# easyEDA.net
KiCad netlist of a schematic drawn in EasyEDA
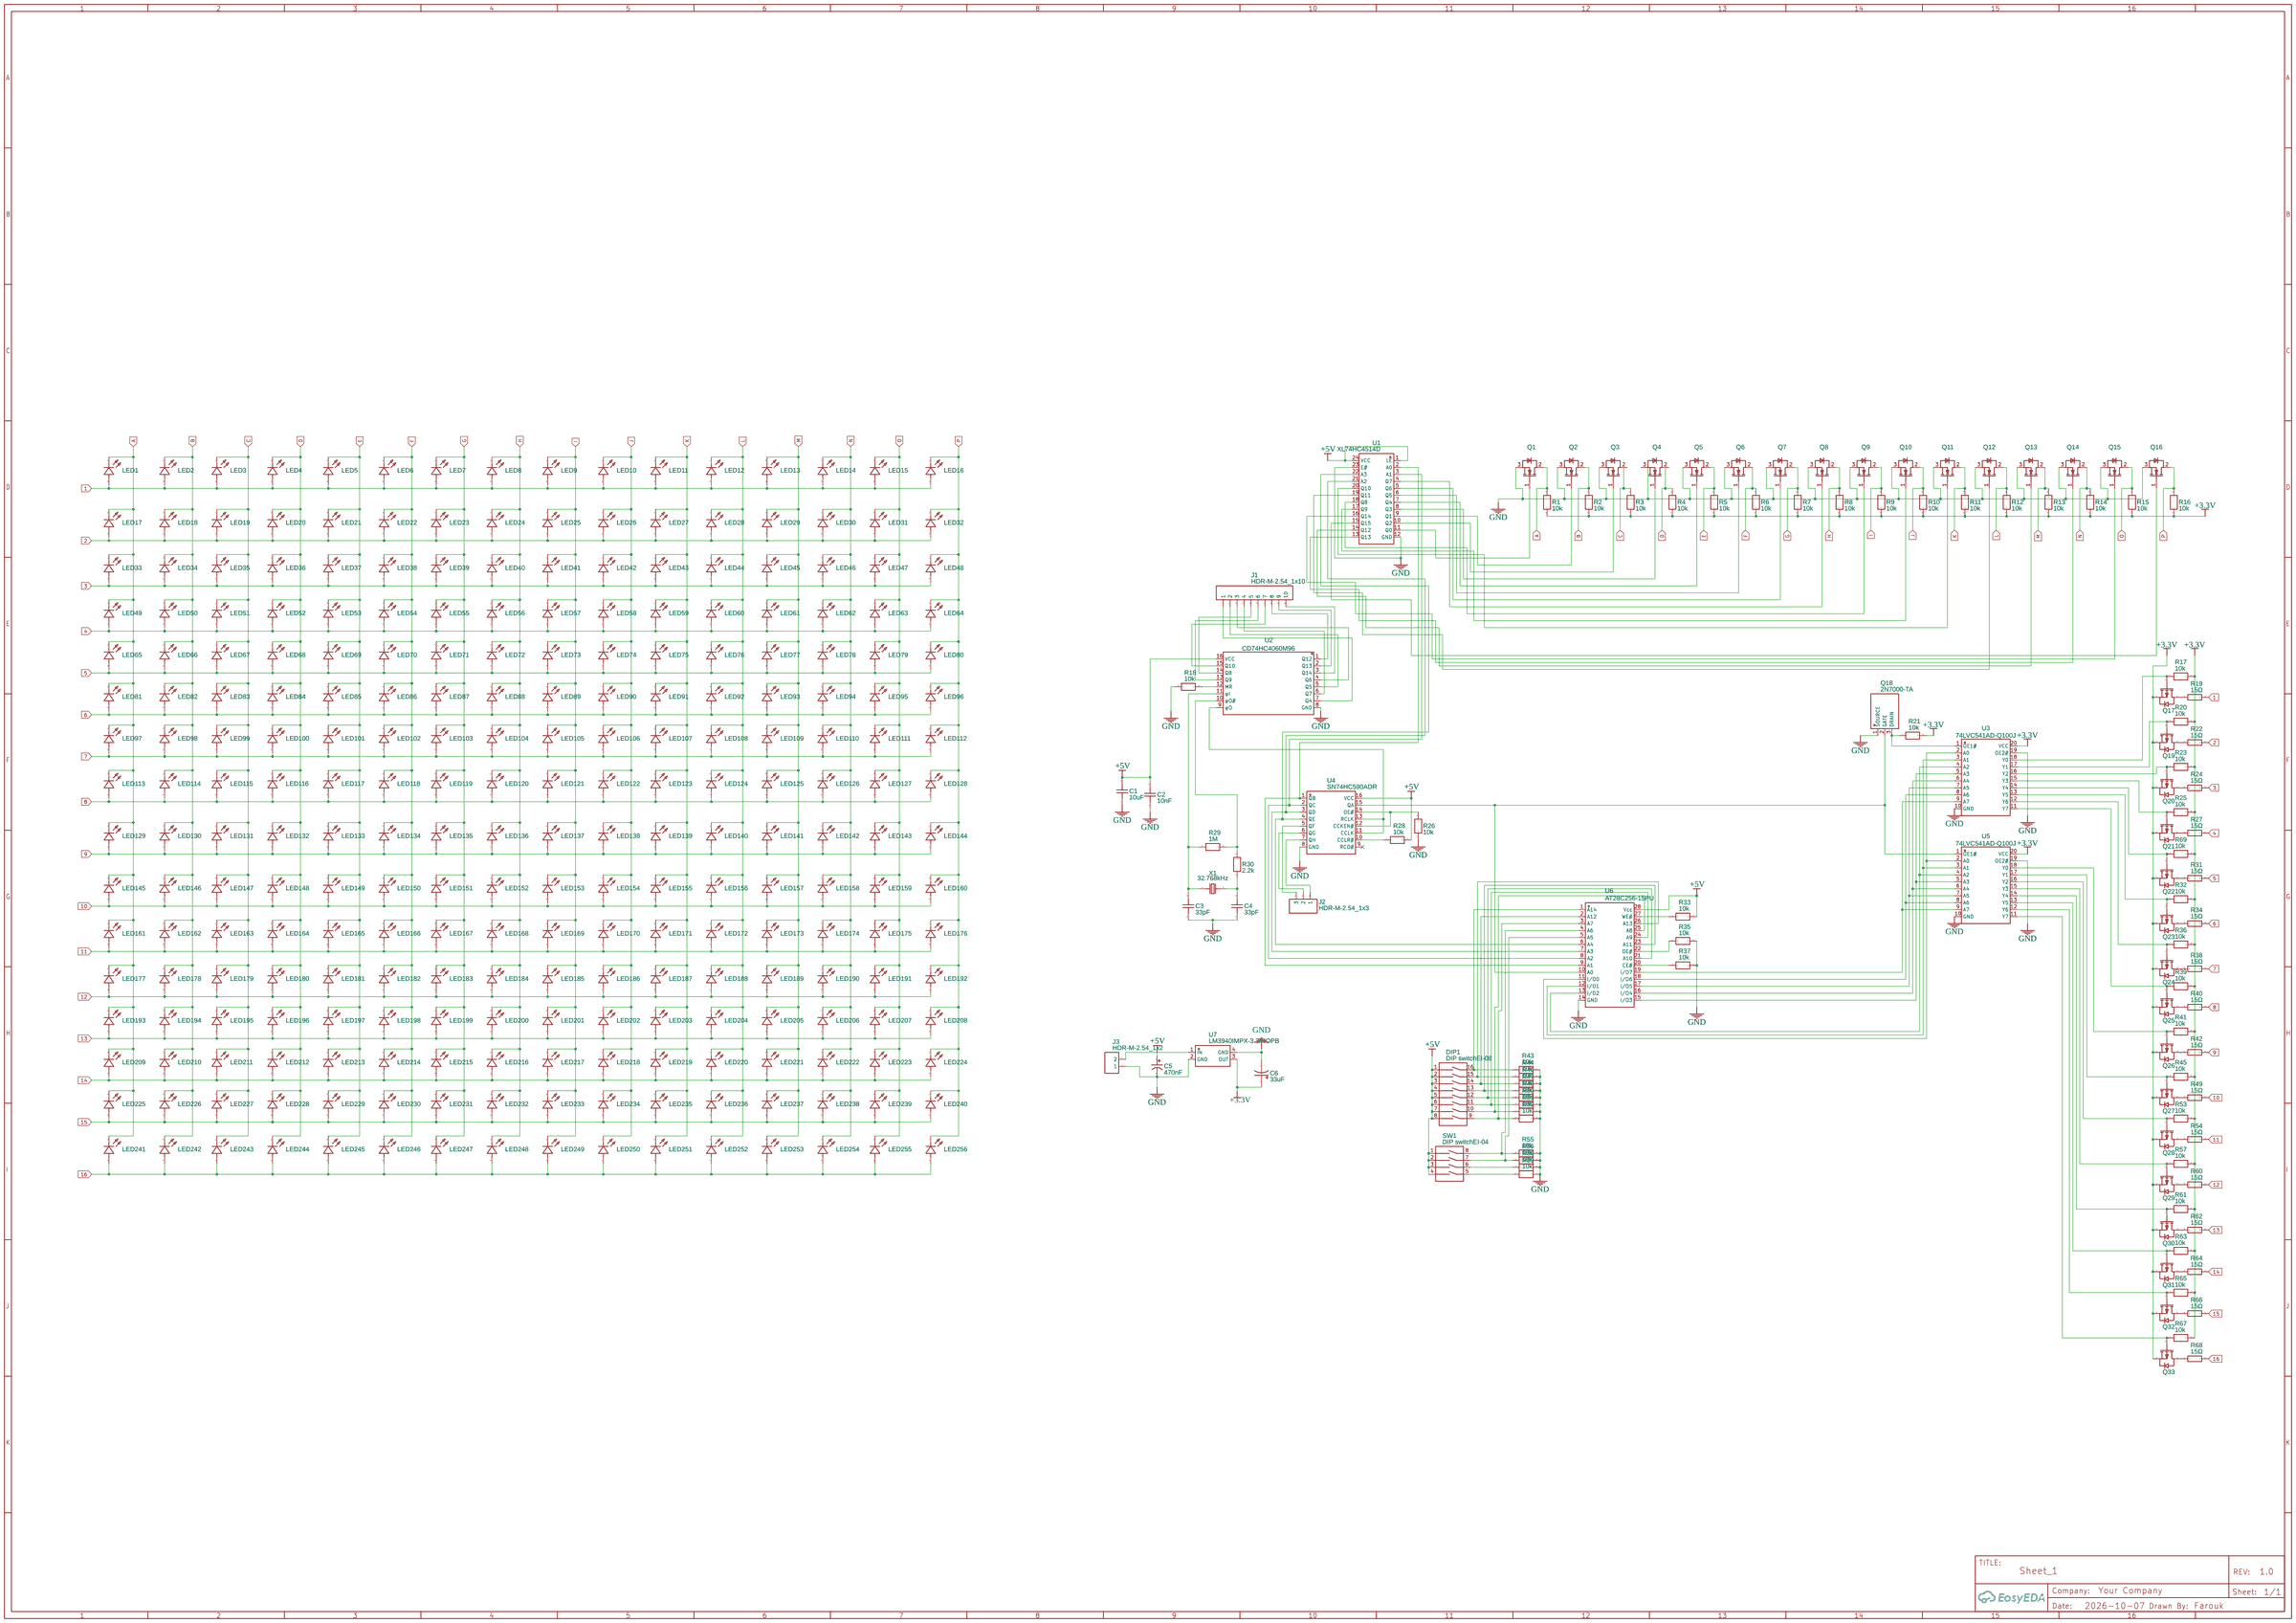
[diagram p0: schematic sheet]

(export (version "E")
  (design (tool "Eeschema 10.0.6"))
  (components
    (comp (ref "C1")
      (value "10uF")
      (fields
        (field (name "Manufacturer Part") "CC1210Y5V16V106ZN")
        (field (name "Manufacturer") "TORCH(火炬)")
      )
      (libsource (lib "") (part "CC1210Y5V16V106ZN"))
    )
    (comp (ref "C2")
      (value "10nF")
      (fields
        (field (name "Manufacturer Part") "CSA0805C0G103J500MT")
        (field (name "Manufacturer") "HRE(芯声)")
      )
      (libsource (lib "") (part "CSA0805C0G103J500MT"))
    )
    (comp (ref "C3")
      (value "33pF")
      (fields (field (name "Manufacturer Part") "600F330JT250XT") (field (name "Manufacturer") "Kyocera AVX"))
      (libsource (lib "") (part "600F330JT250XT"))
    )
    (comp (ref "C4")
      (value "33pF")
      (fields (field (name "Manufacturer Part") "600F330JT250XT") (field (name "Manufacturer") "Kyocera AVX"))
      (libsource (lib "") (part "600F330JT250XT"))
    )
    (comp (ref "C5")
      (value "470nF")
      (fields
        (field (name "Manufacturer Part") "kF474M050C05RR0VH2FP0")
        (field (name "Manufacturer") "Chengx(承兴)")
      )
      (libsource (lib "") (part "0.47uF 50V 4*5"))
    )
    (comp (ref "C6")
      (value "33uF")
      (fields
        (field (name "Manufacturer Part") "ECR1HPT330MLL063011")
        (field (name "Manufacturer") "Jianghai(南通江海)")
      )
      (libsource (lib "") (part "ECR1HPT330MLL063011"))
    )
    (comp (ref "DIP1")
      (value "DIP switchEI-08")
      (fields (field (name "Manufacturer Part") "EI-08-V") (field (name "Manufacturer") "Diptronics(圜达)"))
      (libsource (lib "") (part "DIP switchEI-08"))
    )
    (comp (ref "J1")
      (value "HDR-M-2.54_1x10")
      (fields
        (field (name "Manufacturer Part") "HX PZ-2005WV-1x10P")
        (field (name "Manufacturer") "hanxia(韩下)")
      )
      (libsource (lib "") (part "HDR-M-2.54_1x10"))
    )
    (comp (ref "J2")
      (value "HDR-M-2.54_1x3")
      (fields
        (field (name "Manufacturer Part") "5557WRF-1X3P(HDGC4201WR-F-1X3P)")
        (field (name "Manufacturer") "HDGC(华德共创)")
      )
      (libsource (lib "") (part "HDR-M-2.54_1x3"))
    )
    (comp (ref "J3") (value "HDR-M-2.54_1x2") (libsource (lib "") (part "HDR-M-2.54_1x2")))
    (comp (ref "LED1")
      (value "42-21A/GHC-YX1Y2N/1T")
      (fields (field (name "Manufacturer") "EVERLIGHT(亿光)"))
      (libsource (lib "") (part "42-21A/GHC-YX1Y2N/1T"))
    )
    (comp (ref "LED2")
      (value "42-21A/GHC-YX1Y2N/1T")
      (fields (field (name "Manufacturer") "EVERLIGHT(亿光)"))
      (libsource (lib "") (part "42-21A/GHC-YX1Y2N/1T"))
    )
    (comp (ref "LED3")
      (value "42-21A/GHC-YX1Y2N/1T")
      (fields (field (name "Manufacturer") "EVERLIGHT(亿光)"))
      (libsource (lib "") (part "42-21A/GHC-YX1Y2N/1T"))
    )
    (comp (ref "LED4")
      (value "42-21A/GHC-YX1Y2N/1T")
      (fields (field (name "Manufacturer") "EVERLIGHT(亿光)"))
      (libsource (lib "") (part "42-21A/GHC-YX1Y2N/1T"))
    )
    (comp (ref "LED5")
      (value "42-21A/GHC-YX1Y2N/1T")
      (fields (field (name "Manufacturer") "EVERLIGHT(亿光)"))
      (libsource (lib "") (part "42-21A/GHC-YX1Y2N/1T"))
    )
    (comp (ref "LED6")
      (value "42-21A/GHC-YX1Y2N/1T")
      (fields (field (name "Manufacturer") "EVERLIGHT(亿光)"))
      (libsource (lib "") (part "42-21A/GHC-YX1Y2N/1T"))
    )
    (comp (ref "LED7")
      (value "42-21A/GHC-YX1Y2N/1T")
      (fields (field (name "Manufacturer") "EVERLIGHT(亿光)"))
      (libsource (lib "") (part "42-21A/GHC-YX1Y2N/1T"))
    )
    (comp (ref "LED8")
      (value "42-21A/GHC-YX1Y2N/1T")
      (fields (field (name "Manufacturer") "EVERLIGHT(亿光)"))
      (libsource (lib "") (part "42-21A/GHC-YX1Y2N/1T"))
    )
    (comp (ref "LED9")
      (value "42-21A/GHC-YX1Y2N/1T")
      (fields (field (name "Manufacturer") "EVERLIGHT(亿光)"))
      (libsource (lib "") (part "42-21A/GHC-YX1Y2N/1T"))
    )
    (comp (ref "LED10")
      (value "42-21A/GHC-YX1Y2N/1T")
      (fields (field (name "Manufacturer") "EVERLIGHT(亿光)"))
      (libsource (lib "") (part "42-21A/GHC-YX1Y2N/1T"))
    )
    (comp (ref "LED11")
      (value "42-21A/GHC-YX1Y2N/1T")
      (fields (field (name "Manufacturer") "EVERLIGHT(亿光)"))
      (libsource (lib "") (part "42-21A/GHC-YX1Y2N/1T"))
    )
    (comp (ref "LED12")
      (value "42-21A/GHC-YX1Y2N/1T")
      (fields (field (name "Manufacturer") "EVERLIGHT(亿光)"))
      (libsource (lib "") (part "42-21A/GHC-YX1Y2N/1T"))
    )
    (comp (ref "LED13")
      (value "42-21A/GHC-YX1Y2N/1T")
      (fields (field (name "Manufacturer") "EVERLIGHT(亿光)"))
      (libsource (lib "") (part "42-21A/GHC-YX1Y2N/1T"))
    )
    (comp (ref "LED14")
      (value "42-21A/GHC-YX1Y2N/1T")
      (fields (field (name "Manufacturer") "EVERLIGHT(亿光)"))
      (libsource (lib "") (part "42-21A/GHC-YX1Y2N/1T"))
    )
    (comp (ref "LED15")
      (value "42-21A/GHC-YX1Y2N/1T")
      (fields (field (name "Manufacturer") "EVERLIGHT(亿光)"))
      (libsource (lib "") (part "42-21A/GHC-YX1Y2N/1T"))
    )
    (comp (ref "LED16")
      (value "42-21A/GHC-YX1Y2N/1T")
      (fields (field (name "Manufacturer") "EVERLIGHT(亿光)"))
      (libsource (lib "") (part "42-21A/GHC-YX1Y2N/1T"))
    )
    (comp (ref "LED17")
      (value "42-21A/GHC-YX1Y2N/1T")
      (fields (field (name "Manufacturer") "EVERLIGHT(亿光)"))
      (libsource (lib "") (part "42-21A/GHC-YX1Y2N/1T"))
    )
    (comp (ref "LED18")
      (value "42-21A/GHC-YX1Y2N/1T")
      (fields (field (name "Manufacturer") "EVERLIGHT(亿光)"))
      (libsource (lib "") (part "42-21A/GHC-YX1Y2N/1T"))
    )
    (comp (ref "LED19")
      (value "42-21A/GHC-YX1Y2N/1T")
      (fields (field (name "Manufacturer") "EVERLIGHT(亿光)"))
      (libsource (lib "") (part "42-21A/GHC-YX1Y2N/1T"))
    )
    (comp (ref "LED20")
      (value "42-21A/GHC-YX1Y2N/1T")
      (fields (field (name "Manufacturer") "EVERLIGHT(亿光)"))
      (libsource (lib "") (part "42-21A/GHC-YX1Y2N/1T"))
    )
    (comp (ref "LED21")
      (value "42-21A/GHC-YX1Y2N/1T")
      (fields (field (name "Manufacturer") "EVERLIGHT(亿光)"))
      (libsource (lib "") (part "42-21A/GHC-YX1Y2N/1T"))
    )
    (comp (ref "LED22")
      (value "42-21A/GHC-YX1Y2N/1T")
      (fields (field (name "Manufacturer") "EVERLIGHT(亿光)"))
      (libsource (lib "") (part "42-21A/GHC-YX1Y2N/1T"))
    )
    (comp (ref "LED23")
      (value "42-21A/GHC-YX1Y2N/1T")
      (fields (field (name "Manufacturer") "EVERLIGHT(亿光)"))
      (libsource (lib "") (part "42-21A/GHC-YX1Y2N/1T"))
    )
    (comp (ref "LED24")
      (value "42-21A/GHC-YX1Y2N/1T")
      (fields (field (name "Manufacturer") "EVERLIGHT(亿光)"))
      (libsource (lib "") (part "42-21A/GHC-YX1Y2N/1T"))
    )
    (comp (ref "LED25")
      (value "42-21A/GHC-YX1Y2N/1T")
      (fields (field (name "Manufacturer") "EVERLIGHT(亿光)"))
      (libsource (lib "") (part "42-21A/GHC-YX1Y2N/1T"))
    )
    (comp (ref "LED26")
      (value "42-21A/GHC-YX1Y2N/1T")
      (fields (field (name "Manufacturer") "EVERLIGHT(亿光)"))
      (libsource (lib "") (part "42-21A/GHC-YX1Y2N/1T"))
    )
    (comp (ref "LED27")
      (value "42-21A/GHC-YX1Y2N/1T")
      (fields (field (name "Manufacturer") "EVERLIGHT(亿光)"))
      (libsource (lib "") (part "42-21A/GHC-YX1Y2N/1T"))
    )
    (comp (ref "LED28")
      (value "42-21A/GHC-YX1Y2N/1T")
      (fields (field (name "Manufacturer") "EVERLIGHT(亿光)"))
      (libsource (lib "") (part "42-21A/GHC-YX1Y2N/1T"))
    )
    (comp (ref "LED29")
      (value "42-21A/GHC-YX1Y2N/1T")
      (fields (field (name "Manufacturer") "EVERLIGHT(亿光)"))
      (libsource (lib "") (part "42-21A/GHC-YX1Y2N/1T"))
    )
    (comp (ref "LED30")
      (value "42-21A/GHC-YX1Y2N/1T")
      (fields (field (name "Manufacturer") "EVERLIGHT(亿光)"))
      (libsource (lib "") (part "42-21A/GHC-YX1Y2N/1T"))
    )
    (comp (ref "LED31")
      (value "42-21A/GHC-YX1Y2N/1T")
      (fields (field (name "Manufacturer") "EVERLIGHT(亿光)"))
      (libsource (lib "") (part "42-21A/GHC-YX1Y2N/1T"))
    )
    (comp (ref "LED32")
      (value "42-21A/GHC-YX1Y2N/1T")
      (fields (field (name "Manufacturer") "EVERLIGHT(亿光)"))
      (libsource (lib "") (part "42-21A/GHC-YX1Y2N/1T"))
    )
    (comp (ref "LED33")
      (value "42-21A/GHC-YX1Y2N/1T")
      (fields (field (name "Manufacturer") "EVERLIGHT(亿光)"))
      (libsource (lib "") (part "42-21A/GHC-YX1Y2N/1T"))
    )
    (comp (ref "LED34")
      (value "42-21A/GHC-YX1Y2N/1T")
      (fields (field (name "Manufacturer") "EVERLIGHT(亿光)"))
      (libsource (lib "") (part "42-21A/GHC-YX1Y2N/1T"))
    )
    (comp (ref "LED35")
      (value "42-21A/GHC-YX1Y2N/1T")
      (fields (field (name "Manufacturer") "EVERLIGHT(亿光)"))
      (libsource (lib "") (part "42-21A/GHC-YX1Y2N/1T"))
    )
    (comp (ref "LED36")
      (value "42-21A/GHC-YX1Y2N/1T")
      (fields (field (name "Manufacturer") "EVERLIGHT(亿光)"))
      (libsource (lib "") (part "42-21A/GHC-YX1Y2N/1T"))
    )
    (comp (ref "LED37")
      (value "42-21A/GHC-YX1Y2N/1T")
      (fields (field (name "Manufacturer") "EVERLIGHT(亿光)"))
      (libsource (lib "") (part "42-21A/GHC-YX1Y2N/1T"))
    )
    (comp (ref "LED38")
      (value "42-21A/GHC-YX1Y2N/1T")
      (fields (field (name "Manufacturer") "EVERLIGHT(亿光)"))
      (libsource (lib "") (part "42-21A/GHC-YX1Y2N/1T"))
    )
    (comp (ref "LED39")
      (value "42-21A/GHC-YX1Y2N/1T")
      (fields (field (name "Manufacturer") "EVERLIGHT(亿光)"))
      (libsource (lib "") (part "42-21A/GHC-YX1Y2N/1T"))
    )
    (comp (ref "LED40")
      (value "42-21A/GHC-YX1Y2N/1T")
      (fields (field (name "Manufacturer") "EVERLIGHT(亿光)"))
      (libsource (lib "") (part "42-21A/GHC-YX1Y2N/1T"))
    )
    (comp (ref "LED41")
      (value "42-21A/GHC-YX1Y2N/1T")
      (fields (field (name "Manufacturer") "EVERLIGHT(亿光)"))
      (libsource (lib "") (part "42-21A/GHC-YX1Y2N/1T"))
    )
    (comp (ref "LED42")
      (value "42-21A/GHC-YX1Y2N/1T")
      (fields (field (name "Manufacturer") "EVERLIGHT(亿光)"))
      (libsource (lib "") (part "42-21A/GHC-YX1Y2N/1T"))
    )
    (comp (ref "LED43")
      (value "42-21A/GHC-YX1Y2N/1T")
      (fields (field (name "Manufacturer") "EVERLIGHT(亿光)"))
      (libsource (lib "") (part "42-21A/GHC-YX1Y2N/1T"))
    )
    (comp (ref "LED44")
      (value "42-21A/GHC-YX1Y2N/1T")
      (fields (field (name "Manufacturer") "EVERLIGHT(亿光)"))
      (libsource (lib "") (part "42-21A/GHC-YX1Y2N/1T"))
    )
    (comp (ref "LED45")
      (value "42-21A/GHC-YX1Y2N/1T")
      (fields (field (name "Manufacturer") "EVERLIGHT(亿光)"))
      (libsource (lib "") (part "42-21A/GHC-YX1Y2N/1T"))
    )
    (comp (ref "LED46")
      (value "42-21A/GHC-YX1Y2N/1T")
      (fields (field (name "Manufacturer") "EVERLIGHT(亿光)"))
      (libsource (lib "") (part "42-21A/GHC-YX1Y2N/1T"))
    )
    (comp (ref "LED47")
      (value "42-21A/GHC-YX1Y2N/1T")
      (fields (field (name "Manufacturer") "EVERLIGHT(亿光)"))
      (libsource (lib "") (part "42-21A/GHC-YX1Y2N/1T"))
    )
    (comp (ref "LED48")
      (value "42-21A/GHC-YX1Y2N/1T")
      (fields (field (name "Manufacturer") "EVERLIGHT(亿光)"))
      (libsource (lib "") (part "42-21A/GHC-YX1Y2N/1T"))
    )
    (comp (ref "LED49")
      (value "42-21A/GHC-YX1Y2N/1T")
      (fields (field (name "Manufacturer") "EVERLIGHT(亿光)"))
      (libsource (lib "") (part "42-21A/GHC-YX1Y2N/1T"))
    )
    (comp (ref "LED50")
      (value "42-21A/GHC-YX1Y2N/1T")
      (fields (field (name "Manufacturer") "EVERLIGHT(亿光)"))
      (libsource (lib "") (part "42-21A/GHC-YX1Y2N/1T"))
    )
    (comp (ref "LED51")
      (value "42-21A/GHC-YX1Y2N/1T")
      (fields (field (name "Manufacturer") "EVERLIGHT(亿光)"))
      (libsource (lib "") (part "42-21A/GHC-YX1Y2N/1T"))
    )
    (comp (ref "LED52")
      (value "42-21A/GHC-YX1Y2N/1T")
      (fields (field (name "Manufacturer") "EVERLIGHT(亿光)"))
      (libsource (lib "") (part "42-21A/GHC-YX1Y2N/1T"))
    )
    (comp (ref "LED53")
      (value "42-21A/GHC-YX1Y2N/1T")
      (fields (field (name "Manufacturer") "EVERLIGHT(亿光)"))
      (libsource (lib "") (part "42-21A/GHC-YX1Y2N/1T"))
    )
    (comp (ref "LED54")
      (value "42-21A/GHC-YX1Y2N/1T")
      (fields (field (name "Manufacturer") "EVERLIGHT(亿光)"))
      (libsource (lib "") (part "42-21A/GHC-YX1Y2N/1T"))
    )
    (comp (ref "LED55")
      (value "42-21A/GHC-YX1Y2N/1T")
      (fields (field (name "Manufacturer") "EVERLIGHT(亿光)"))
      (libsource (lib "") (part "42-21A/GHC-YX1Y2N/1T"))
    )
    (comp (ref "LED56")
      (value "42-21A/GHC-YX1Y2N/1T")
      (fields (field (name "Manufacturer") "EVERLIGHT(亿光)"))
      (libsource (lib "") (part "42-21A/GHC-YX1Y2N/1T"))
    )
    (comp (ref "LED57")
      (value "42-21A/GHC-YX1Y2N/1T")
      (fields (field (name "Manufacturer") "EVERLIGHT(亿光)"))
      (libsource (lib "") (part "42-21A/GHC-YX1Y2N/1T"))
    )
    (comp (ref "LED58")
      (value "42-21A/GHC-YX1Y2N/1T")
      (fields (field (name "Manufacturer") "EVERLIGHT(亿光)"))
      (libsource (lib "") (part "42-21A/GHC-YX1Y2N/1T"))
    )
    (comp (ref "LED59")
      (value "42-21A/GHC-YX1Y2N/1T")
      (fields (field (name "Manufacturer") "EVERLIGHT(亿光)"))
      (libsource (lib "") (part "42-21A/GHC-YX1Y2N/1T"))
    )
    (comp (ref "LED60")
      (value "42-21A/GHC-YX1Y2N/1T")
      (fields (field (name "Manufacturer") "EVERLIGHT(亿光)"))
      (libsource (lib "") (part "42-21A/GHC-YX1Y2N/1T"))
    )
    (comp (ref "LED61")
      (value "42-21A/GHC-YX1Y2N/1T")
      (fields (field (name "Manufacturer") "EVERLIGHT(亿光)"))
      (libsource (lib "") (part "42-21A/GHC-YX1Y2N/1T"))
    )
    (comp (ref "LED62")
      (value "42-21A/GHC-YX1Y2N/1T")
      (fields (field (name "Manufacturer") "EVERLIGHT(亿光)"))
      (libsource (lib "") (part "42-21A/GHC-YX1Y2N/1T"))
    )
    (comp (ref "LED63")
      (value "42-21A/GHC-YX1Y2N/1T")
      (fields (field (name "Manufacturer") "EVERLIGHT(亿光)"))
      (libsource (lib "") (part "42-21A/GHC-YX1Y2N/1T"))
    )
    (comp (ref "LED64")
      (value "42-21A/GHC-YX1Y2N/1T")
      (fields (field (name "Manufacturer") "EVERLIGHT(亿光)"))
      (libsource (lib "") (part "42-21A/GHC-YX1Y2N/1T"))
    )
    (comp (ref "LED65")
      (value "42-21A/GHC-YX1Y2N/1T")
      (fields (field (name "Manufacturer") "EVERLIGHT(亿光)"))
      (libsource (lib "") (part "42-21A/GHC-YX1Y2N/1T"))
    )
    (comp (ref "LED66")
      (value "42-21A/GHC-YX1Y2N/1T")
      (fields (field (name "Manufacturer") "EVERLIGHT(亿光)"))
      (libsource (lib "") (part "42-21A/GHC-YX1Y2N/1T"))
    )
    (comp (ref "LED67")
      (value "42-21A/GHC-YX1Y2N/1T")
      (fields (field (name "Manufacturer") "EVERLIGHT(亿光)"))
      (libsource (lib "") (part "42-21A/GHC-YX1Y2N/1T"))
    )
    (comp (ref "LED68")
      (value "42-21A/GHC-YX1Y2N/1T")
      (fields (field (name "Manufacturer") "EVERLIGHT(亿光)"))
      (libsource (lib "") (part "42-21A/GHC-YX1Y2N/1T"))
    )
    (comp (ref "LED69")
      (value "42-21A/GHC-YX1Y2N/1T")
      (fields (field (name "Manufacturer") "EVERLIGHT(亿光)"))
      (libsource (lib "") (part "42-21A/GHC-YX1Y2N/1T"))
    )
    (comp (ref "LED70")
      (value "42-21A/GHC-YX1Y2N/1T")
      (fields (field (name "Manufacturer") "EVERLIGHT(亿光)"))
      (libsource (lib "") (part "42-21A/GHC-YX1Y2N/1T"))
    )
    (comp (ref "LED71")
      (value "42-21A/GHC-YX1Y2N/1T")
      (fields (field (name "Manufacturer") "EVERLIGHT(亿光)"))
      (libsource (lib "") (part "42-21A/GHC-YX1Y2N/1T"))
    )
    (comp (ref "LED72")
      (value "42-21A/GHC-YX1Y2N/1T")
      (fields (field (name "Manufacturer") "EVERLIGHT(亿光)"))
      (libsource (lib "") (part "42-21A/GHC-YX1Y2N/1T"))
    )
    (comp (ref "LED73")
      (value "42-21A/GHC-YX1Y2N/1T")
      (fields (field (name "Manufacturer") "EVERLIGHT(亿光)"))
      (libsource (lib "") (part "42-21A/GHC-YX1Y2N/1T"))
    )
    (comp (ref "LED74")
      (value "42-21A/GHC-YX1Y2N/1T")
      (fields (field (name "Manufacturer") "EVERLIGHT(亿光)"))
      (libsource (lib "") (part "42-21A/GHC-YX1Y2N/1T"))
    )
    (comp (ref "LED75")
      (value "42-21A/GHC-YX1Y2N/1T")
      (fields (field (name "Manufacturer") "EVERLIGHT(亿光)"))
      (libsource (lib "") (part "42-21A/GHC-YX1Y2N/1T"))
    )
    (comp (ref "LED76")
      (value "42-21A/GHC-YX1Y2N/1T")
      (fields (field (name "Manufacturer") "EVERLIGHT(亿光)"))
      (libsource (lib "") (part "42-21A/GHC-YX1Y2N/1T"))
    )
    (comp (ref "LED77")
      (value "42-21A/GHC-YX1Y2N/1T")
      (fields (field (name "Manufacturer") "EVERLIGHT(亿光)"))
      (libsource (lib "") (part "42-21A/GHC-YX1Y2N/1T"))
    )
    (comp (ref "LED78")
      (value "42-21A/GHC-YX1Y2N/1T")
      (fields (field (name "Manufacturer") "EVERLIGHT(亿光)"))
      (libsource (lib "") (part "42-21A/GHC-YX1Y2N/1T"))
    )
    (comp (ref "LED79")
      (value "42-21A/GHC-YX1Y2N/1T")
      (fields (field (name "Manufacturer") "EVERLIGHT(亿光)"))
      (libsource (lib "") (part "42-21A/GHC-YX1Y2N/1T"))
    )
    (comp (ref "LED80")
      (value "42-21A/GHC-YX1Y2N/1T")
      (fields (field (name "Manufacturer") "EVERLIGHT(亿光)"))
      (libsource (lib "") (part "42-21A/GHC-YX1Y2N/1T"))
    )
    (comp (ref "LED81")
      (value "42-21A/GHC-YX1Y2N/1T")
      (fields (field (name "Manufacturer") "EVERLIGHT(亿光)"))
      (libsource (lib "") (part "42-21A/GHC-YX1Y2N/1T"))
    )
    (comp (ref "LED82")
      (value "42-21A/GHC-YX1Y2N/1T")
      (fields (field (name "Manufacturer") "EVERLIGHT(亿光)"))
      (libsource (lib "") (part "42-21A/GHC-YX1Y2N/1T"))
    )
    (comp (ref "LED83")
      (value "42-21A/GHC-YX1Y2N/1T")
      (fields (field (name "Manufacturer") "EVERLIGHT(亿光)"))
      (libsource (lib "") (part "42-21A/GHC-YX1Y2N/1T"))
    )
    (comp (ref "LED84")
      (value "42-21A/GHC-YX1Y2N/1T")
      (fields (field (name "Manufacturer") "EVERLIGHT(亿光)"))
      (libsource (lib "") (part "42-21A/GHC-YX1Y2N/1T"))
    )
    (comp (ref "LED85")
      (value "42-21A/GHC-YX1Y2N/1T")
      (fields (field (name "Manufacturer") "EVERLIGHT(亿光)"))
      (libsource (lib "") (part "42-21A/GHC-YX1Y2N/1T"))
    )
    (comp (ref "LED86")
      (value "42-21A/GHC-YX1Y2N/1T")
      (fields (field (name "Manufacturer") "EVERLIGHT(亿光)"))
      (libsource (lib "") (part "42-21A/GHC-YX1Y2N/1T"))
    )
    (comp (ref "LED87")
      (value "42-21A/GHC-YX1Y2N/1T")
      (fields (field (name "Manufacturer") "EVERLIGHT(亿光)"))
      (libsource (lib "") (part "42-21A/GHC-YX1Y2N/1T"))
    )
    (comp (ref "LED88")
      (value "42-21A/GHC-YX1Y2N/1T")
      (fields (field (name "Manufacturer") "EVERLIGHT(亿光)"))
      (libsource (lib "") (part "42-21A/GHC-YX1Y2N/1T"))
    )
    (comp (ref "LED89")
      (value "42-21A/GHC-YX1Y2N/1T")
      (fields (field (name "Manufacturer") "EVERLIGHT(亿光)"))
      (libsource (lib "") (part "42-21A/GHC-YX1Y2N/1T"))
    )
    (comp (ref "LED90")
      (value "42-21A/GHC-YX1Y2N/1T")
      (fields (field (name "Manufacturer") "EVERLIGHT(亿光)"))
      (libsource (lib "") (part "42-21A/GHC-YX1Y2N/1T"))
    )
    (comp (ref "LED91")
      (value "42-21A/GHC-YX1Y2N/1T")
      (fields (field (name "Manufacturer") "EVERLIGHT(亿光)"))
      (libsource (lib "") (part "42-21A/GHC-YX1Y2N/1T"))
    )
    (comp (ref "LED92")
      (value "42-21A/GHC-YX1Y2N/1T")
      (fields (field (name "Manufacturer") "EVERLIGHT(亿光)"))
      (libsource (lib "") (part "42-21A/GHC-YX1Y2N/1T"))
    )
    (comp (ref "LED93")
      (value "42-21A/GHC-YX1Y2N/1T")
      (fields (field (name "Manufacturer") "EVERLIGHT(亿光)"))
      (libsource (lib "") (part "42-21A/GHC-YX1Y2N/1T"))
    )
    (comp (ref "LED94")
      (value "42-21A/GHC-YX1Y2N/1T")
      (fields (field (name "Manufacturer") "EVERLIGHT(亿光)"))
      (libsource (lib "") (part "42-21A/GHC-YX1Y2N/1T"))
    )
    (comp (ref "LED95")
      (value "42-21A/GHC-YX1Y2N/1T")
      (fields (field (name "Manufacturer") "EVERLIGHT(亿光)"))
      (libsource (lib "") (part "42-21A/GHC-YX1Y2N/1T"))
    )
    (comp (ref "LED96")
      (value "42-21A/GHC-YX1Y2N/1T")
      (fields (field (name "Manufacturer") "EVERLIGHT(亿光)"))
      (libsource (lib "") (part "42-21A/GHC-YX1Y2N/1T"))
    )
    (comp (ref "LED97")
      (value "42-21A/GHC-YX1Y2N/1T")
      (fields (field (name "Manufacturer") "EVERLIGHT(亿光)"))
      (libsource (lib "") (part "42-21A/GHC-YX1Y2N/1T"))
    )
    (comp (ref "LED98")
      (value "42-21A/GHC-YX1Y2N/1T")
      (fields (field (name "Manufacturer") "EVERLIGHT(亿光)"))
      (libsource (lib "") (part "42-21A/GHC-YX1Y2N/1T"))
    )
    (comp (ref "LED99")
      (value "42-21A/GHC-YX1Y2N/1T")
      (fields (field (name "Manufacturer") "EVERLIGHT(亿光)"))
      (libsource (lib "") (part "42-21A/GHC-YX1Y2N/1T"))
    )
    (comp (ref "LED100")
      (value "42-21A/GHC-YX1Y2N/1T")
      (fields (field (name "Manufacturer") "EVERLIGHT(亿光)"))
      (libsource (lib "") (part "42-21A/GHC-YX1Y2N/1T"))
    )
    (comp (ref "LED101")
      (value "42-21A/GHC-YX1Y2N/1T")
      (fields (field (name "Manufacturer") "EVERLIGHT(亿光)"))
      (libsource (lib "") (part "42-21A/GHC-YX1Y2N/1T"))
    )
    (comp (ref "LED102")
      (value "42-21A/GHC-YX1Y2N/1T")
      (fields (field (name "Manufacturer") "EVERLIGHT(亿光)"))
      (libsource (lib "") (part "42-21A/GHC-YX1Y2N/1T"))
    )
    (comp (ref "LED103")
      (value "42-21A/GHC-YX1Y2N/1T")
      (fields (field (name "Manufacturer") "EVERLIGHT(亿光)"))
      (libsource (lib "") (part "42-21A/GHC-YX1Y2N/1T"))
    )
    (comp (ref "LED104")
      (value "42-21A/GHC-YX1Y2N/1T")
      (fields (field (name "Manufacturer") "EVERLIGHT(亿光)"))
      (libsource (lib "") (part "42-21A/GHC-YX1Y2N/1T"))
    )
    (comp (ref "LED105")
      (value "42-21A/GHC-YX1Y2N/1T")
      (fields (field (name "Manufacturer") "EVERLIGHT(亿光)"))
      (libsource (lib "") (part "42-21A/GHC-YX1Y2N/1T"))
    )
    (comp (ref "LED106")
      (value "42-21A/GHC-YX1Y2N/1T")
      (fields (field (name "Manufacturer") "EVERLIGHT(亿光)"))
      (libsource (lib "") (part "42-21A/GHC-YX1Y2N/1T"))
    )
    (comp (ref "LED107")
      (value "42-21A/GHC-YX1Y2N/1T")
      (fields (field (name "Manufacturer") "EVERLIGHT(亿光)"))
      (libsource (lib "") (part "42-21A/GHC-YX1Y2N/1T"))
    )
    (comp (ref "LED108")
      (value "42-21A/GHC-YX1Y2N/1T")
      (fields (field (name "Manufacturer") "EVERLIGHT(亿光)"))
      (libsource (lib "") (part "42-21A/GHC-YX1Y2N/1T"))
    )
    (comp (ref "LED109")
      (value "42-21A/GHC-YX1Y2N/1T")
      (fields (field (name "Manufacturer") "EVERLIGHT(亿光)"))
      (libsource (lib "") (part "42-21A/GHC-YX1Y2N/1T"))
    )
    (comp (ref "LED110")
      (value "42-21A/GHC-YX1Y2N/1T")
      (fields (field (name "Manufacturer") "EVERLIGHT(亿光)"))
      (libsource (lib "") (part "42-21A/GHC-YX1Y2N/1T"))
    )
    (comp (ref "LED111")
      (value "42-21A/GHC-YX1Y2N/1T")
      (fields (field (name "Manufacturer") "EVERLIGHT(亿光)"))
      (libsource (lib "") (part "42-21A/GHC-YX1Y2N/1T"))
    )
    (comp (ref "LED112")
      (value "42-21A/GHC-YX1Y2N/1T")
      (fields (field (name "Manufacturer") "EVERLIGHT(亿光)"))
      (libsource (lib "") (part "42-21A/GHC-YX1Y2N/1T"))
    )
    (comp (ref "LED113")
      (value "42-21A/GHC-YX1Y2N/1T")
      (fields (field (name "Manufacturer") "EVERLIGHT(亿光)"))
      (libsource (lib "") (part "42-21A/GHC-YX1Y2N/1T"))
    )
    (comp (ref "LED114")
      (value "42-21A/GHC-YX1Y2N/1T")
      (fields (field (name "Manufacturer") "EVERLIGHT(亿光)"))
      (libsource (lib "") (part "42-21A/GHC-YX1Y2N/1T"))
    )
    (comp (ref "LED115")
      (value "42-21A/GHC-YX1Y2N/1T")
      (fields (field (name "Manufacturer") "EVERLIGHT(亿光)"))
      (libsource (lib "") (part "42-21A/GHC-YX1Y2N/1T"))
    )
    (comp (ref "LED116")
      (value "42-21A/GHC-YX1Y2N/1T")
      (fields (field (name "Manufacturer") "EVERLIGHT(亿光)"))
      (libsource (lib "") (part "42-21A/GHC-YX1Y2N/1T"))
    )
    (comp (ref "LED117")
      (value "42-21A/GHC-YX1Y2N/1T")
      (fields (field (name "Manufacturer") "EVERLIGHT(亿光)"))
      (libsource (lib "") (part "42-21A/GHC-YX1Y2N/1T"))
    )
    (comp (ref "LED118")
      (value "42-21A/GHC-YX1Y2N/1T")
      (fields (field (name "Manufacturer") "EVERLIGHT(亿光)"))
      (libsource (lib "") (part "42-21A/GHC-YX1Y2N/1T"))
    )
    (comp (ref "LED119")
      (value "42-21A/GHC-YX1Y2N/1T")
      (fields (field (name "Manufacturer") "EVERLIGHT(亿光)"))
      (libsource (lib "") (part "42-21A/GHC-YX1Y2N/1T"))
    )
    (comp (ref "LED120")
      (value "42-21A/GHC-YX1Y2N/1T")
      (fields (field (name "Manufacturer") "EVERLIGHT(亿光)"))
      (libsource (lib "") (part "42-21A/GHC-YX1Y2N/1T"))
    )
    (comp (ref "LED121")
      (value "42-21A/GHC-YX1Y2N/1T")
      (fields (field (name "Manufacturer") "EVERLIGHT(亿光)"))
      (libsource (lib "") (part "42-21A/GHC-YX1Y2N/1T"))
    )
    (comp (ref "LED122")
      (value "42-21A/GHC-YX1Y2N/1T")
      (fields (field (name "Manufacturer") "EVERLIGHT(亿光)"))
      (libsource (lib "") (part "42-21A/GHC-YX1Y2N/1T"))
    )
    (comp (ref "LED123")
      (value "42-21A/GHC-YX1Y2N/1T")
      (fields (field (name "Manufacturer") "EVERLIGHT(亿光)"))
      (libsource (lib "") (part "42-21A/GHC-YX1Y2N/1T"))
    )
    (comp (ref "LED124")
      (value "42-21A/GHC-YX1Y2N/1T")
      (fields (field (name "Manufacturer") "EVERLIGHT(亿光)"))
      (libsource (lib "") (part "42-21A/GHC-YX1Y2N/1T"))
    )
    (comp (ref "LED125")
      (value "42-21A/GHC-YX1Y2N/1T")
      (fields (field (name "Manufacturer") "EVERLIGHT(亿光)"))
      (libsource (lib "") (part "42-21A/GHC-YX1Y2N/1T"))
    )
    (comp (ref "LED126")
      (value "42-21A/GHC-YX1Y2N/1T")
      (fields (field (name "Manufacturer") "EVERLIGHT(亿光)"))
      (libsource (lib "") (part "42-21A/GHC-YX1Y2N/1T"))
    )
    (comp (ref "LED127")
      (value "42-21A/GHC-YX1Y2N/1T")
      (fields (field (name "Manufacturer") "EVERLIGHT(亿光)"))
      (libsource (lib "") (part "42-21A/GHC-YX1Y2N/1T"))
    )
    (comp (ref "LED128")
      (value "42-21A/GHC-YX1Y2N/1T")
      (fields (field (name "Manufacturer") "EVERLIGHT(亿光)"))
      (libsource (lib "") (part "42-21A/GHC-YX1Y2N/1T"))
    )
    (comp (ref "LED129")
      (value "42-21A/GHC-YX1Y2N/1T")
      (fields (field (name "Manufacturer") "EVERLIGHT(亿光)"))
      (libsource (lib "") (part "42-21A/GHC-YX1Y2N/1T"))
    )
    (comp (ref "LED130")
      (value "42-21A/GHC-YX1Y2N/1T")
      (fields (field (name "Manufacturer") "EVERLIGHT(亿光)"))
      (libsource (lib "") (part "42-21A/GHC-YX1Y2N/1T"))
    )
    (comp (ref "LED131")
      (value "42-21A/GHC-YX1Y2N/1T")
      (fields (field (name "Manufacturer") "EVERLIGHT(亿光)"))
      (libsource (lib "") (part "42-21A/GHC-YX1Y2N/1T"))
    )
    (comp (ref "LED132")
      (value "42-21A/GHC-YX1Y2N/1T")
      (fields (field (name "Manufacturer") "EVERLIGHT(亿光)"))
      (libsource (lib "") (part "42-21A/GHC-YX1Y2N/1T"))
    )
    (comp (ref "LED133")
      (value "42-21A/GHC-YX1Y2N/1T")
      (fields (field (name "Manufacturer") "EVERLIGHT(亿光)"))
      (libsource (lib "") (part "42-21A/GHC-YX1Y2N/1T"))
    )
    (comp (ref "LED134")
      (value "42-21A/GHC-YX1Y2N/1T")
      (fields (field (name "Manufacturer") "EVERLIGHT(亿光)"))
      (libsource (lib "") (part "42-21A/GHC-YX1Y2N/1T"))
    )
    (comp (ref "LED135")
      (value "42-21A/GHC-YX1Y2N/1T")
      (fields (field (name "Manufacturer") "EVERLIGHT(亿光)"))
      (libsource (lib "") (part "42-21A/GHC-YX1Y2N/1T"))
    )
    (comp (ref "LED136")
      (value "42-21A/GHC-YX1Y2N/1T")
      (fields (field (name "Manufacturer") "EVERLIGHT(亿光)"))
      (libsource (lib "") (part "42-21A/GHC-YX1Y2N/1T"))
    )
    (comp (ref "LED137")
      (value "42-21A/GHC-YX1Y2N/1T")
      (fields (field (name "Manufacturer") "EVERLIGHT(亿光)"))
      (libsource (lib "") (part "42-21A/GHC-YX1Y2N/1T"))
    )
    (comp (ref "LED138")
      (value "42-21A/GHC-YX1Y2N/1T")
      (fields (field (name "Manufacturer") "EVERLIGHT(亿光)"))
      (libsource (lib "") (part "42-21A/GHC-YX1Y2N/1T"))
    )
    (comp (ref "LED139")
      (value "42-21A/GHC-YX1Y2N/1T")
      (fields (field (name "Manufacturer") "EVERLIGHT(亿光)"))
      (libsource (lib "") (part "42-21A/GHC-YX1Y2N/1T"))
    )
    (comp (ref "LED140")
      (value "42-21A/GHC-YX1Y2N/1T")
      (fields (field (name "Manufacturer") "EVERLIGHT(亿光)"))
      (libsource (lib "") (part "42-21A/GHC-YX1Y2N/1T"))
    )
    (comp (ref "LED141")
      (value "42-21A/GHC-YX1Y2N/1T")
      (fields (field (name "Manufacturer") "EVERLIGHT(亿光)"))
      (libsource (lib "") (part "42-21A/GHC-YX1Y2N/1T"))
    )
    (comp (ref "LED142")
      (value "42-21A/GHC-YX1Y2N/1T")
      (fields (field (name "Manufacturer") "EVERLIGHT(亿光)"))
      (libsource (lib "") (part "42-21A/GHC-YX1Y2N/1T"))
    )
    (comp (ref "LED143")
      (value "42-21A/GHC-YX1Y2N/1T")
      (fields (field (name "Manufacturer") "EVERLIGHT(亿光)"))
      (libsource (lib "") (part "42-21A/GHC-YX1Y2N/1T"))
    )
    (comp (ref "LED144")
      (value "42-21A/GHC-YX1Y2N/1T")
      (fields (field (name "Manufacturer") "EVERLIGHT(亿光)"))
      (libsource (lib "") (part "42-21A/GHC-YX1Y2N/1T"))
    )
    (comp (ref "LED145")
      (value "42-21A/GHC-YX1Y2N/1T")
      (fields (field (name "Manufacturer") "EVERLIGHT(亿光)"))
      (libsource (lib "") (part "42-21A/GHC-YX1Y2N/1T"))
    )
    (comp (ref "LED146")
      (value "42-21A/GHC-YX1Y2N/1T")
      (fields (field (name "Manufacturer") "EVERLIGHT(亿光)"))
      (libsource (lib "") (part "42-21A/GHC-YX1Y2N/1T"))
    )
    (comp (ref "LED147")
      (value "42-21A/GHC-YX1Y2N/1T")
      (fields (field (name "Manufacturer") "EVERLIGHT(亿光)"))
      (libsource (lib "") (part "42-21A/GHC-YX1Y2N/1T"))
    )
    (comp (ref "LED148")
      (value "42-21A/GHC-YX1Y2N/1T")
      (fields (field (name "Manufacturer") "EVERLIGHT(亿光)"))
      (libsource (lib "") (part "42-21A/GHC-YX1Y2N/1T"))
    )
    (comp (ref "LED149")
      (value "42-21A/GHC-YX1Y2N/1T")
      (fields (field (name "Manufacturer") "EVERLIGHT(亿光)"))
      (libsource (lib "") (part "42-21A/GHC-YX1Y2N/1T"))
    )
    (comp (ref "LED150")
      (value "42-21A/GHC-YX1Y2N/1T")
      (fields (field (name "Manufacturer") "EVERLIGHT(亿光)"))
      (libsource (lib "") (part "42-21A/GHC-YX1Y2N/1T"))
    )
    (comp (ref "LED151")
      (value "42-21A/GHC-YX1Y2N/1T")
      (fields (field (name "Manufacturer") "EVERLIGHT(亿光)"))
      (libsource (lib "") (part "42-21A/GHC-YX1Y2N/1T"))
    )
    (comp (ref "LED152")
      (value "42-21A/GHC-YX1Y2N/1T")
      (fields (field (name "Manufacturer") "EVERLIGHT(亿光)"))
      (libsource (lib "") (part "42-21A/GHC-YX1Y2N/1T"))
    )
    (comp (ref "LED153")
      (value "42-21A/GHC-YX1Y2N/1T")
      (fields (field (name "Manufacturer") "EVERLIGHT(亿光)"))
      (libsource (lib "") (part "42-21A/GHC-YX1Y2N/1T"))
    )
    (comp (ref "LED154")
      (value "42-21A/GHC-YX1Y2N/1T")
      (fields (field (name "Manufacturer") "EVERLIGHT(亿光)"))
      (libsource (lib "") (part "42-21A/GHC-YX1Y2N/1T"))
    )
    (comp (ref "LED155")
      (value "42-21A/GHC-YX1Y2N/1T")
      (fields (field (name "Manufacturer") "EVERLIGHT(亿光)"))
      (libsource (lib "") (part "42-21A/GHC-YX1Y2N/1T"))
    )
    (comp (ref "LED156")
      (value "42-21A/GHC-YX1Y2N/1T")
      (fields (field (name "Manufacturer") "EVERLIGHT(亿光)"))
      (libsource (lib "") (part "42-21A/GHC-YX1Y2N/1T"))
    )
    (comp (ref "LED157")
      (value "42-21A/GHC-YX1Y2N/1T")
      (fields (field (name "Manufacturer") "EVERLIGHT(亿光)"))
      (libsource (lib "") (part "42-21A/GHC-YX1Y2N/1T"))
    )
    (comp (ref "LED158")
      (value "42-21A/GHC-YX1Y2N/1T")
      (fields (field (name "Manufacturer") "EVERLIGHT(亿光)"))
      (libsource (lib "") (part "42-21A/GHC-YX1Y2N/1T"))
    )
    (comp (ref "LED159")
      (value "42-21A/GHC-YX1Y2N/1T")
      (fields (field (name "Manufacturer") "EVERLIGHT(亿光)"))
      (libsource (lib "") (part "42-21A/GHC-YX1Y2N/1T"))
    )
    (comp (ref "LED160")
      (value "42-21A/GHC-YX1Y2N/1T")
      (fields (field (name "Manufacturer") "EVERLIGHT(亿光)"))
      (libsource (lib "") (part "42-21A/GHC-YX1Y2N/1T"))
    )
    (comp (ref "LED161")
      (value "42-21A/GHC-YX1Y2N/1T")
      (fields (field (name "Manufacturer") "EVERLIGHT(亿光)"))
      (libsource (lib "") (part "42-21A/GHC-YX1Y2N/1T"))
    )
    (comp (ref "LED162")
      (value "42-21A/GHC-YX1Y2N/1T")
      (fields (field (name "Manufacturer") "EVERLIGHT(亿光)"))
      (libsource (lib "") (part "42-21A/GHC-YX1Y2N/1T"))
    )
    (comp (ref "LED163")
      (value "42-21A/GHC-YX1Y2N/1T")
      (fields (field (name "Manufacturer") "EVERLIGHT(亿光)"))
      (libsource (lib "") (part "42-21A/GHC-YX1Y2N/1T"))
    )
    (comp (ref "LED164")
      (value "42-21A/GHC-YX1Y2N/1T")
      (fields (field (name "Manufacturer") "EVERLIGHT(亿光)"))
      (libsource (lib "") (part "42-21A/GHC-YX1Y2N/1T"))
    )
    (comp (ref "LED165")
      (value "42-21A/GHC-YX1Y2N/1T")
      (fields (field (name "Manufacturer") "EVERLIGHT(亿光)"))
      (libsource (lib "") (part "42-21A/GHC-YX1Y2N/1T"))
    )
    (comp (ref "LED166")
      (value "42-21A/GHC-YX1Y2N/1T")
      (fields (field (name "Manufacturer") "EVERLIGHT(亿光)"))
      (libsource (lib "") (part "42-21A/GHC-YX1Y2N/1T"))
    )
    (comp (ref "LED167")
      (value "42-21A/GHC-YX1Y2N/1T")
      (fields (field (name "Manufacturer") "EVERLIGHT(亿光)"))
      (libsource (lib "") (part "42-21A/GHC-YX1Y2N/1T"))
    )
    (comp (ref "LED168")
      (value "42-21A/GHC-YX1Y2N/1T")
      (fields (field (name "Manufacturer") "EVERLIGHT(亿光)"))
      (libsource (lib "") (part "42-21A/GHC-YX1Y2N/1T"))
    )
    (comp (ref "LED169")
      (value "42-21A/GHC-YX1Y2N/1T")
      (fields (field (name "Manufacturer") "EVERLIGHT(亿光)"))
      (libsource (lib "") (part "42-21A/GHC-YX1Y2N/1T"))
    )
    (comp (ref "LED170")
      (value "42-21A/GHC-YX1Y2N/1T")
      (fields (field (name "Manufacturer") "EVERLIGHT(亿光)"))
      (libsource (lib "") (part "42-21A/GHC-YX1Y2N/1T"))
    )
    (comp (ref "LED171")
      (value "42-21A/GHC-YX1Y2N/1T")
      (fields (field (name "Manufacturer") "EVERLIGHT(亿光)"))
      (libsource (lib "") (part "42-21A/GHC-YX1Y2N/1T"))
    )
    (comp (ref "LED172")
      (value "42-21A/GHC-YX1Y2N/1T")
      (fields (field (name "Manufacturer") "EVERLIGHT(亿光)"))
      (libsource (lib "") (part "42-21A/GHC-YX1Y2N/1T"))
    )
    (comp (ref "LED173")
      (value "42-21A/GHC-YX1Y2N/1T")
      (fields (field (name "Manufacturer") "EVERLIGHT(亿光)"))
      (libsource (lib "") (part "42-21A/GHC-YX1Y2N/1T"))
    )
    (comp (ref "LED174")
      (value "42-21A/GHC-YX1Y2N/1T")
      (fields (field (name "Manufacturer") "EVERLIGHT(亿光)"))
      (libsource (lib "") (part "42-21A/GHC-YX1Y2N/1T"))
    )
    (comp (ref "LED175")
      (value "42-21A/GHC-YX1Y2N/1T")
      (fields (field (name "Manufacturer") "EVERLIGHT(亿光)"))
      (libsource (lib "") (part "42-21A/GHC-YX1Y2N/1T"))
    )
    (comp (ref "LED176")
      (value "42-21A/GHC-YX1Y2N/1T")
      (fields (field (name "Manufacturer") "EVERLIGHT(亿光)"))
      (libsource (lib "") (part "42-21A/GHC-YX1Y2N/1T"))
    )
    (comp (ref "LED177")
      (value "42-21A/GHC-YX1Y2N/1T")
      (fields (field (name "Manufacturer") "EVERLIGHT(亿光)"))
      (libsource (lib "") (part "42-21A/GHC-YX1Y2N/1T"))
    )
    (comp (ref "LED178")
      (value "42-21A/GHC-YX1Y2N/1T")
      (fields (field (name "Manufacturer") "EVERLIGHT(亿光)"))
      (libsource (lib "") (part "42-21A/GHC-YX1Y2N/1T"))
    )
    (comp (ref "LED179")
      (value "42-21A/GHC-YX1Y2N/1T")
      (fields (field (name "Manufacturer") "EVERLIGHT(亿光)"))
      (libsource (lib "") (part "42-21A/GHC-YX1Y2N/1T"))
    )
    (comp (ref "LED180")
      (value "42-21A/GHC-YX1Y2N/1T")
      (fields (field (name "Manufacturer") "EVERLIGHT(亿光)"))
      (libsource (lib "") (part "42-21A/GHC-YX1Y2N/1T"))
    )
    (comp (ref "LED181")
      (value "42-21A/GHC-YX1Y2N/1T")
      (fields (field (name "Manufacturer") "EVERLIGHT(亿光)"))
      (libsource (lib "") (part "42-21A/GHC-YX1Y2N/1T"))
    )
    (comp (ref "LED182")
      (value "42-21A/GHC-YX1Y2N/1T")
      (fields (field (name "Manufacturer") "EVERLIGHT(亿光)"))
      (libsource (lib "") (part "42-21A/GHC-YX1Y2N/1T"))
    )
    (comp (ref "LED183")
      (value "42-21A/GHC-YX1Y2N/1T")
      (fields (field (name "Manufacturer") "EVERLIGHT(亿光)"))
      (libsource (lib "") (part "42-21A/GHC-YX1Y2N/1T"))
    )
    (comp (ref "LED184")
      (value "42-21A/GHC-YX1Y2N/1T")
      (fields (field (name "Manufacturer") "EVERLIGHT(亿光)"))
      (libsource (lib "") (part "42-21A/GHC-YX1Y2N/1T"))
    )
    (comp (ref "LED185")
      (value "42-21A/GHC-YX1Y2N/1T")
      (fields (field (name "Manufacturer") "EVERLIGHT(亿光)"))
      (libsource (lib "") (part "42-21A/GHC-YX1Y2N/1T"))
    )
    (comp (ref "LED186")
      (value "42-21A/GHC-YX1Y2N/1T")
      (fields (field (name "Manufacturer") "EVERLIGHT(亿光)"))
      (libsource (lib "") (part "42-21A/GHC-YX1Y2N/1T"))
    )
    (comp (ref "LED187")
      (value "42-21A/GHC-YX1Y2N/1T")
      (fields (field (name "Manufacturer") "EVERLIGHT(亿光)"))
      (libsource (lib "") (part "42-21A/GHC-YX1Y2N/1T"))
    )
    (comp (ref "LED188")
      (value "42-21A/GHC-YX1Y2N/1T")
      (fields (field (name "Manufacturer") "EVERLIGHT(亿光)"))
      (libsource (lib "") (part "42-21A/GHC-YX1Y2N/1T"))
    )
    (comp (ref "LED189")
      (value "42-21A/GHC-YX1Y2N/1T")
      (fields (field (name "Manufacturer") "EVERLIGHT(亿光)"))
      (libsource (lib "") (part "42-21A/GHC-YX1Y2N/1T"))
    )
    (comp (ref "LED190")
      (value "42-21A/GHC-YX1Y2N/1T")
      (fields (field (name "Manufacturer") "EVERLIGHT(亿光)"))
      (libsource (lib "") (part "42-21A/GHC-YX1Y2N/1T"))
    )
    (comp (ref "LED191")
      (value "42-21A/GHC-YX1Y2N/1T")
      (fields (field (name "Manufacturer") "EVERLIGHT(亿光)"))
      (libsource (lib "") (part "42-21A/GHC-YX1Y2N/1T"))
    )
    (comp (ref "LED192")
      (value "42-21A/GHC-YX1Y2N/1T")
      (fields (field (name "Manufacturer") "EVERLIGHT(亿光)"))
      (libsource (lib "") (part "42-21A/GHC-YX1Y2N/1T"))
    )
    (comp (ref "LED193")
      (value "42-21A/GHC-YX1Y2N/1T")
      (fields (field (name "Manufacturer") "EVERLIGHT(亿光)"))
      (libsource (lib "") (part "42-21A/GHC-YX1Y2N/1T"))
    )
    (comp (ref "LED194")
      (value "42-21A/GHC-YX1Y2N/1T")
      (fields (field (name "Manufacturer") "EVERLIGHT(亿光)"))
      (libsource (lib "") (part "42-21A/GHC-YX1Y2N/1T"))
    )
    (comp (ref "LED195")
      (value "42-21A/GHC-YX1Y2N/1T")
      (fields (field (name "Manufacturer") "EVERLIGHT(亿光)"))
      (libsource (lib "") (part "42-21A/GHC-YX1Y2N/1T"))
    )
    (comp (ref "LED196")
      (value "42-21A/GHC-YX1Y2N/1T")
      (fields (field (name "Manufacturer") "EVERLIGHT(亿光)"))
      (libsource (lib "") (part "42-21A/GHC-YX1Y2N/1T"))
    )
    (comp (ref "LED197")
      (value "42-21A/GHC-YX1Y2N/1T")
      (fields (field (name "Manufacturer") "EVERLIGHT(亿光)"))
      (libsource (lib "") (part "42-21A/GHC-YX1Y2N/1T"))
    )
    (comp (ref "LED198")
      (value "42-21A/GHC-YX1Y2N/1T")
      (fields (field (name "Manufacturer") "EVERLIGHT(亿光)"))
      (libsource (lib "") (part "42-21A/GHC-YX1Y2N/1T"))
    )
    (comp (ref "LED199")
      (value "42-21A/GHC-YX1Y2N/1T")
      (fields (field (name "Manufacturer") "EVERLIGHT(亿光)"))
      (libsource (lib "") (part "42-21A/GHC-YX1Y2N/1T"))
    )
    (comp (ref "LED200")
      (value "42-21A/GHC-YX1Y2N/1T")
      (fields (field (name "Manufacturer") "EVERLIGHT(亿光)"))
      (libsource (lib "") (part "42-21A/GHC-YX1Y2N/1T"))
    )
    (comp (ref "LED201")
      (value "42-21A/GHC-YX1Y2N/1T")
      (fields (field (name "Manufacturer") "EVERLIGHT(亿光)"))
      (libsource (lib "") (part "42-21A/GHC-YX1Y2N/1T"))
    )
    (comp (ref "LED202")
      (value "42-21A/GHC-YX1Y2N/1T")
      (fields (field (name "Manufacturer") "EVERLIGHT(亿光)"))
      (libsource (lib "") (part "42-21A/GHC-YX1Y2N/1T"))
    )
    (comp (ref "LED203")
      (value "42-21A/GHC-YX1Y2N/1T")
      (fields (field (name "Manufacturer") "EVERLIGHT(亿光)"))
      (libsource (lib "") (part "42-21A/GHC-YX1Y2N/1T"))
    )
    (comp (ref "LED204")
      (value "42-21A/GHC-YX1Y2N/1T")
      (fields (field (name "Manufacturer") "EVERLIGHT(亿光)"))
      (libsource (lib "") (part "42-21A/GHC-YX1Y2N/1T"))
    )
    (comp (ref "LED205")
      (value "42-21A/GHC-YX1Y2N/1T")
      (fields (field (name "Manufacturer") "EVERLIGHT(亿光)"))
      (libsource (lib "") (part "42-21A/GHC-YX1Y2N/1T"))
    )
    (comp (ref "LED206")
      (value "42-21A/GHC-YX1Y2N/1T")
      (fields (field (name "Manufacturer") "EVERLIGHT(亿光)"))
      (libsource (lib "") (part "42-21A/GHC-YX1Y2N/1T"))
    )
    (comp (ref "LED207")
      (value "42-21A/GHC-YX1Y2N/1T")
      (fields (field (name "Manufacturer") "EVERLIGHT(亿光)"))
      (libsource (lib "") (part "42-21A/GHC-YX1Y2N/1T"))
    )
    (comp (ref "LED208")
      (value "42-21A/GHC-YX1Y2N/1T")
      (fields (field (name "Manufacturer") "EVERLIGHT(亿光)"))
      (libsource (lib "") (part "42-21A/GHC-YX1Y2N/1T"))
    )
    (comp (ref "LED209")
      (value "42-21A/GHC-YX1Y2N/1T")
      (fields (field (name "Manufacturer") "EVERLIGHT(亿光)"))
      (libsource (lib "") (part "42-21A/GHC-YX1Y2N/1T"))
    )
    (comp (ref "LED210")
      (value "42-21A/GHC-YX1Y2N/1T")
      (fields (field (name "Manufacturer") "EVERLIGHT(亿光)"))
      (libsource (lib "") (part "42-21A/GHC-YX1Y2N/1T"))
    )
    (comp (ref "LED211")
      (value "42-21A/GHC-YX1Y2N/1T")
      (fields (field (name "Manufacturer") "EVERLIGHT(亿光)"))
      (libsource (lib "") (part "42-21A/GHC-YX1Y2N/1T"))
    )
    (comp (ref "LED212")
      (value "42-21A/GHC-YX1Y2N/1T")
      (fields (field (name "Manufacturer") "EVERLIGHT(亿光)"))
      (libsource (lib "") (part "42-21A/GHC-YX1Y2N/1T"))
    )
    (comp (ref "LED213")
      (value "42-21A/GHC-YX1Y2N/1T")
      (fields (field (name "Manufacturer") "EVERLIGHT(亿光)"))
      (libsource (lib "") (part "42-21A/GHC-YX1Y2N/1T"))
    )
    (comp (ref "LED214")
      (value "42-21A/GHC-YX1Y2N/1T")
      (fields (field (name "Manufacturer") "EVERLIGHT(亿光)"))
      (libsource (lib "") (part "42-21A/GHC-YX1Y2N/1T"))
    )
    (comp (ref "LED215")
      (value "42-21A/GHC-YX1Y2N/1T")
      (fields (field (name "Manufacturer") "EVERLIGHT(亿光)"))
      (libsource (lib "") (part "42-21A/GHC-YX1Y2N/1T"))
    )
    (comp (ref "LED216")
      (value "42-21A/GHC-YX1Y2N/1T")
      (fields (field (name "Manufacturer") "EVERLIGHT(亿光)"))
      (libsource (lib "") (part "42-21A/GHC-YX1Y2N/1T"))
    )
    (comp (ref "LED217")
      (value "42-21A/GHC-YX1Y2N/1T")
      (fields (field (name "Manufacturer") "EVERLIGHT(亿光)"))
      (libsource (lib "") (part "42-21A/GHC-YX1Y2N/1T"))
    )
    (comp (ref "LED218")
      (value "42-21A/GHC-YX1Y2N/1T")
      (fields (field (name "Manufacturer") "EVERLIGHT(亿光)"))
      (libsource (lib "") (part "42-21A/GHC-YX1Y2N/1T"))
    )
    (comp (ref "LED219")
      (value "42-21A/GHC-YX1Y2N/1T")
      (fields (field (name "Manufacturer") "EVERLIGHT(亿光)"))
      (libsource (lib "") (part "42-21A/GHC-YX1Y2N/1T"))
    )
    (comp (ref "LED220")
      (value "42-21A/GHC-YX1Y2N/1T")
      (fields (field (name "Manufacturer") "EVERLIGHT(亿光)"))
      (libsource (lib "") (part "42-21A/GHC-YX1Y2N/1T"))
    )
    (comp (ref "LED221")
      (value "42-21A/GHC-YX1Y2N/1T")
      (fields (field (name "Manufacturer") "EVERLIGHT(亿光)"))
      (libsource (lib "") (part "42-21A/GHC-YX1Y2N/1T"))
    )
    (comp (ref "LED222")
      (value "42-21A/GHC-YX1Y2N/1T")
      (fields (field (name "Manufacturer") "EVERLIGHT(亿光)"))
      (libsource (lib "") (part "42-21A/GHC-YX1Y2N/1T"))
    )
    (comp (ref "LED223")
      (value "42-21A/GHC-YX1Y2N/1T")
      (fields (field (name "Manufacturer") "EVERLIGHT(亿光)"))
      (libsource (lib "") (part "42-21A/GHC-YX1Y2N/1T"))
    )
    (comp (ref "LED224")
      (value "42-21A/GHC-YX1Y2N/1T")
      (fields (field (name "Manufacturer") "EVERLIGHT(亿光)"))
      (libsource (lib "") (part "42-21A/GHC-YX1Y2N/1T"))
    )
    (comp (ref "LED225")
      (value "42-21A/GHC-YX1Y2N/1T")
      (fields (field (name "Manufacturer") "EVERLIGHT(亿光)"))
      (libsource (lib "") (part "42-21A/GHC-YX1Y2N/1T"))
    )
    (comp (ref "LED226")
      (value "42-21A/GHC-YX1Y2N/1T")
      (fields (field (name "Manufacturer") "EVERLIGHT(亿光)"))
      (libsource (lib "") (part "42-21A/GHC-YX1Y2N/1T"))
    )
    (comp (ref "LED227")
      (value "42-21A/GHC-YX1Y2N/1T")
      (fields (field (name "Manufacturer") "EVERLIGHT(亿光)"))
      (libsource (lib "") (part "42-21A/GHC-YX1Y2N/1T"))
    )
    (comp (ref "LED228")
      (value "42-21A/GHC-YX1Y2N/1T")
      (fields (field (name "Manufacturer") "EVERLIGHT(亿光)"))
      (libsource (lib "") (part "42-21A/GHC-YX1Y2N/1T"))
    )
    (comp (ref "LED229")
      (value "42-21A/GHC-YX1Y2N/1T")
      (fields (field (name "Manufacturer") "EVERLIGHT(亿光)"))
      (libsource (lib "") (part "42-21A/GHC-YX1Y2N/1T"))
    )
    (comp (ref "LED230")
      (value "42-21A/GHC-YX1Y2N/1T")
      (fields (field (name "Manufacturer") "EVERLIGHT(亿光)"))
      (libsource (lib "") (part "42-21A/GHC-YX1Y2N/1T"))
    )
    (comp (ref "LED231")
      (value "42-21A/GHC-YX1Y2N/1T")
      (fields (field (name "Manufacturer") "EVERLIGHT(亿光)"))
      (libsource (lib "") (part "42-21A/GHC-YX1Y2N/1T"))
    )
    (comp (ref "LED232")
      (value "42-21A/GHC-YX1Y2N/1T")
      (fields (field (name "Manufacturer") "EVERLIGHT(亿光)"))
      (libsource (lib "") (part "42-21A/GHC-YX1Y2N/1T"))
    )
    (comp (ref "LED233")
      (value "42-21A/GHC-YX1Y2N/1T")
      (fields (field (name "Manufacturer") "EVERLIGHT(亿光)"))
      (libsource (lib "") (part "42-21A/GHC-YX1Y2N/1T"))
    )
    (comp (ref "LED234")
      (value "42-21A/GHC-YX1Y2N/1T")
      (fields (field (name "Manufacturer") "EVERLIGHT(亿光)"))
      (libsource (lib "") (part "42-21A/GHC-YX1Y2N/1T"))
    )
    (comp (ref "LED235")
      (value "42-21A/GHC-YX1Y2N/1T")
      (fields (field (name "Manufacturer") "EVERLIGHT(亿光)"))
      (libsource (lib "") (part "42-21A/GHC-YX1Y2N/1T"))
    )
    (comp (ref "LED236")
      (value "42-21A/GHC-YX1Y2N/1T")
      (fields (field (name "Manufacturer") "EVERLIGHT(亿光)"))
      (libsource (lib "") (part "42-21A/GHC-YX1Y2N/1T"))
    )
    (comp (ref "LED237")
      (value "42-21A/GHC-YX1Y2N/1T")
      (fields (field (name "Manufacturer") "EVERLIGHT(亿光)"))
      (libsource (lib "") (part "42-21A/GHC-YX1Y2N/1T"))
    )
    (comp (ref "LED238")
      (value "42-21A/GHC-YX1Y2N/1T")
      (fields (field (name "Manufacturer") "EVERLIGHT(亿光)"))
      (libsource (lib "") (part "42-21A/GHC-YX1Y2N/1T"))
    )
    (comp (ref "LED239")
      (value "42-21A/GHC-YX1Y2N/1T")
      (fields (field (name "Manufacturer") "EVERLIGHT(亿光)"))
      (libsource (lib "") (part "42-21A/GHC-YX1Y2N/1T"))
    )
    (comp (ref "LED240")
      (value "42-21A/GHC-YX1Y2N/1T")
      (fields (field (name "Manufacturer") "EVERLIGHT(亿光)"))
      (libsource (lib "") (part "42-21A/GHC-YX1Y2N/1T"))
    )
    (comp (ref "LED241")
      (value "42-21A/GHC-YX1Y2N/1T")
      (fields (field (name "Manufacturer") "EVERLIGHT(亿光)"))
      (libsource (lib "") (part "42-21A/GHC-YX1Y2N/1T"))
    )
    (comp (ref "LED242")
      (value "42-21A/GHC-YX1Y2N/1T")
      (fields (field (name "Manufacturer") "EVERLIGHT(亿光)"))
      (libsource (lib "") (part "42-21A/GHC-YX1Y2N/1T"))
    )
    (comp (ref "LED243")
      (value "42-21A/GHC-YX1Y2N/1T")
      (fields (field (name "Manufacturer") "EVERLIGHT(亿光)"))
      (libsource (lib "") (part "42-21A/GHC-YX1Y2N/1T"))
    )
    (comp (ref "LED244")
      (value "42-21A/GHC-YX1Y2N/1T")
      (fields (field (name "Manufacturer") "EVERLIGHT(亿光)"))
      (libsource (lib "") (part "42-21A/GHC-YX1Y2N/1T"))
    )
    (comp (ref "LED245")
      (value "42-21A/GHC-YX1Y2N/1T")
      (fields (field (name "Manufacturer") "EVERLIGHT(亿光)"))
      (libsource (lib "") (part "42-21A/GHC-YX1Y2N/1T"))
    )
    (comp (ref "LED246")
      (value "42-21A/GHC-YX1Y2N/1T")
      (fields (field (name "Manufacturer") "EVERLIGHT(亿光)"))
      (libsource (lib "") (part "42-21A/GHC-YX1Y2N/1T"))
    )
    (comp (ref "LED247")
      (value "42-21A/GHC-YX1Y2N/1T")
      (fields (field (name "Manufacturer") "EVERLIGHT(亿光)"))
      (libsource (lib "") (part "42-21A/GHC-YX1Y2N/1T"))
    )
    (comp (ref "LED248")
      (value "42-21A/GHC-YX1Y2N/1T")
      (fields (field (name "Manufacturer") "EVERLIGHT(亿光)"))
      (libsource (lib "") (part "42-21A/GHC-YX1Y2N/1T"))
    )
    (comp (ref "LED249")
      (value "42-21A/GHC-YX1Y2N/1T")
      (fields (field (name "Manufacturer") "EVERLIGHT(亿光)"))
      (libsource (lib "") (part "42-21A/GHC-YX1Y2N/1T"))
    )
    (comp (ref "LED250")
      (value "42-21A/GHC-YX1Y2N/1T")
      (fields (field (name "Manufacturer") "EVERLIGHT(亿光)"))
      (libsource (lib "") (part "42-21A/GHC-YX1Y2N/1T"))
    )
    (comp (ref "LED251")
      (value "42-21A/GHC-YX1Y2N/1T")
      (fields (field (name "Manufacturer") "EVERLIGHT(亿光)"))
      (libsource (lib "") (part "42-21A/GHC-YX1Y2N/1T"))
    )
    (comp (ref "LED252")
      (value "42-21A/GHC-YX1Y2N/1T")
      (fields (field (name "Manufacturer") "EVERLIGHT(亿光)"))
      (libsource (lib "") (part "42-21A/GHC-YX1Y2N/1T"))
    )
    (comp (ref "LED253")
      (value "42-21A/GHC-YX1Y2N/1T")
      (fields (field (name "Manufacturer") "EVERLIGHT(亿光)"))
      (libsource (lib "") (part "42-21A/GHC-YX1Y2N/1T"))
    )
    (comp (ref "LED254")
      (value "42-21A/GHC-YX1Y2N/1T")
      (fields (field (name "Manufacturer") "EVERLIGHT(亿光)"))
      (libsource (lib "") (part "42-21A/GHC-YX1Y2N/1T"))
    )
    (comp (ref "LED255")
      (value "42-21A/GHC-YX1Y2N/1T")
      (fields (field (name "Manufacturer") "EVERLIGHT(亿光)"))
      (libsource (lib "") (part "42-21A/GHC-YX1Y2N/1T"))
    )
    (comp (ref "LED256")
      (value "42-21A/GHC-YX1Y2N/1T")
      (fields (field (name "Manufacturer") "EVERLIGHT(亿光)"))
      (libsource (lib "") (part "42-21A/GHC-YX1Y2N/1T"))
    )
    (comp (ref "Q1")
      (value "IRLZ44NPBF-MNS")
      (fields (field (name "Manufacturer") "minos(迈诺斯)"))
      (libsource (lib "") (part "IRLZ44NPBF-MNS"))
    )
    (comp (ref "Q2")
      (value "IRLZ44NPBF-MNS")
      (fields (field (name "Manufacturer") "minos(迈诺斯)"))
      (libsource (lib "") (part "IRLZ44NPBF-MNS"))
    )
    (comp (ref "Q3")
      (value "IRLZ44NPBF-MNS")
      (fields (field (name "Manufacturer") "minos(迈诺斯)"))
      (libsource (lib "") (part "IRLZ44NPBF-MNS"))
    )
    (comp (ref "Q4")
      (value "IRLZ44NPBF-MNS")
      (fields (field (name "Manufacturer") "minos(迈诺斯)"))
      (libsource (lib "") (part "IRLZ44NPBF-MNS"))
    )
    (comp (ref "Q5")
      (value "IRLZ44NPBF-MNS")
      (fields (field (name "Manufacturer") "minos(迈诺斯)"))
      (libsource (lib "") (part "IRLZ44NPBF-MNS"))
    )
    (comp (ref "Q6")
      (value "IRLZ44NPBF-MNS")
      (fields (field (name "Manufacturer") "minos(迈诺斯)"))
      (libsource (lib "") (part "IRLZ44NPBF-MNS"))
    )
    (comp (ref "Q7")
      (value "IRLZ44NPBF-MNS")
      (fields (field (name "Manufacturer") "minos(迈诺斯)"))
      (libsource (lib "") (part "IRLZ44NPBF-MNS"))
    )
    (comp (ref "Q8")
      (value "IRLZ44NPBF-MNS")
      (fields (field (name "Manufacturer") "minos(迈诺斯)"))
      (libsource (lib "") (part "IRLZ44NPBF-MNS"))
    )
    (comp (ref "Q9")
      (value "IRLZ44NPBF-MNS")
      (fields (field (name "Manufacturer") "minos(迈诺斯)"))
      (libsource (lib "") (part "IRLZ44NPBF-MNS"))
    )
    (comp (ref "Q10")
      (value "IRLZ44NPBF-MNS")
      (fields (field (name "Manufacturer") "minos(迈诺斯)"))
      (libsource (lib "") (part "IRLZ44NPBF-MNS"))
    )
    (comp (ref "Q11")
      (value "IRLZ44NPBF-MNS")
      (fields (field (name "Manufacturer") "minos(迈诺斯)"))
      (libsource (lib "") (part "IRLZ44NPBF-MNS"))
    )
    (comp (ref "Q12")
      (value "IRLZ44NPBF-MNS")
      (fields (field (name "Manufacturer") "minos(迈诺斯)"))
      (libsource (lib "") (part "IRLZ44NPBF-MNS"))
    )
    (comp (ref "Q13")
      (value "IRLZ44NPBF-MNS")
      (fields (field (name "Manufacturer") "minos(迈诺斯)"))
      (libsource (lib "") (part "IRLZ44NPBF-MNS"))
    )
    (comp (ref "Q14")
      (value "IRLZ44NPBF-MNS")
      (fields (field (name "Manufacturer") "minos(迈诺斯)"))
      (libsource (lib "") (part "IRLZ44NPBF-MNS"))
    )
    (comp (ref "Q15")
      (value "IRLZ44NPBF-MNS")
      (fields (field (name "Manufacturer") "minos(迈诺斯)"))
      (libsource (lib "") (part "IRLZ44NPBF-MNS"))
    )
    (comp (ref "Q16")
      (value "IRLZ44NPBF-MNS")
      (fields (field (name "Manufacturer") "minos(迈诺斯)"))
      (libsource (lib "") (part "IRLZ44NPBF-MNS"))
    )
    (comp (ref "Q17")
      (value "AO3401CI-ES")
      (fields (field (name "Manufacturer") "ElecSuper(静芯)"))
      (libsource (lib "") (part "AO3401CI-ES"))
    )
    (comp (ref "Q18")
      (value "2N7000-TA")
      (fields (field (name "Manufacturer") "CJ(江苏长电/长晶)"))
      (libsource (lib "") (part "2N7000-TA"))
    )
    (comp (ref "Q19")
      (value "AO3401CI-ES")
      (fields (field (name "Manufacturer") "ElecSuper(静芯)"))
      (libsource (lib "") (part "AO3401CI-ES"))
    )
    (comp (ref "Q20")
      (value "AO3401CI-ES")
      (fields (field (name "Manufacturer") "ElecSuper(静芯)"))
      (libsource (lib "") (part "AO3401CI-ES"))
    )
    (comp (ref "Q21")
      (value "AO3401CI-ES")
      (fields (field (name "Manufacturer") "ElecSuper(静芯)"))
      (libsource (lib "") (part "AO3401CI-ES"))
    )
    (comp (ref "Q22")
      (value "AO3401CI-ES")
      (fields (field (name "Manufacturer") "ElecSuper(静芯)"))
      (libsource (lib "") (part "AO3401CI-ES"))
    )
    (comp (ref "Q23")
      (value "AO3401CI-ES")
      (fields (field (name "Manufacturer") "ElecSuper(静芯)"))
      (libsource (lib "") (part "AO3401CI-ES"))
    )
    (comp (ref "Q24")
      (value "AO3401CI-ES")
      (fields (field (name "Manufacturer") "ElecSuper(静芯)"))
      (libsource (lib "") (part "AO3401CI-ES"))
    )
    (comp (ref "Q25")
      (value "AO3401CI-ES")
      (fields (field (name "Manufacturer") "ElecSuper(静芯)"))
      (libsource (lib "") (part "AO3401CI-ES"))
    )
    (comp (ref "Q26")
      (value "AO3401CI-ES")
      (fields (field (name "Manufacturer") "ElecSuper(静芯)"))
      (libsource (lib "") (part "AO3401CI-ES"))
    )
    (comp (ref "Q27")
      (value "AO3401CI-ES")
      (fields (field (name "Manufacturer") "ElecSuper(静芯)"))
      (libsource (lib "") (part "AO3401CI-ES"))
    )
    (comp (ref "Q28")
      (value "AO3401CI-ES")
      (fields (field (name "Manufacturer") "ElecSuper(静芯)"))
      (libsource (lib "") (part "AO3401CI-ES"))
    )
    (comp (ref "Q29")
      (value "AO3401CI-ES")
      (fields (field (name "Manufacturer") "ElecSuper(静芯)"))
      (libsource (lib "") (part "AO3401CI-ES"))
    )
    (comp (ref "Q30")
      (value "AO3401CI-ES")
      (fields (field (name "Manufacturer") "ElecSuper(静芯)"))
      (libsource (lib "") (part "AO3401CI-ES"))
    )
    (comp (ref "Q31")
      (value "AO3401CI-ES")
      (fields (field (name "Manufacturer") "ElecSuper(静芯)"))
      (libsource (lib "") (part "AO3401CI-ES"))
    )
    (comp (ref "Q32")
      (value "AO3401CI-ES")
      (fields (field (name "Manufacturer") "ElecSuper(静芯)"))
      (libsource (lib "") (part "AO3401CI-ES"))
    )
    (comp (ref "Q33")
      (value "AO3401CI-ES")
      (fields (field (name "Manufacturer") "ElecSuper(静芯)"))
      (libsource (lib "") (part "AO3401CI-ES"))
    )
    (comp (ref "R1")
      (value "10k")
      (fields (field (name "Manufacturer Part") "MFR-12FTF52-10K") (field (name "Manufacturer") "YAGEO(国巨)"))
      (libsource (lib "") (part "R_0603_EU"))
    )
    (comp (ref "R2")
      (value "10k")
      (fields (field (name "Manufacturer Part") "MFR-12FTF52-10K") (field (name "Manufacturer") "YAGEO(国巨)"))
      (libsource (lib "") (part "R_0603_EU"))
    )
    (comp (ref "R3")
      (value "10k")
      (fields (field (name "Manufacturer Part") "MFR-12FTF52-10K") (field (name "Manufacturer") "YAGEO(国巨)"))
      (libsource (lib "") (part "R_0603_EU"))
    )
    (comp (ref "R4")
      (value "10k")
      (fields (field (name "Manufacturer Part") "MFR-12FTF52-10K") (field (name "Manufacturer") "YAGEO(国巨)"))
      (libsource (lib "") (part "R_0603_EU"))
    )
    (comp (ref "R5")
      (value "10k")
      (fields (field (name "Manufacturer Part") "MFR-12FTF52-10K") (field (name "Manufacturer") "YAGEO(国巨)"))
      (libsource (lib "") (part "R_0603_EU"))
    )
    (comp (ref "R6")
      (value "10k")
      (fields (field (name "Manufacturer Part") "MFR-12FTF52-10K") (field (name "Manufacturer") "YAGEO(国巨)"))
      (libsource (lib "") (part "R_0603_EU"))
    )
    (comp (ref "R7")
      (value "10k")
      (fields (field (name "Manufacturer Part") "MFR-12FTF52-10K") (field (name "Manufacturer") "YAGEO(国巨)"))
      (libsource (lib "") (part "R_0603_EU"))
    )
    (comp (ref "R8")
      (value "10k")
      (fields (field (name "Manufacturer Part") "MFR-12FTF52-10K") (field (name "Manufacturer") "YAGEO(国巨)"))
      (libsource (lib "") (part "R_0603_EU"))
    )
    (comp (ref "R9")
      (value "10k")
      (fields (field (name "Manufacturer Part") "MFR-12FTF52-10K") (field (name "Manufacturer") "YAGEO(国巨)"))
      (libsource (lib "") (part "R_0603_EU"))
    )
    (comp (ref "R10")
      (value "10k")
      (fields (field (name "Manufacturer Part") "MFR-12FTF52-10K") (field (name "Manufacturer") "YAGEO(国巨)"))
      (libsource (lib "") (part "R_0603_EU"))
    )
    (comp (ref "R11")
      (value "10k")
      (fields (field (name "Manufacturer Part") "MFR-12FTF52-10K") (field (name "Manufacturer") "YAGEO(国巨)"))
      (libsource (lib "") (part "R_0603_EU"))
    )
    (comp (ref "R12")
      (value "10k")
      (fields (field (name "Manufacturer Part") "MFR-12FTF52-10K") (field (name "Manufacturer") "YAGEO(国巨)"))
      (libsource (lib "") (part "R_0603_EU"))
    )
    (comp (ref "R13")
      (value "10k")
      (fields (field (name "Manufacturer Part") "MFR-12FTF52-10K") (field (name "Manufacturer") "YAGEO(国巨)"))
      (libsource (lib "") (part "R_0603_EU"))
    )
    (comp (ref "R14")
      (value "10k")
      (fields (field (name "Manufacturer Part") "MFR-12FTF52-10K") (field (name "Manufacturer") "YAGEO(国巨)"))
      (libsource (lib "") (part "R_0603_EU"))
    )
    (comp (ref "R15")
      (value "10k")
      (fields (field (name "Manufacturer Part") "MFR-12FTF52-10K") (field (name "Manufacturer") "YAGEO(国巨)"))
      (libsource (lib "") (part "R_0603_EU"))
    )
    (comp (ref "R16")
      (value "10k")
      (fields (field (name "Manufacturer Part") "MFR-12FTF52-10K") (field (name "Manufacturer") "YAGEO(国巨)"))
      (libsource (lib "") (part "R_0603_EU"))
    )
    (comp (ref "R17")
      (value "10k")
      (fields (field (name "Manufacturer Part") "MFR-12FTF52-10K") (field (name "Manufacturer") "YAGEO(国巨)"))
      (libsource (lib "") (part "R_0603_EU_2"))
    )
    (comp (ref "R18")
      (value "10k")
      (fields (field (name "Manufacturer Part") "MFR-12FTF52-10K") (field (name "Manufacturer") "YAGEO(国巨)"))
      (libsource (lib "") (part "R_0603_EU_1"))
    )
    (comp (ref "R19")
      (value "15Ω")
      (fields (field (name "Manufacturer Part") "MF1/4W-15Ω±1% T") (field (name "Manufacturer") "CCO(千志电子)"))
      (libsource (lib "") (part "MF1/4W-15Ω±1% T52"))
    )
    (comp (ref "R20")
      (value "10k")
      (fields (field (name "Manufacturer Part") "MFR-12FTF52-10K") (field (name "Manufacturer") "YAGEO(国巨)"))
      (libsource (lib "") (part "R_0603_EU_1"))
    )
    (comp (ref "R21")
      (value "10k")
      (fields (field (name "Manufacturer Part") "MFR-12FTF52-10K") (field (name "Manufacturer") "YAGEO(国巨)"))
      (libsource (lib "") (part "R_0603_EU_1"))
    )
    (comp (ref "R22")
      (value "15Ω")
      (fields (field (name "Manufacturer Part") "MF1/4W-15Ω±1% T") (field (name "Manufacturer") "CCO(千志电子)"))
      (libsource (lib "") (part "MF1/4W-15Ω±1% T52"))
    )
    (comp (ref "R23")
      (value "10k")
      (fields (field (name "Manufacturer Part") "MFR-12FTF52-10K") (field (name "Manufacturer") "YAGEO(国巨)"))
      (libsource (lib "") (part "R_0603_EU_1"))
    )
    (comp (ref "R24")
      (value "15Ω")
      (fields (field (name "Manufacturer Part") "MF1/4W-15Ω±1% T") (field (name "Manufacturer") "CCO(千志电子)"))
      (libsource (lib "") (part "MF1/4W-15Ω±1% T52"))
    )
    (comp (ref "R25")
      (value "10k")
      (fields (field (name "Manufacturer Part") "MFR-12FTF52-10K") (field (name "Manufacturer") "YAGEO(国巨)"))
      (libsource (lib "") (part "R_0603_EU_1"))
    )
    (comp (ref "R26")
      (value "10k")
      (fields (field (name "Manufacturer Part") "MFR-12FTF52-10K") (field (name "Manufacturer") "YAGEO(国巨)"))
      (libsource (lib "") (part "R_0603_EU"))
    )
    (comp (ref "R27")
      (value "15Ω")
      (fields (field (name "Manufacturer Part") "MF1/4W-15Ω±1% T") (field (name "Manufacturer") "CCO(千志电子)"))
      (libsource (lib "") (part "MF1/4W-15Ω±1% T52"))
    )
    (comp (ref "R28")
      (value "10k")
      (fields (field (name "Manufacturer Part") "MFR-12FTF52-10K") (field (name "Manufacturer") "YAGEO(国巨)"))
      (libsource (lib "") (part "R_0603_EU_1"))
    )
    (comp (ref "R29")
      (value "1M")
      (fields (field (name "Manufacturer Part") "FRC2512F1004TS") (field (name "Manufacturer") "FOJAN(富捷)"))
      (libsource (lib "") (part "R_0603_EU_1"))
    )
    (comp (ref "R30")
      (value "2.2k")
      (fields (field (name "Manufacturer Part") "MF0204FTE52-2K2") (field (name "Manufacturer") "YAGEO(国巨)"))
      (libsource (lib "") (part "R_0603_EU"))
    )
    (comp (ref "R31")
      (value "15Ω")
      (fields (field (name "Manufacturer Part") "MF1/4W-15Ω±1% T") (field (name "Manufacturer") "CCO(千志电子)"))
      (libsource (lib "") (part "MF1/4W-15Ω±1% T52"))
    )
    (comp (ref "R32")
      (value "10k")
      (fields (field (name "Manufacturer Part") "MFR-12FTF52-10K") (field (name "Manufacturer") "YAGEO(国巨)"))
      (libsource (lib "") (part "R_0603_EU_1"))
    )
    (comp (ref "R33")
      (value "10k")
      (fields (field (name "Manufacturer Part") "MFR-12FTF52-10K") (field (name "Manufacturer") "YAGEO(国巨)"))
      (libsource (lib "") (part "R_0603_EU_1"))
    )
    (comp (ref "R34")
      (value "15Ω")
      (fields (field (name "Manufacturer Part") "MF1/4W-15Ω±1% T") (field (name "Manufacturer") "CCO(千志电子)"))
      (libsource (lib "") (part "MF1/4W-15Ω±1% T52"))
    )
    (comp (ref "R35")
      (value "10k")
      (fields (field (name "Manufacturer Part") "MFR-12FTF52-10K") (field (name "Manufacturer") "YAGEO(国巨)"))
      (libsource (lib "") (part "R_0603_EU_1"))
    )
    (comp (ref "R36")
      (value "10k")
      (fields (field (name "Manufacturer Part") "MFR-12FTF52-10K") (field (name "Manufacturer") "YAGEO(国巨)"))
      (libsource (lib "") (part "R_0603_EU_1"))
    )
    (comp (ref "R37")
      (value "10k")
      (fields (field (name "Manufacturer Part") "MFR-12FTF52-10K") (field (name "Manufacturer") "YAGEO(国巨)"))
      (libsource (lib "") (part "R_0603_EU_1"))
    )
    (comp (ref "R38")
      (value "15Ω")
      (fields (field (name "Manufacturer Part") "MF1/4W-15Ω±1% T") (field (name "Manufacturer") "CCO(千志电子)"))
      (libsource (lib "") (part "MF1/4W-15Ω±1% T52"))
    )
    (comp (ref "R39")
      (value "10k")
      (fields (field (name "Manufacturer Part") "MFR-12FTF52-10K") (field (name "Manufacturer") "YAGEO(国巨)"))
      (libsource (lib "") (part "R_0603_EU_1"))
    )
    (comp (ref "R40")
      (value "15Ω")
      (fields (field (name "Manufacturer Part") "MF1/4W-15Ω±1% T") (field (name "Manufacturer") "CCO(千志电子)"))
      (libsource (lib "") (part "MF1/4W-15Ω±1% T52"))
    )
    (comp (ref "R41")
      (value "10k")
      (fields (field (name "Manufacturer Part") "MFR-12FTF52-10K") (field (name "Manufacturer") "YAGEO(国巨)"))
      (libsource (lib "") (part "R_0603_EU_1"))
    )
    (comp (ref "R42")
      (value "15Ω")
      (fields (field (name "Manufacturer Part") "MF1/4W-15Ω±1% T") (field (name "Manufacturer") "CCO(千志电子)"))
      (libsource (lib "") (part "MF1/4W-15Ω±1% T52"))
    )
    (comp (ref "R43")
      (value "10k")
      (fields (field (name "Manufacturer Part") "MFR-12FTF52-10K") (field (name "Manufacturer") "YAGEO(国巨)"))
      (libsource (lib "") (part "R_0603_EU_1"))
    )
    (comp (ref "R44")
      (value "10k")
      (fields (field (name "Manufacturer Part") "MFR-12FTF52-10K") (field (name "Manufacturer") "YAGEO(国巨)"))
      (libsource (lib "") (part "R_0603_EU_1"))
    )
    (comp (ref "R45")
      (value "10k")
      (fields (field (name "Manufacturer Part") "MFR-12FTF52-10K") (field (name "Manufacturer") "YAGEO(国巨)"))
      (libsource (lib "") (part "R_0603_EU_1"))
    )
    (comp (ref "R46")
      (value "10k")
      (fields (field (name "Manufacturer Part") "MFR-12FTF52-10K") (field (name "Manufacturer") "YAGEO(国巨)"))
      (libsource (lib "") (part "R_0603_EU_1"))
    )
    (comp (ref "R47")
      (value "10k")
      (fields (field (name "Manufacturer Part") "MFR-12FTF52-10K") (field (name "Manufacturer") "YAGEO(国巨)"))
      (libsource (lib "") (part "R_0603_EU_1"))
    )
    (comp (ref "R48")
      (value "10k")
      (fields (field (name "Manufacturer Part") "MFR-12FTF52-10K") (field (name "Manufacturer") "YAGEO(国巨)"))
      (libsource (lib "") (part "R_0603_EU_1"))
    )
    (comp (ref "R49")
      (value "15Ω")
      (fields (field (name "Manufacturer Part") "MF1/4W-15Ω±1% T") (field (name "Manufacturer") "CCO(千志电子)"))
      (libsource (lib "") (part "MF1/4W-15Ω±1% T52"))
    )
    (comp (ref "R50")
      (value "10k")
      (fields (field (name "Manufacturer Part") "MFR-12FTF52-10K") (field (name "Manufacturer") "YAGEO(国巨)"))
      (libsource (lib "") (part "R_0603_EU_1"))
    )
    (comp (ref "R51")
      (value "10k")
      (fields (field (name "Manufacturer Part") "MFR-12FTF52-10K") (field (name "Manufacturer") "YAGEO(国巨)"))
      (libsource (lib "") (part "R_0603_EU_1"))
    )
    (comp (ref "R52")
      (value "10k")
      (fields (field (name "Manufacturer Part") "MFR-12FTF52-10K") (field (name "Manufacturer") "YAGEO(国巨)"))
      (libsource (lib "") (part "R_0603_EU_1"))
    )
    (comp (ref "R53")
      (value "10k")
      (fields (field (name "Manufacturer Part") "MFR-12FTF52-10K") (field (name "Manufacturer") "YAGEO(国巨)"))
      (libsource (lib "") (part "R_0603_EU_1"))
    )
    (comp (ref "R54")
      (value "15Ω")
      (fields (field (name "Manufacturer Part") "MF1/4W-15Ω±1% T") (field (name "Manufacturer") "CCO(千志电子)"))
      (libsource (lib "") (part "MF1/4W-15Ω±1% T52"))
    )
    (comp (ref "R55")
      (value "10k")
      (fields (field (name "Manufacturer Part") "MFR-12FTF52-10K") (field (name "Manufacturer") "YAGEO(国巨)"))
      (libsource (lib "") (part "R_0603_EU_1"))
    )
    (comp (ref "R56")
      (value "10k")
      (fields (field (name "Manufacturer Part") "MFR-12FTF52-10K") (field (name "Manufacturer") "YAGEO(国巨)"))
      (libsource (lib "") (part "R_0603_EU_1"))
    )
    (comp (ref "R57")
      (value "10k")
      (fields (field (name "Manufacturer Part") "MFR-12FTF52-10K") (field (name "Manufacturer") "YAGEO(国巨)"))
      (libsource (lib "") (part "R_0603_EU_1"))
    )
    (comp (ref "R58")
      (value "10k")
      (fields (field (name "Manufacturer Part") "MFR-12FTF52-10K") (field (name "Manufacturer") "YAGEO(国巨)"))
      (libsource (lib "") (part "R_0603_EU_1"))
    )
    (comp (ref "R59")
      (value "10k")
      (fields (field (name "Manufacturer Part") "MFR-12FTF52-10K") (field (name "Manufacturer") "YAGEO(国巨)"))
      (libsource (lib "") (part "R_0603_EU_1"))
    )
    (comp (ref "R60")
      (value "15Ω")
      (fields (field (name "Manufacturer Part") "MF1/4W-15Ω±1% T") (field (name "Manufacturer") "CCO(千志电子)"))
      (libsource (lib "") (part "MF1/4W-15Ω±1% T52"))
    )
    (comp (ref "R61")
      (value "10k")
      (fields (field (name "Manufacturer Part") "MFR-12FTF52-10K") (field (name "Manufacturer") "YAGEO(国巨)"))
      (libsource (lib "") (part "R_0603_EU_1"))
    )
    (comp (ref "R62")
      (value "15Ω")
      (fields (field (name "Manufacturer Part") "MF1/4W-15Ω±1% T") (field (name "Manufacturer") "CCO(千志电子)"))
      (libsource (lib "") (part "MF1/4W-15Ω±1% T52"))
    )
    (comp (ref "R63")
      (value "10k")
      (fields (field (name "Manufacturer Part") "MFR-12FTF52-10K") (field (name "Manufacturer") "YAGEO(国巨)"))
      (libsource (lib "") (part "R_0603_EU_1"))
    )
    (comp (ref "R64")
      (value "15Ω")
      (fields (field (name "Manufacturer Part") "MF1/4W-15Ω±1% T") (field (name "Manufacturer") "CCO(千志电子)"))
      (libsource (lib "") (part "MF1/4W-15Ω±1% T52"))
    )
    (comp (ref "R65")
      (value "10k")
      (fields (field (name "Manufacturer Part") "MFR-12FTF52-10K") (field (name "Manufacturer") "YAGEO(国巨)"))
      (libsource (lib "") (part "R_0603_EU_1"))
    )
    (comp (ref "R66")
      (value "15Ω")
      (fields (field (name "Manufacturer Part") "MF1/4W-15Ω±1% T") (field (name "Manufacturer") "CCO(千志电子)"))
      (libsource (lib "") (part "MF1/4W-15Ω±1% T52"))
    )
    (comp (ref "R67")
      (value "10k")
      (fields (field (name "Manufacturer Part") "MFR-12FTF52-10K") (field (name "Manufacturer") "YAGEO(国巨)"))
      (libsource (lib "") (part "R_0603_EU_1"))
    )
    (comp (ref "R68")
      (value "15Ω")
      (fields (field (name "Manufacturer Part") "MF1/4W-15Ω±1% T") (field (name "Manufacturer") "CCO(千志电子)"))
      (libsource (lib "") (part "MF1/4W-15Ω±1% T52"))
    )
    (comp (ref "R69")
      (value "10k")
      (fields (field (name "Manufacturer Part") "MFR-12FTF52-10K") (field (name "Manufacturer") "YAGEO(国巨)"))
      (libsource (lib "") (part "R_0603_EU_1"))
    )
    (comp (ref "SW1")
      (value "DIP switchEI-04")
      (fields (field (name "Manufacturer Part") "拨码开关EI-04") (field (name "Manufacturer") "圜达"))
      (libsource (lib "") (part "DIP switchEI-04"))
    )
    (comp (ref "U1")
      (value "XL74HC4514D")
      (fields (field (name "Manufacturer") "XINLUDA(信路达)"))
      (libsource (lib "") (part "XL74HC4514D"))
    )
    (comp (ref "U2")
      (value "CD74HC4060M96")
      (fields (field (name "Manufacturer") "TI(德州仪器)"))
      (libsource (lib "") (part "CD74HC4060M96"))
    )
    (comp (ref "U3")
      (value "74LVC541AD-Q100J")
      (fields (field (name "Manufacturer") "Nexperia(安世)"))
      (libsource (lib "") (part "74LVC541AD-Q100J"))
    )
    (comp (ref "U4")
      (value "SN74HC590ADR")
      (fields (field (name "Manufacturer") "TI(德州仪器)"))
      (libsource (lib "") (part "SN74HC590ADR"))
    )
    (comp (ref "U5")
      (value "74LVC541AD-Q100J")
      (fields (field (name "Manufacturer") "Nexperia(安世)"))
      (libsource (lib "") (part "74LVC541AD-Q100J"))
    )
    (comp (ref "U6")
      (value "AT28C256-15PU")
      (fields (field (name "Manufacturer") "MICROCHIP(美国微芯)"))
      (libsource (lib "") (part "AT28C256-15PU"))
    )
    (comp (ref "U7")
      (value "LM3940IMPX-3.3/NOPB")
      (fields (field (name "Manufacturer") "TI(德州仪器)"))
      (libsource (lib "") (part "LM3940IMPX-3.3/NOPB"))
    )
    (comp (ref "X1")
      (value "32.768kHz")
      (fields
        (field (name "Manufacturer Part") "CD02K032768ACNBAEAE")
        (field (name "Manufacturer") "TKD(泰晶)")
      )
      (libsource (lib "") (part "CD02K032768ACNBAEAE"))
    )
  )
  (nets
    (net (code "1") (name "+3.3V") (class "Default")
      (node (ref "C6") (pin "1") (pinfunction "1_1") (pintype "unspecified"))
      (node (ref "Q17") (pin "2") (pinfunction "S_2") (pintype "unspecified"))
      (node (ref "Q19") (pin "2") (pinfunction "S_2") (pintype "unspecified"))
      (node (ref "Q20") (pin "2") (pinfunction "S_2") (pintype "unspecified"))
      (node (ref "Q21") (pin "2") (pinfunction "S_2") (pintype "unspecified"))
      (node (ref "Q22") (pin "2") (pinfunction "S_2") (pintype "unspecified"))
      (node (ref "Q23") (pin "2") (pinfunction "S_2") (pintype "unspecified"))
      (node (ref "Q24") (pin "2") (pinfunction "S_2") (pintype "unspecified"))
      (node (ref "Q25") (pin "2") (pinfunction "S_2") (pintype "unspecified"))
      (node (ref "Q26") (pin "2") (pinfunction "S_2") (pintype "unspecified"))
      (node (ref "Q27") (pin "2") (pinfunction "S_2") (pintype "unspecified"))
      (node (ref "Q28") (pin "2") (pinfunction "S_2") (pintype "unspecified"))
      (node (ref "Q29") (pin "2") (pinfunction "S_2") (pintype "unspecified"))
      (node (ref "Q30") (pin "2") (pinfunction "S_2") (pintype "unspecified"))
      (node (ref "Q31") (pin "2") (pinfunction "S_2") (pintype "unspecified"))
      (node (ref "Q32") (pin "2") (pinfunction "S_2") (pintype "unspecified"))
      (node (ref "Q33") (pin "2") (pinfunction "S_2") (pintype "unspecified"))
      (node (ref "R1") (pin "1") (pinfunction "1_1") (pintype "unspecified"))
      (node (ref "R10") (pin "1") (pinfunction "1_1") (pintype "unspecified"))
      (node (ref "R11") (pin "1") (pinfunction "1_1") (pintype "unspecified"))
      (node (ref "R12") (pin "1") (pinfunction "1_1") (pintype "unspecified"))
      (node (ref "R13") (pin "1") (pinfunction "1_1") (pintype "unspecified"))
      (node (ref "R14") (pin "1") (pinfunction "1_1") (pintype "unspecified"))
      (node (ref "R15") (pin "1") (pinfunction "1_1") (pintype "unspecified"))
      (node (ref "R16") (pin "1") (pinfunction "1_1") (pintype "unspecified"))
      (node (ref "R17") (pin "1") (pinfunction "1_1") (pintype "unspecified"))
      (node (ref "R2") (pin "1") (pinfunction "1_1") (pintype "unspecified"))
      (node (ref "R20") (pin "2") (pinfunction "2_2") (pintype "unspecified"))
      (node (ref "R21") (pin "2") (pinfunction "2_2") (pintype "unspecified"))
      (node (ref "R23") (pin "2") (pinfunction "2_2") (pintype "unspecified"))
      (node (ref "R25") (pin "2") (pinfunction "2_2") (pintype "unspecified"))
      (node (ref "R3") (pin "1") (pinfunction "1_1") (pintype "unspecified"))
      (node (ref "R32") (pin "2") (pinfunction "2_2") (pintype "unspecified"))
      (node (ref "R36") (pin "2") (pinfunction "2_2") (pintype "unspecified"))
      (node (ref "R39") (pin "2") (pinfunction "2_2") (pintype "unspecified"))
      (node (ref "R4") (pin "1") (pinfunction "1_1") (pintype "unspecified"))
      (node (ref "R41") (pin "2") (pinfunction "2_2") (pintype "unspecified"))
      (node (ref "R45") (pin "2") (pinfunction "2_2") (pintype "unspecified"))
      (node (ref "R5") (pin "1") (pinfunction "1_1") (pintype "unspecified"))
      (node (ref "R53") (pin "2") (pinfunction "2_2") (pintype "unspecified"))
      (node (ref "R57") (pin "2") (pinfunction "2_2") (pintype "unspecified"))
      (node (ref "R6") (pin "1") (pinfunction "1_1") (pintype "unspecified"))
      (node (ref "R61") (pin "2") (pinfunction "2_2") (pintype "unspecified"))
      (node (ref "R63") (pin "2") (pinfunction "2_2") (pintype "unspecified"))
      (node (ref "R65") (pin "2") (pinfunction "2_2") (pintype "unspecified"))
      (node (ref "R67") (pin "2") (pinfunction "2_2") (pintype "unspecified"))
      (node (ref "R69") (pin "2") (pinfunction "2_2") (pintype "unspecified"))
      (node (ref "R7") (pin "1") (pinfunction "1_1") (pintype "unspecified"))
      (node (ref "R8") (pin "1") (pinfunction "1_1") (pintype "unspecified"))
      (node (ref "R9") (pin "1") (pinfunction "1_1") (pintype "unspecified"))
      (node (ref "U3") (pin "20") (pinfunction "VCC_20") (pintype "unspecified"))
      (node (ref "U5") (pin "20") (pinfunction "VCC_20") (pintype "unspecified"))
      (node (ref "U7") (pin "3") (pinfunction "OUT_3") (pintype "unspecified"))
    )
    (net (code "2") (name "+5V") (class "Default")
      (node (ref "C1") (pin "2") (pinfunction "2_2") (pintype "unspecified"))
      (node (ref "C2") (pin "2") (pinfunction "2_2") (pintype "unspecified"))
      (node (ref "C5") (pin "1") (pinfunction "1_1") (pintype "input"))
      (node (ref "DIP1") (pin "1") (pinfunction "1_1") (pintype "unspecified"))
      (node (ref "DIP1") (pin "2") (pinfunction "2_2") (pintype "unspecified"))
      (node (ref "DIP1") (pin "3") (pinfunction "3_3") (pintype "unspecified"))
      (node (ref "DIP1") (pin "4") (pinfunction "4_4") (pintype "unspecified"))
      (node (ref "DIP1") (pin "5") (pinfunction "5_5") (pintype "unspecified"))
      (node (ref "DIP1") (pin "6") (pinfunction "6_6") (pintype "unspecified"))
      (node (ref "DIP1") (pin "7") (pinfunction "7_7") (pintype "unspecified"))
      (node (ref "DIP1") (pin "8") (pinfunction "8_8") (pintype "unspecified"))
      (node (ref "J3") (pin "2") (pinfunction "2_2") (pintype "unspecified"))
      (node (ref "R28") (pin "2") (pinfunction "2_2") (pintype "unspecified"))
      (node (ref "R33") (pin "2") (pinfunction "2_2") (pintype "unspecified"))
      (node (ref "SW1") (pin "1") (pinfunction "1_1") (pintype "unspecified"))
      (node (ref "SW1") (pin "2") (pinfunction "2_2") (pintype "unspecified"))
      (node (ref "SW1") (pin "3") (pinfunction "3_3") (pintype "unspecified"))
      (node (ref "SW1") (pin "4") (pinfunction "4_4") (pintype "unspecified"))
      (node (ref "U1") (pin "1") (pinfunction "LE_1") (pintype "unspecified"))
      (node (ref "U1") (pin "24") (pinfunction "VCC_24") (pintype "unspecified"))
      (node (ref "U2") (pin "16") (pinfunction "VCC_16") (pintype "unspecified"))
      (node (ref "U4") (pin "16") (pinfunction "VCC_16") (pintype "unspecified"))
      (node (ref "U6") (pin "28") (pinfunction "Vcc_28") (pintype "unspecified"))
      (node (ref "U7") (pin "1") (pinfunction "IN_1") (pintype "unspecified"))
    )
    (net (code "3") (name "1") (class "Default")
      (node (ref "LED1") (pin "2") (pinfunction "A_2") (pintype "unspecified"))
      (node (ref "LED10") (pin "2") (pinfunction "A_2") (pintype "unspecified"))
      (node (ref "LED11") (pin "2") (pinfunction "A_2") (pintype "unspecified"))
      (node (ref "LED12") (pin "2") (pinfunction "A_2") (pintype "unspecified"))
      (node (ref "LED13") (pin "2") (pinfunction "A_2") (pintype "unspecified"))
      (node (ref "LED14") (pin "2") (pinfunction "A_2") (pintype "unspecified"))
      (node (ref "LED15") (pin "2") (pinfunction "A_2") (pintype "unspecified"))
      (node (ref "LED16") (pin "2") (pinfunction "A_2") (pintype "unspecified"))
      (node (ref "LED2") (pin "2") (pinfunction "A_2") (pintype "unspecified"))
      (node (ref "LED3") (pin "2") (pinfunction "A_2") (pintype "unspecified"))
      (node (ref "LED4") (pin "2") (pinfunction "A_2") (pintype "unspecified"))
      (node (ref "LED5") (pin "2") (pinfunction "A_2") (pintype "unspecified"))
      (node (ref "LED6") (pin "2") (pinfunction "A_2") (pintype "unspecified"))
      (node (ref "LED7") (pin "2") (pinfunction "A_2") (pintype "unspecified"))
      (node (ref "LED8") (pin "2") (pinfunction "A_2") (pintype "unspecified"))
      (node (ref "LED9") (pin "2") (pinfunction "A_2") (pintype "unspecified"))
      (node (ref "R19") (pin "2") (pinfunction "2_2") (pintype "unspecified"))
    )
    (net (code "4") (name "2") (class "Default")
      (node (ref "LED17") (pin "2") (pinfunction "A_2") (pintype "unspecified"))
      (node (ref "LED18") (pin "2") (pinfunction "A_2") (pintype "unspecified"))
      (node (ref "LED19") (pin "2") (pinfunction "A_2") (pintype "unspecified"))
      (node (ref "LED20") (pin "2") (pinfunction "A_2") (pintype "unspecified"))
      (node (ref "LED21") (pin "2") (pinfunction "A_2") (pintype "unspecified"))
      (node (ref "LED22") (pin "2") (pinfunction "A_2") (pintype "unspecified"))
      (node (ref "LED23") (pin "2") (pinfunction "A_2") (pintype "unspecified"))
      (node (ref "LED24") (pin "2") (pinfunction "A_2") (pintype "unspecified"))
      (node (ref "LED25") (pin "2") (pinfunction "A_2") (pintype "unspecified"))
      (node (ref "LED26") (pin "2") (pinfunction "A_2") (pintype "unspecified"))
      (node (ref "LED27") (pin "2") (pinfunction "A_2") (pintype "unspecified"))
      (node (ref "LED28") (pin "2") (pinfunction "A_2") (pintype "unspecified"))
      (node (ref "LED29") (pin "2") (pinfunction "A_2") (pintype "unspecified"))
      (node (ref "LED30") (pin "2") (pinfunction "A_2") (pintype "unspecified"))
      (node (ref "LED31") (pin "2") (pinfunction "A_2") (pintype "unspecified"))
      (node (ref "LED32") (pin "2") (pinfunction "A_2") (pintype "unspecified"))
      (node (ref "R22") (pin "2") (pinfunction "2_2") (pintype "unspecified"))
    )
    (net (code "5") (name "3") (class "Default")
      (node (ref "LED33") (pin "2") (pinfunction "A_2") (pintype "unspecified"))
      (node (ref "LED34") (pin "2") (pinfunction "A_2") (pintype "unspecified"))
      (node (ref "LED35") (pin "2") (pinfunction "A_2") (pintype "unspecified"))
      (node (ref "LED36") (pin "2") (pinfunction "A_2") (pintype "unspecified"))
      (node (ref "LED37") (pin "2") (pinfunction "A_2") (pintype "unspecified"))
      (node (ref "LED38") (pin "2") (pinfunction "A_2") (pintype "unspecified"))
      (node (ref "LED39") (pin "2") (pinfunction "A_2") (pintype "unspecified"))
      (node (ref "LED40") (pin "2") (pinfunction "A_2") (pintype "unspecified"))
      (node (ref "LED41") (pin "2") (pinfunction "A_2") (pintype "unspecified"))
      (node (ref "LED42") (pin "2") (pinfunction "A_2") (pintype "unspecified"))
      (node (ref "LED43") (pin "2") (pinfunction "A_2") (pintype "unspecified"))
      (node (ref "LED44") (pin "2") (pinfunction "A_2") (pintype "unspecified"))
      (node (ref "LED45") (pin "2") (pinfunction "A_2") (pintype "unspecified"))
      (node (ref "LED46") (pin "2") (pinfunction "A_2") (pintype "unspecified"))
      (node (ref "LED47") (pin "2") (pinfunction "A_2") (pintype "unspecified"))
      (node (ref "LED48") (pin "2") (pinfunction "A_2") (pintype "unspecified"))
      (node (ref "R24") (pin "2") (pinfunction "2_2") (pintype "unspecified"))
    )
    (net (code "6") (name "4") (class "Default")
      (node (ref "LED49") (pin "2") (pinfunction "A_2") (pintype "unspecified"))
      (node (ref "LED50") (pin "2") (pinfunction "A_2") (pintype "unspecified"))
      (node (ref "LED51") (pin "2") (pinfunction "A_2") (pintype "unspecified"))
      (node (ref "LED52") (pin "2") (pinfunction "A_2") (pintype "unspecified"))
      (node (ref "LED53") (pin "2") (pinfunction "A_2") (pintype "unspecified"))
      (node (ref "LED54") (pin "2") (pinfunction "A_2") (pintype "unspecified"))
      (node (ref "LED55") (pin "2") (pinfunction "A_2") (pintype "unspecified"))
      (node (ref "LED56") (pin "2") (pinfunction "A_2") (pintype "unspecified"))
      (node (ref "LED57") (pin "2") (pinfunction "A_2") (pintype "unspecified"))
      (node (ref "LED58") (pin "2") (pinfunction "A_2") (pintype "unspecified"))
      (node (ref "LED59") (pin "2") (pinfunction "A_2") (pintype "unspecified"))
      (node (ref "LED60") (pin "2") (pinfunction "A_2") (pintype "unspecified"))
      (node (ref "LED61") (pin "2") (pinfunction "A_2") (pintype "unspecified"))
      (node (ref "LED62") (pin "2") (pinfunction "A_2") (pintype "unspecified"))
      (node (ref "LED63") (pin "2") (pinfunction "A_2") (pintype "unspecified"))
      (node (ref "LED64") (pin "2") (pinfunction "A_2") (pintype "unspecified"))
      (node (ref "R27") (pin "2") (pinfunction "2_2") (pintype "unspecified"))
    )
    (net (code "7") (name "5") (class "Default")
      (node (ref "LED65") (pin "2") (pinfunction "A_2") (pintype "unspecified"))
      (node (ref "LED66") (pin "2") (pinfunction "A_2") (pintype "unspecified"))
      (node (ref "LED67") (pin "2") (pinfunction "A_2") (pintype "unspecified"))
      (node (ref "LED68") (pin "2") (pinfunction "A_2") (pintype "unspecified"))
      (node (ref "LED69") (pin "2") (pinfunction "A_2") (pintype "unspecified"))
      (node (ref "LED70") (pin "2") (pinfunction "A_2") (pintype "unspecified"))
      (node (ref "LED71") (pin "2") (pinfunction "A_2") (pintype "unspecified"))
      (node (ref "LED72") (pin "2") (pinfunction "A_2") (pintype "unspecified"))
      (node (ref "LED73") (pin "2") (pinfunction "A_2") (pintype "unspecified"))
      (node (ref "LED74") (pin "2") (pinfunction "A_2") (pintype "unspecified"))
      (node (ref "LED75") (pin "2") (pinfunction "A_2") (pintype "unspecified"))
      (node (ref "LED76") (pin "2") (pinfunction "A_2") (pintype "unspecified"))
      (node (ref "LED77") (pin "2") (pinfunction "A_2") (pintype "unspecified"))
      (node (ref "LED78") (pin "2") (pinfunction "A_2") (pintype "unspecified"))
      (node (ref "LED79") (pin "2") (pinfunction "A_2") (pintype "unspecified"))
      (node (ref "LED80") (pin "2") (pinfunction "A_2") (pintype "unspecified"))
      (node (ref "R31") (pin "2") (pinfunction "2_2") (pintype "unspecified"))
    )
    (net (code "8") (name "6") (class "Default")
      (node (ref "LED81") (pin "2") (pinfunction "A_2") (pintype "unspecified"))
      (node (ref "LED82") (pin "2") (pinfunction "A_2") (pintype "unspecified"))
      (node (ref "LED83") (pin "2") (pinfunction "A_2") (pintype "unspecified"))
      (node (ref "LED84") (pin "2") (pinfunction "A_2") (pintype "unspecified"))
      (node (ref "LED85") (pin "2") (pinfunction "A_2") (pintype "unspecified"))
      (node (ref "LED86") (pin "2") (pinfunction "A_2") (pintype "unspecified"))
      (node (ref "LED87") (pin "2") (pinfunction "A_2") (pintype "unspecified"))
      (node (ref "LED88") (pin "2") (pinfunction "A_2") (pintype "unspecified"))
      (node (ref "LED89") (pin "2") (pinfunction "A_2") (pintype "unspecified"))
      (node (ref "LED90") (pin "2") (pinfunction "A_2") (pintype "unspecified"))
      (node (ref "LED91") (pin "2") (pinfunction "A_2") (pintype "unspecified"))
      (node (ref "LED92") (pin "2") (pinfunction "A_2") (pintype "unspecified"))
      (node (ref "LED93") (pin "2") (pinfunction "A_2") (pintype "unspecified"))
      (node (ref "LED94") (pin "2") (pinfunction "A_2") (pintype "unspecified"))
      (node (ref "LED95") (pin "2") (pinfunction "A_2") (pintype "unspecified"))
      (node (ref "LED96") (pin "2") (pinfunction "A_2") (pintype "unspecified"))
      (node (ref "R34") (pin "2") (pinfunction "2_2") (pintype "unspecified"))
    )
    (net (code "9") (name "7") (class "Default")
      (node (ref "LED100") (pin "2") (pinfunction "A_2") (pintype "unspecified"))
      (node (ref "LED101") (pin "2") (pinfunction "A_2") (pintype "unspecified"))
      (node (ref "LED102") (pin "2") (pinfunction "A_2") (pintype "unspecified"))
      (node (ref "LED103") (pin "2") (pinfunction "A_2") (pintype "unspecified"))
      (node (ref "LED104") (pin "2") (pinfunction "A_2") (pintype "unspecified"))
      (node (ref "LED105") (pin "2") (pinfunction "A_2") (pintype "unspecified"))
      (node (ref "LED106") (pin "2") (pinfunction "A_2") (pintype "unspecified"))
      (node (ref "LED107") (pin "2") (pinfunction "A_2") (pintype "unspecified"))
      (node (ref "LED108") (pin "2") (pinfunction "A_2") (pintype "unspecified"))
      (node (ref "LED109") (pin "2") (pinfunction "A_2") (pintype "unspecified"))
      (node (ref "LED110") (pin "2") (pinfunction "A_2") (pintype "unspecified"))
      (node (ref "LED111") (pin "2") (pinfunction "A_2") (pintype "unspecified"))
      (node (ref "LED112") (pin "2") (pinfunction "A_2") (pintype "unspecified"))
      (node (ref "LED97") (pin "2") (pinfunction "A_2") (pintype "unspecified"))
      (node (ref "LED98") (pin "2") (pinfunction "A_2") (pintype "unspecified"))
      (node (ref "LED99") (pin "2") (pinfunction "A_2") (pintype "unspecified"))
      (node (ref "R38") (pin "2") (pinfunction "2_2") (pintype "unspecified"))
    )
    (net (code "10") (name "8") (class "Default")
      (node (ref "LED113") (pin "2") (pinfunction "A_2") (pintype "unspecified"))
      (node (ref "LED114") (pin "2") (pinfunction "A_2") (pintype "unspecified"))
      (node (ref "LED115") (pin "2") (pinfunction "A_2") (pintype "unspecified"))
      (node (ref "LED116") (pin "2") (pinfunction "A_2") (pintype "unspecified"))
      (node (ref "LED117") (pin "2") (pinfunction "A_2") (pintype "unspecified"))
      (node (ref "LED118") (pin "2") (pinfunction "A_2") (pintype "unspecified"))
      (node (ref "LED119") (pin "2") (pinfunction "A_2") (pintype "unspecified"))
      (node (ref "LED120") (pin "2") (pinfunction "A_2") (pintype "unspecified"))
      (node (ref "LED121") (pin "2") (pinfunction "A_2") (pintype "unspecified"))
      (node (ref "LED122") (pin "2") (pinfunction "A_2") (pintype "unspecified"))
      (node (ref "LED123") (pin "2") (pinfunction "A_2") (pintype "unspecified"))
      (node (ref "LED124") (pin "2") (pinfunction "A_2") (pintype "unspecified"))
      (node (ref "LED125") (pin "2") (pinfunction "A_2") (pintype "unspecified"))
      (node (ref "LED126") (pin "2") (pinfunction "A_2") (pintype "unspecified"))
      (node (ref "LED127") (pin "2") (pinfunction "A_2") (pintype "unspecified"))
      (node (ref "LED128") (pin "2") (pinfunction "A_2") (pintype "unspecified"))
      (node (ref "R40") (pin "2") (pinfunction "2_2") (pintype "unspecified"))
    )
    (net (code "11") (name "9") (class "Default")
      (node (ref "LED129") (pin "2") (pinfunction "A_2") (pintype "unspecified"))
      (node (ref "LED130") (pin "2") (pinfunction "A_2") (pintype "unspecified"))
      (node (ref "LED131") (pin "2") (pinfunction "A_2") (pintype "unspecified"))
      (node (ref "LED132") (pin "2") (pinfunction "A_2") (pintype "unspecified"))
      (node (ref "LED133") (pin "2") (pinfunction "A_2") (pintype "unspecified"))
      (node (ref "LED134") (pin "2") (pinfunction "A_2") (pintype "unspecified"))
      (node (ref "LED135") (pin "2") (pinfunction "A_2") (pintype "unspecified"))
      (node (ref "LED136") (pin "2") (pinfunction "A_2") (pintype "unspecified"))
      (node (ref "LED137") (pin "2") (pinfunction "A_2") (pintype "unspecified"))
      (node (ref "LED138") (pin "2") (pinfunction "A_2") (pintype "unspecified"))
      (node (ref "LED139") (pin "2") (pinfunction "A_2") (pintype "unspecified"))
      (node (ref "LED140") (pin "2") (pinfunction "A_2") (pintype "unspecified"))
      (node (ref "LED141") (pin "2") (pinfunction "A_2") (pintype "unspecified"))
      (node (ref "LED142") (pin "2") (pinfunction "A_2") (pintype "unspecified"))
      (node (ref "LED143") (pin "2") (pinfunction "A_2") (pintype "unspecified"))
      (node (ref "LED144") (pin "2") (pinfunction "A_2") (pintype "unspecified"))
      (node (ref "R42") (pin "2") (pinfunction "2_2") (pintype "unspecified"))
    )
    (net (code "12") (name "10") (class "Default")
      (node (ref "LED145") (pin "2") (pinfunction "A_2") (pintype "unspecified"))
      (node (ref "LED146") (pin "2") (pinfunction "A_2") (pintype "unspecified"))
      (node (ref "LED147") (pin "2") (pinfunction "A_2") (pintype "unspecified"))
      (node (ref "LED148") (pin "2") (pinfunction "A_2") (pintype "unspecified"))
      (node (ref "LED149") (pin "2") (pinfunction "A_2") (pintype "unspecified"))
      (node (ref "LED150") (pin "2") (pinfunction "A_2") (pintype "unspecified"))
      (node (ref "LED151") (pin "2") (pinfunction "A_2") (pintype "unspecified"))
      (node (ref "LED152") (pin "2") (pinfunction "A_2") (pintype "unspecified"))
      (node (ref "LED153") (pin "2") (pinfunction "A_2") (pintype "unspecified"))
      (node (ref "LED154") (pin "2") (pinfunction "A_2") (pintype "unspecified"))
      (node (ref "LED155") (pin "2") (pinfunction "A_2") (pintype "unspecified"))
      (node (ref "LED156") (pin "2") (pinfunction "A_2") (pintype "unspecified"))
      (node (ref "LED157") (pin "2") (pinfunction "A_2") (pintype "unspecified"))
      (node (ref "LED158") (pin "2") (pinfunction "A_2") (pintype "unspecified"))
      (node (ref "LED159") (pin "2") (pinfunction "A_2") (pintype "unspecified"))
      (node (ref "LED160") (pin "2") (pinfunction "A_2") (pintype "unspecified"))
      (node (ref "R49") (pin "2") (pinfunction "2_2") (pintype "unspecified"))
    )
    (net (code "13") (name "11") (class "Default")
      (node (ref "LED161") (pin "2") (pinfunction "A_2") (pintype "unspecified"))
      (node (ref "LED162") (pin "2") (pinfunction "A_2") (pintype "unspecified"))
      (node (ref "LED163") (pin "2") (pinfunction "A_2") (pintype "unspecified"))
      (node (ref "LED164") (pin "2") (pinfunction "A_2") (pintype "unspecified"))
      (node (ref "LED165") (pin "2") (pinfunction "A_2") (pintype "unspecified"))
      (node (ref "LED166") (pin "2") (pinfunction "A_2") (pintype "unspecified"))
      (node (ref "LED167") (pin "2") (pinfunction "A_2") (pintype "unspecified"))
      (node (ref "LED168") (pin "2") (pinfunction "A_2") (pintype "unspecified"))
      (node (ref "LED169") (pin "2") (pinfunction "A_2") (pintype "unspecified"))
      (node (ref "LED170") (pin "2") (pinfunction "A_2") (pintype "unspecified"))
      (node (ref "LED171") (pin "2") (pinfunction "A_2") (pintype "unspecified"))
      (node (ref "LED172") (pin "2") (pinfunction "A_2") (pintype "unspecified"))
      (node (ref "LED173") (pin "2") (pinfunction "A_2") (pintype "unspecified"))
      (node (ref "LED174") (pin "2") (pinfunction "A_2") (pintype "unspecified"))
      (node (ref "LED175") (pin "2") (pinfunction "A_2") (pintype "unspecified"))
      (node (ref "LED176") (pin "2") (pinfunction "A_2") (pintype "unspecified"))
      (node (ref "R54") (pin "2") (pinfunction "2_2") (pintype "unspecified"))
    )
    (net (code "14") (name "12") (class "Default")
      (node (ref "LED177") (pin "2") (pinfunction "A_2") (pintype "unspecified"))
      (node (ref "LED178") (pin "2") (pinfunction "A_2") (pintype "unspecified"))
      (node (ref "LED179") (pin "2") (pinfunction "A_2") (pintype "unspecified"))
      (node (ref "LED180") (pin "2") (pinfunction "A_2") (pintype "unspecified"))
      (node (ref "LED181") (pin "2") (pinfunction "A_2") (pintype "unspecified"))
      (node (ref "LED182") (pin "2") (pinfunction "A_2") (pintype "unspecified"))
      (node (ref "LED183") (pin "2") (pinfunction "A_2") (pintype "unspecified"))
      (node (ref "LED184") (pin "2") (pinfunction "A_2") (pintype "unspecified"))
      (node (ref "LED185") (pin "2") (pinfunction "A_2") (pintype "unspecified"))
      (node (ref "LED186") (pin "2") (pinfunction "A_2") (pintype "unspecified"))
      (node (ref "LED187") (pin "2") (pinfunction "A_2") (pintype "unspecified"))
      (node (ref "LED188") (pin "2") (pinfunction "A_2") (pintype "unspecified"))
      (node (ref "LED189") (pin "2") (pinfunction "A_2") (pintype "unspecified"))
      (node (ref "LED190") (pin "2") (pinfunction "A_2") (pintype "unspecified"))
      (node (ref "LED191") (pin "2") (pinfunction "A_2") (pintype "unspecified"))
      (node (ref "LED192") (pin "2") (pinfunction "A_2") (pintype "unspecified"))
      (node (ref "R60") (pin "2") (pinfunction "2_2") (pintype "unspecified"))
    )
    (net (code "15") (name "13") (class "Default")
      (node (ref "LED193") (pin "2") (pinfunction "A_2") (pintype "unspecified"))
      (node (ref "LED194") (pin "2") (pinfunction "A_2") (pintype "unspecified"))
      (node (ref "LED195") (pin "2") (pinfunction "A_2") (pintype "unspecified"))
      (node (ref "LED196") (pin "2") (pinfunction "A_2") (pintype "unspecified"))
      (node (ref "LED197") (pin "2") (pinfunction "A_2") (pintype "unspecified"))
      (node (ref "LED198") (pin "2") (pinfunction "A_2") (pintype "unspecified"))
      (node (ref "LED199") (pin "2") (pinfunction "A_2") (pintype "unspecified"))
      (node (ref "LED200") (pin "2") (pinfunction "A_2") (pintype "unspecified"))
      (node (ref "LED201") (pin "2") (pinfunction "A_2") (pintype "unspecified"))
      (node (ref "LED202") (pin "2") (pinfunction "A_2") (pintype "unspecified"))
      (node (ref "LED203") (pin "2") (pinfunction "A_2") (pintype "unspecified"))
      (node (ref "LED204") (pin "2") (pinfunction "A_2") (pintype "unspecified"))
      (node (ref "LED205") (pin "2") (pinfunction "A_2") (pintype "unspecified"))
      (node (ref "LED206") (pin "2") (pinfunction "A_2") (pintype "unspecified"))
      (node (ref "LED207") (pin "2") (pinfunction "A_2") (pintype "unspecified"))
      (node (ref "LED208") (pin "2") (pinfunction "A_2") (pintype "unspecified"))
      (node (ref "R62") (pin "2") (pinfunction "2_2") (pintype "unspecified"))
    )
    (net (code "16") (name "14") (class "Default")
      (node (ref "LED209") (pin "2") (pinfunction "A_2") (pintype "unspecified"))
      (node (ref "LED210") (pin "2") (pinfunction "A_2") (pintype "unspecified"))
      (node (ref "LED211") (pin "2") (pinfunction "A_2") (pintype "unspecified"))
      (node (ref "LED212") (pin "2") (pinfunction "A_2") (pintype "unspecified"))
      (node (ref "LED213") (pin "2") (pinfunction "A_2") (pintype "unspecified"))
      (node (ref "LED214") (pin "2") (pinfunction "A_2") (pintype "unspecified"))
      (node (ref "LED215") (pin "2") (pinfunction "A_2") (pintype "unspecified"))
      (node (ref "LED216") (pin "2") (pinfunction "A_2") (pintype "unspecified"))
      (node (ref "LED217") (pin "2") (pinfunction "A_2") (pintype "unspecified"))
      (node (ref "LED218") (pin "2") (pinfunction "A_2") (pintype "unspecified"))
      (node (ref "LED219") (pin "2") (pinfunction "A_2") (pintype "unspecified"))
      (node (ref "LED220") (pin "2") (pinfunction "A_2") (pintype "unspecified"))
      (node (ref "LED221") (pin "2") (pinfunction "A_2") (pintype "unspecified"))
      (node (ref "LED222") (pin "2") (pinfunction "A_2") (pintype "unspecified"))
      (node (ref "LED223") (pin "2") (pinfunction "A_2") (pintype "unspecified"))
      (node (ref "LED224") (pin "2") (pinfunction "A_2") (pintype "unspecified"))
      (node (ref "R64") (pin "2") (pinfunction "2_2") (pintype "unspecified"))
    )
    (net (code "17") (name "15") (class "Default")
      (node (ref "LED225") (pin "2") (pinfunction "A_2") (pintype "unspecified"))
      (node (ref "LED226") (pin "2") (pinfunction "A_2") (pintype "unspecified"))
      (node (ref "LED227") (pin "2") (pinfunction "A_2") (pintype "unspecified"))
      (node (ref "LED228") (pin "2") (pinfunction "A_2") (pintype "unspecified"))
      (node (ref "LED229") (pin "2") (pinfunction "A_2") (pintype "unspecified"))
      (node (ref "LED230") (pin "2") (pinfunction "A_2") (pintype "unspecified"))
      (node (ref "LED231") (pin "2") (pinfunction "A_2") (pintype "unspecified"))
      (node (ref "LED232") (pin "2") (pinfunction "A_2") (pintype "unspecified"))
      (node (ref "LED233") (pin "2") (pinfunction "A_2") (pintype "unspecified"))
      (node (ref "LED234") (pin "2") (pinfunction "A_2") (pintype "unspecified"))
      (node (ref "LED235") (pin "2") (pinfunction "A_2") (pintype "unspecified"))
      (node (ref "LED236") (pin "2") (pinfunction "A_2") (pintype "unspecified"))
      (node (ref "LED237") (pin "2") (pinfunction "A_2") (pintype "unspecified"))
      (node (ref "LED238") (pin "2") (pinfunction "A_2") (pintype "unspecified"))
      (node (ref "LED239") (pin "2") (pinfunction "A_2") (pintype "unspecified"))
      (node (ref "LED240") (pin "2") (pinfunction "A_2") (pintype "unspecified"))
      (node (ref "R66") (pin "2") (pinfunction "2_2") (pintype "unspecified"))
    )
    (net (code "18") (name "16") (class "Default")
      (node (ref "LED241") (pin "2") (pinfunction "A_2") (pintype "unspecified"))
      (node (ref "LED242") (pin "2") (pinfunction "A_2") (pintype "unspecified"))
      (node (ref "LED243") (pin "2") (pinfunction "A_2") (pintype "unspecified"))
      (node (ref "LED244") (pin "2") (pinfunction "A_2") (pintype "unspecified"))
      (node (ref "LED245") (pin "2") (pinfunction "A_2") (pintype "unspecified"))
      (node (ref "LED246") (pin "2") (pinfunction "A_2") (pintype "unspecified"))
      (node (ref "LED247") (pin "2") (pinfunction "A_2") (pintype "unspecified"))
      (node (ref "LED248") (pin "2") (pinfunction "A_2") (pintype "unspecified"))
      (node (ref "LED249") (pin "2") (pinfunction "A_2") (pintype "unspecified"))
      (node (ref "LED250") (pin "2") (pinfunction "A_2") (pintype "unspecified"))
      (node (ref "LED251") (pin "2") (pinfunction "A_2") (pintype "unspecified"))
      (node (ref "LED252") (pin "2") (pinfunction "A_2") (pintype "unspecified"))
      (node (ref "LED253") (pin "2") (pinfunction "A_2") (pintype "unspecified"))
      (node (ref "LED254") (pin "2") (pinfunction "A_2") (pintype "unspecified"))
      (node (ref "LED255") (pin "2") (pinfunction "A_2") (pintype "unspecified"))
      (node (ref "LED256") (pin "2") (pinfunction "A_2") (pintype "unspecified"))
      (node (ref "R68") (pin "2") (pinfunction "2_2") (pintype "unspecified"))
    )
    (net (code "19") (name "A") (class "Default")
      (node (ref "LED1") (pin "1") (pinfunction "K_1") (pintype "unspecified"))
      (node (ref "LED113") (pin "1") (pinfunction "K_1") (pintype "unspecified"))
      (node (ref "LED129") (pin "1") (pinfunction "K_1") (pintype "unspecified"))
      (node (ref "LED145") (pin "1") (pinfunction "K_1") (pintype "unspecified"))
      (node (ref "LED161") (pin "1") (pinfunction "K_1") (pintype "unspecified"))
      (node (ref "LED17") (pin "1") (pinfunction "K_1") (pintype "unspecified"))
      (node (ref "LED177") (pin "1") (pinfunction "K_1") (pintype "unspecified"))
      (node (ref "LED193") (pin "1") (pinfunction "K_1") (pintype "unspecified"))
      (node (ref "LED209") (pin "1") (pinfunction "K_1") (pintype "unspecified"))
      (node (ref "LED225") (pin "1") (pinfunction "K_1") (pintype "unspecified"))
      (node (ref "LED241") (pin "1") (pinfunction "K_1") (pintype "unspecified"))
      (node (ref "LED33") (pin "1") (pinfunction "K_1") (pintype "unspecified"))
      (node (ref "LED49") (pin "1") (pinfunction "K_1") (pintype "unspecified"))
      (node (ref "LED65") (pin "1") (pinfunction "K_1") (pintype "unspecified"))
      (node (ref "LED81") (pin "1") (pinfunction "K_1") (pintype "unspecified"))
      (node (ref "LED97") (pin "1") (pinfunction "K_1") (pintype "unspecified"))
      (node (ref "Q1") (pin "2") (pinfunction "D_2") (pintype "unspecified"))
      (node (ref "R1") (pin "2") (pinfunction "2_2") (pintype "unspecified"))
    )
    (net (code "20") (name "B") (class "Default")
      (node (ref "LED114") (pin "1") (pinfunction "K_1") (pintype "unspecified"))
      (node (ref "LED130") (pin "1") (pinfunction "K_1") (pintype "unspecified"))
      (node (ref "LED146") (pin "1") (pinfunction "K_1") (pintype "unspecified"))
      (node (ref "LED162") (pin "1") (pinfunction "K_1") (pintype "unspecified"))
      (node (ref "LED178") (pin "1") (pinfunction "K_1") (pintype "unspecified"))
      (node (ref "LED18") (pin "1") (pinfunction "K_1") (pintype "unspecified"))
      (node (ref "LED194") (pin "1") (pinfunction "K_1") (pintype "unspecified"))
      (node (ref "LED2") (pin "1") (pinfunction "K_1") (pintype "unspecified"))
      (node (ref "LED210") (pin "1") (pinfunction "K_1") (pintype "unspecified"))
      (node (ref "LED226") (pin "1") (pinfunction "K_1") (pintype "unspecified"))
      (node (ref "LED242") (pin "1") (pinfunction "K_1") (pintype "unspecified"))
      (node (ref "LED34") (pin "1") (pinfunction "K_1") (pintype "unspecified"))
      (node (ref "LED50") (pin "1") (pinfunction "K_1") (pintype "unspecified"))
      (node (ref "LED66") (pin "1") (pinfunction "K_1") (pintype "unspecified"))
      (node (ref "LED82") (pin "1") (pinfunction "K_1") (pintype "unspecified"))
      (node (ref "LED98") (pin "1") (pinfunction "K_1") (pintype "unspecified"))
      (node (ref "Q2") (pin "2") (pinfunction "D_2") (pintype "unspecified"))
      (node (ref "R2") (pin "2") (pinfunction "2_2") (pintype "unspecified"))
    )
    (net (code "21") (name "C") (class "Default")
      (node (ref "LED115") (pin "1") (pinfunction "K_1") (pintype "unspecified"))
      (node (ref "LED131") (pin "1") (pinfunction "K_1") (pintype "unspecified"))
      (node (ref "LED147") (pin "1") (pinfunction "K_1") (pintype "unspecified"))
      (node (ref "LED163") (pin "1") (pinfunction "K_1") (pintype "unspecified"))
      (node (ref "LED179") (pin "1") (pinfunction "K_1") (pintype "unspecified"))
      (node (ref "LED19") (pin "1") (pinfunction "K_1") (pintype "unspecified"))
      (node (ref "LED195") (pin "1") (pinfunction "K_1") (pintype "unspecified"))
      (node (ref "LED211") (pin "1") (pinfunction "K_1") (pintype "unspecified"))
      (node (ref "LED227") (pin "1") (pinfunction "K_1") (pintype "unspecified"))
      (node (ref "LED243") (pin "1") (pinfunction "K_1") (pintype "unspecified"))
      (node (ref "LED3") (pin "1") (pinfunction "K_1") (pintype "unspecified"))
      (node (ref "LED35") (pin "1") (pinfunction "K_1") (pintype "unspecified"))
      (node (ref "LED51") (pin "1") (pinfunction "K_1") (pintype "unspecified"))
      (node (ref "LED67") (pin "1") (pinfunction "K_1") (pintype "unspecified"))
      (node (ref "LED83") (pin "1") (pinfunction "K_1") (pintype "unspecified"))
      (node (ref "LED99") (pin "1") (pinfunction "K_1") (pintype "unspecified"))
      (node (ref "Q3") (pin "2") (pinfunction "D_2") (pintype "unspecified"))
      (node (ref "R3") (pin "2") (pinfunction "2_2") (pintype "unspecified"))
    )
    (net (code "22") (name "D") (class "Default")
      (node (ref "LED100") (pin "1") (pinfunction "K_1") (pintype "unspecified"))
      (node (ref "LED116") (pin "1") (pinfunction "K_1") (pintype "unspecified"))
      (node (ref "LED132") (pin "1") (pinfunction "K_1") (pintype "unspecified"))
      (node (ref "LED148") (pin "1") (pinfunction "K_1") (pintype "unspecified"))
      (node (ref "LED164") (pin "1") (pinfunction "K_1") (pintype "unspecified"))
      (node (ref "LED180") (pin "1") (pinfunction "K_1") (pintype "unspecified"))
      (node (ref "LED196") (pin "1") (pinfunction "K_1") (pintype "unspecified"))
      (node (ref "LED20") (pin "1") (pinfunction "K_1") (pintype "unspecified"))
      (node (ref "LED212") (pin "1") (pinfunction "K_1") (pintype "unspecified"))
      (node (ref "LED228") (pin "1") (pinfunction "K_1") (pintype "unspecified"))
      (node (ref "LED244") (pin "1") (pinfunction "K_1") (pintype "unspecified"))
      (node (ref "LED36") (pin "1") (pinfunction "K_1") (pintype "unspecified"))
      (node (ref "LED4") (pin "1") (pinfunction "K_1") (pintype "unspecified"))
      (node (ref "LED52") (pin "1") (pinfunction "K_1") (pintype "unspecified"))
      (node (ref "LED68") (pin "1") (pinfunction "K_1") (pintype "unspecified"))
      (node (ref "LED84") (pin "1") (pinfunction "K_1") (pintype "unspecified"))
      (node (ref "Q4") (pin "2") (pinfunction "D_2") (pintype "unspecified"))
      (node (ref "R4") (pin "2") (pinfunction "2_2") (pintype "unspecified"))
    )
    (net (code "23") (name "E") (class "Default")
      (node (ref "LED101") (pin "1") (pinfunction "K_1") (pintype "unspecified"))
      (node (ref "LED117") (pin "1") (pinfunction "K_1") (pintype "unspecified"))
      (node (ref "LED133") (pin "1") (pinfunction "K_1") (pintype "unspecified"))
      (node (ref "LED149") (pin "1") (pinfunction "K_1") (pintype "unspecified"))
      (node (ref "LED165") (pin "1") (pinfunction "K_1") (pintype "unspecified"))
      (node (ref "LED181") (pin "1") (pinfunction "K_1") (pintype "unspecified"))
      (node (ref "LED197") (pin "1") (pinfunction "K_1") (pintype "unspecified"))
      (node (ref "LED21") (pin "1") (pinfunction "K_1") (pintype "unspecified"))
      (node (ref "LED213") (pin "1") (pinfunction "K_1") (pintype "unspecified"))
      (node (ref "LED229") (pin "1") (pinfunction "K_1") (pintype "unspecified"))
      (node (ref "LED245") (pin "1") (pinfunction "K_1") (pintype "unspecified"))
      (node (ref "LED37") (pin "1") (pinfunction "K_1") (pintype "unspecified"))
      (node (ref "LED5") (pin "1") (pinfunction "K_1") (pintype "unspecified"))
      (node (ref "LED53") (pin "1") (pinfunction "K_1") (pintype "unspecified"))
      (node (ref "LED69") (pin "1") (pinfunction "K_1") (pintype "unspecified"))
      (node (ref "LED85") (pin "1") (pinfunction "K_1") (pintype "unspecified"))
      (node (ref "Q5") (pin "2") (pinfunction "D_2") (pintype "unspecified"))
      (node (ref "R5") (pin "2") (pinfunction "2_2") (pintype "unspecified"))
    )
    (net (code "24") (name "F") (class "Default")
      (node (ref "LED102") (pin "1") (pinfunction "K_1") (pintype "unspecified"))
      (node (ref "LED118") (pin "1") (pinfunction "K_1") (pintype "unspecified"))
      (node (ref "LED134") (pin "1") (pinfunction "K_1") (pintype "unspecified"))
      (node (ref "LED150") (pin "1") (pinfunction "K_1") (pintype "unspecified"))
      (node (ref "LED166") (pin "1") (pinfunction "K_1") (pintype "unspecified"))
      (node (ref "LED182") (pin "1") (pinfunction "K_1") (pintype "unspecified"))
      (node (ref "LED198") (pin "1") (pinfunction "K_1") (pintype "unspecified"))
      (node (ref "LED214") (pin "1") (pinfunction "K_1") (pintype "unspecified"))
      (node (ref "LED22") (pin "1") (pinfunction "K_1") (pintype "unspecified"))
      (node (ref "LED230") (pin "1") (pinfunction "K_1") (pintype "unspecified"))
      (node (ref "LED246") (pin "1") (pinfunction "K_1") (pintype "unspecified"))
      (node (ref "LED38") (pin "1") (pinfunction "K_1") (pintype "unspecified"))
      (node (ref "LED54") (pin "1") (pinfunction "K_1") (pintype "unspecified"))
      (node (ref "LED6") (pin "1") (pinfunction "K_1") (pintype "unspecified"))
      (node (ref "LED70") (pin "1") (pinfunction "K_1") (pintype "unspecified"))
      (node (ref "LED86") (pin "1") (pinfunction "K_1") (pintype "unspecified"))
      (node (ref "Q6") (pin "2") (pinfunction "D_2") (pintype "unspecified"))
      (node (ref "R6") (pin "2") (pinfunction "2_2") (pintype "unspecified"))
    )
    (net (code "25") (name "G") (class "Default")
      (node (ref "LED103") (pin "1") (pinfunction "K_1") (pintype "unspecified"))
      (node (ref "LED119") (pin "1") (pinfunction "K_1") (pintype "unspecified"))
      (node (ref "LED135") (pin "1") (pinfunction "K_1") (pintype "unspecified"))
      (node (ref "LED151") (pin "1") (pinfunction "K_1") (pintype "unspecified"))
      (node (ref "LED167") (pin "1") (pinfunction "K_1") (pintype "unspecified"))
      (node (ref "LED183") (pin "1") (pinfunction "K_1") (pintype "unspecified"))
      (node (ref "LED199") (pin "1") (pinfunction "K_1") (pintype "unspecified"))
      (node (ref "LED215") (pin "1") (pinfunction "K_1") (pintype "unspecified"))
      (node (ref "LED23") (pin "1") (pinfunction "K_1") (pintype "unspecified"))
      (node (ref "LED231") (pin "1") (pinfunction "K_1") (pintype "unspecified"))
      (node (ref "LED247") (pin "1") (pinfunction "K_1") (pintype "unspecified"))
      (node (ref "LED39") (pin "1") (pinfunction "K_1") (pintype "unspecified"))
      (node (ref "LED55") (pin "1") (pinfunction "K_1") (pintype "unspecified"))
      (node (ref "LED7") (pin "1") (pinfunction "K_1") (pintype "unspecified"))
      (node (ref "LED71") (pin "1") (pinfunction "K_1") (pintype "unspecified"))
      (node (ref "LED87") (pin "1") (pinfunction "K_1") (pintype "unspecified"))
      (node (ref "Q7") (pin "2") (pinfunction "D_2") (pintype "unspecified"))
      (node (ref "R7") (pin "2") (pinfunction "2_2") (pintype "unspecified"))
    )
    (net (code "26") (name "GND") (class "Default")
      (node (ref "C1") (pin "1") (pinfunction "1_1") (pintype "unspecified"))
      (node (ref "C2") (pin "1") (pinfunction "1_1") (pintype "unspecified"))
      (node (ref "C3") (pin "1") (pinfunction "1_1") (pintype "unspecified"))
      (node (ref "C4") (pin "1") (pinfunction "1_1") (pintype "unspecified"))
      (node (ref "C5") (pin "2") (pinfunction "2_2") (pintype "input"))
      (node (ref "C6") (pin "2") (pinfunction "2_2") (pintype "unspecified"))
      (node (ref "J3") (pin "1") (pinfunction "1_1") (pintype "unspecified"))
      (node (ref "Q1") (pin "3") (pinfunction "S_3") (pintype "unspecified"))
      (node (ref "Q10") (pin "3") (pinfunction "S_3") (pintype "unspecified"))
      (node (ref "Q11") (pin "3") (pinfunction "S_3") (pintype "unspecified"))
      (node (ref "Q12") (pin "3") (pinfunction "S_3") (pintype "unspecified"))
      (node (ref "Q13") (pin "3") (pinfunction "S_3") (pintype "unspecified"))
      (node (ref "Q14") (pin "3") (pinfunction "S_3") (pintype "unspecified"))
      (node (ref "Q15") (pin "3") (pinfunction "S_3") (pintype "unspecified"))
      (node (ref "Q16") (pin "3") (pinfunction "S_3") (pintype "unspecified"))
      (node (ref "Q18") (pin "1") (pinfunction "SOURCE_1") (pintype "unspecified"))
      (node (ref "Q2") (pin "3") (pinfunction "S_3") (pintype "unspecified"))
      (node (ref "Q3") (pin "3") (pinfunction "S_3") (pintype "unspecified"))
      (node (ref "Q4") (pin "3") (pinfunction "S_3") (pintype "unspecified"))
      (node (ref "Q5") (pin "3") (pinfunction "S_3") (pintype "unspecified"))
      (node (ref "Q6") (pin "3") (pinfunction "S_3") (pintype "unspecified"))
      (node (ref "Q7") (pin "3") (pinfunction "S_3") (pintype "unspecified"))
      (node (ref "Q8") (pin "3") (pinfunction "S_3") (pintype "unspecified"))
      (node (ref "Q9") (pin "3") (pinfunction "S_3") (pintype "unspecified"))
      (node (ref "R18") (pin "1") (pinfunction "1_1") (pintype "unspecified"))
      (node (ref "R26") (pin "1") (pinfunction "1_1") (pintype "unspecified"))
      (node (ref "R35") (pin "2") (pinfunction "2_2") (pintype "unspecified"))
      (node (ref "R37") (pin "2") (pinfunction "2_2") (pintype "unspecified"))
      (node (ref "R43") (pin "2") (pinfunction "2_2") (pintype "unspecified"))
      (node (ref "R44") (pin "2") (pinfunction "2_2") (pintype "unspecified"))
      (node (ref "R46") (pin "2") (pinfunction "2_2") (pintype "unspecified"))
      (node (ref "R47") (pin "2") (pinfunction "2_2") (pintype "unspecified"))
      (node (ref "R48") (pin "2") (pinfunction "2_2") (pintype "unspecified"))
      (node (ref "R50") (pin "2") (pinfunction "2_2") (pintype "unspecified"))
      (node (ref "R51") (pin "2") (pinfunction "2_2") (pintype "unspecified"))
      (node (ref "R52") (pin "2") (pinfunction "2_2") (pintype "unspecified"))
      (node (ref "R55") (pin "2") (pinfunction "2_2") (pintype "unspecified"))
      (node (ref "R56") (pin "2") (pinfunction "2_2") (pintype "unspecified"))
      (node (ref "R58") (pin "2") (pinfunction "2_2") (pintype "unspecified"))
      (node (ref "R59") (pin "2") (pinfunction "2_2") (pintype "unspecified"))
      (node (ref "U1") (pin "12") (pinfunction "GND_12") (pintype "unspecified"))
      (node (ref "U1") (pin "23") (pinfunction "E#_23") (pintype "unspecified"))
      (node (ref "U2") (pin "8") (pinfunction "GND_8") (pintype "unspecified"))
      (node (ref "U3") (pin "10") (pinfunction "GND_10") (pintype "unspecified"))
      (node (ref "U3") (pin "19") (pinfunction "OE2#_19") (pintype "unspecified"))
      (node (ref "U4") (pin "8") (pinfunction "GND_8") (pintype "unspecified"))
      (node (ref "U5") (pin "10") (pinfunction "GND_10") (pintype "unspecified"))
      (node (ref "U5") (pin "19") (pinfunction "OE2#_19") (pintype "unspecified"))
      (node (ref "U6") (pin "14") (pinfunction "GND_14") (pintype "unspecified"))
      (node (ref "U7") (pin "2") (pinfunction "GND_2") (pintype "unspecified"))
      (node (ref "U7") (pin "4") (pinfunction "GND_4") (pintype "unspecified"))
    )
    (net (code "27") (name "H") (class "Default")
      (node (ref "LED104") (pin "1") (pinfunction "K_1") (pintype "unspecified"))
      (node (ref "LED120") (pin "1") (pinfunction "K_1") (pintype "unspecified"))
      (node (ref "LED136") (pin "1") (pinfunction "K_1") (pintype "unspecified"))
      (node (ref "LED152") (pin "1") (pinfunction "K_1") (pintype "unspecified"))
      (node (ref "LED168") (pin "1") (pinfunction "K_1") (pintype "unspecified"))
      (node (ref "LED184") (pin "1") (pinfunction "K_1") (pintype "unspecified"))
      (node (ref "LED200") (pin "1") (pinfunction "K_1") (pintype "unspecified"))
      (node (ref "LED216") (pin "1") (pinfunction "K_1") (pintype "unspecified"))
      (node (ref "LED232") (pin "1") (pinfunction "K_1") (pintype "unspecified"))
      (node (ref "LED24") (pin "1") (pinfunction "K_1") (pintype "unspecified"))
      (node (ref "LED248") (pin "1") (pinfunction "K_1") (pintype "unspecified"))
      (node (ref "LED40") (pin "1") (pinfunction "K_1") (pintype "unspecified"))
      (node (ref "LED56") (pin "1") (pinfunction "K_1") (pintype "unspecified"))
      (node (ref "LED72") (pin "1") (pinfunction "K_1") (pintype "unspecified"))
      (node (ref "LED8") (pin "1") (pinfunction "K_1") (pintype "unspecified"))
      (node (ref "LED88") (pin "1") (pinfunction "K_1") (pintype "unspecified"))
      (node (ref "Q8") (pin "2") (pinfunction "D_2") (pintype "unspecified"))
      (node (ref "R8") (pin "2") (pinfunction "2_2") (pintype "unspecified"))
    )
    (net (code "28") (name "I") (class "Default")
      (node (ref "LED105") (pin "1") (pinfunction "K_1") (pintype "unspecified"))
      (node (ref "LED121") (pin "1") (pinfunction "K_1") (pintype "unspecified"))
      (node (ref "LED137") (pin "1") (pinfunction "K_1") (pintype "unspecified"))
      (node (ref "LED153") (pin "1") (pinfunction "K_1") (pintype "unspecified"))
      (node (ref "LED169") (pin "1") (pinfunction "K_1") (pintype "unspecified"))
      (node (ref "LED185") (pin "1") (pinfunction "K_1") (pintype "unspecified"))
      (node (ref "LED201") (pin "1") (pinfunction "K_1") (pintype "unspecified"))
      (node (ref "LED217") (pin "1") (pinfunction "K_1") (pintype "unspecified"))
      (node (ref "LED233") (pin "1") (pinfunction "K_1") (pintype "unspecified"))
      (node (ref "LED249") (pin "1") (pinfunction "K_1") (pintype "unspecified"))
      (node (ref "LED25") (pin "1") (pinfunction "K_1") (pintype "unspecified"))
      (node (ref "LED41") (pin "1") (pinfunction "K_1") (pintype "unspecified"))
      (node (ref "LED57") (pin "1") (pinfunction "K_1") (pintype "unspecified"))
      (node (ref "LED73") (pin "1") (pinfunction "K_1") (pintype "unspecified"))
      (node (ref "LED89") (pin "1") (pinfunction "K_1") (pintype "unspecified"))
      (node (ref "LED9") (pin "1") (pinfunction "K_1") (pintype "unspecified"))
      (node (ref "Q9") (pin "2") (pinfunction "D_2") (pintype "unspecified"))
      (node (ref "R9") (pin "2") (pinfunction "2_2") (pintype "unspecified"))
    )
    (net (code "29") (name "J") (class "Default")
      (node (ref "LED10") (pin "1") (pinfunction "K_1") (pintype "unspecified"))
      (node (ref "LED106") (pin "1") (pinfunction "K_1") (pintype "unspecified"))
      (node (ref "LED122") (pin "1") (pinfunction "K_1") (pintype "unspecified"))
      (node (ref "LED138") (pin "1") (pinfunction "K_1") (pintype "unspecified"))
      (node (ref "LED154") (pin "1") (pinfunction "K_1") (pintype "unspecified"))
      (node (ref "LED170") (pin "1") (pinfunction "K_1") (pintype "unspecified"))
      (node (ref "LED186") (pin "1") (pinfunction "K_1") (pintype "unspecified"))
      (node (ref "LED202") (pin "1") (pinfunction "K_1") (pintype "unspecified"))
      (node (ref "LED218") (pin "1") (pinfunction "K_1") (pintype "unspecified"))
      (node (ref "LED234") (pin "1") (pinfunction "K_1") (pintype "unspecified"))
      (node (ref "LED250") (pin "1") (pinfunction "K_1") (pintype "unspecified"))
      (node (ref "LED26") (pin "1") (pinfunction "K_1") (pintype "unspecified"))
      (node (ref "LED42") (pin "1") (pinfunction "K_1") (pintype "unspecified"))
      (node (ref "LED58") (pin "1") (pinfunction "K_1") (pintype "unspecified"))
      (node (ref "LED74") (pin "1") (pinfunction "K_1") (pintype "unspecified"))
      (node (ref "LED90") (pin "1") (pinfunction "K_1") (pintype "unspecified"))
      (node (ref "Q10") (pin "2") (pinfunction "D_2") (pintype "unspecified"))
      (node (ref "R10") (pin "2") (pinfunction "2_2") (pintype "unspecified"))
    )
    (net (code "30") (name "K") (class "Default")
      (node (ref "LED107") (pin "1") (pinfunction "K_1") (pintype "unspecified"))
      (node (ref "LED11") (pin "1") (pinfunction "K_1") (pintype "unspecified"))
      (node (ref "LED123") (pin "1") (pinfunction "K_1") (pintype "unspecified"))
      (node (ref "LED139") (pin "1") (pinfunction "K_1") (pintype "unspecified"))
      (node (ref "LED155") (pin "1") (pinfunction "K_1") (pintype "unspecified"))
      (node (ref "LED171") (pin "1") (pinfunction "K_1") (pintype "unspecified"))
      (node (ref "LED187") (pin "1") (pinfunction "K_1") (pintype "unspecified"))
      (node (ref "LED203") (pin "1") (pinfunction "K_1") (pintype "unspecified"))
      (node (ref "LED219") (pin "1") (pinfunction "K_1") (pintype "unspecified"))
      (node (ref "LED235") (pin "1") (pinfunction "K_1") (pintype "unspecified"))
      (node (ref "LED251") (pin "1") (pinfunction "K_1") (pintype "unspecified"))
      (node (ref "LED27") (pin "1") (pinfunction "K_1") (pintype "unspecified"))
      (node (ref "LED43") (pin "1") (pinfunction "K_1") (pintype "unspecified"))
      (node (ref "LED59") (pin "1") (pinfunction "K_1") (pintype "unspecified"))
      (node (ref "LED75") (pin "1") (pinfunction "K_1") (pintype "unspecified"))
      (node (ref "LED91") (pin "1") (pinfunction "K_1") (pintype "unspecified"))
      (node (ref "Q11") (pin "2") (pinfunction "D_2") (pintype "unspecified"))
      (node (ref "R11") (pin "2") (pinfunction "2_2") (pintype "unspecified"))
    )
    (net (code "31") (name "L") (class "Default")
      (node (ref "LED108") (pin "1") (pinfunction "K_1") (pintype "unspecified"))
      (node (ref "LED12") (pin "1") (pinfunction "K_1") (pintype "unspecified"))
      (node (ref "LED124") (pin "1") (pinfunction "K_1") (pintype "unspecified"))
      (node (ref "LED140") (pin "1") (pinfunction "K_1") (pintype "unspecified"))
      (node (ref "LED156") (pin "1") (pinfunction "K_1") (pintype "unspecified"))
      (node (ref "LED172") (pin "1") (pinfunction "K_1") (pintype "unspecified"))
      (node (ref "LED188") (pin "1") (pinfunction "K_1") (pintype "unspecified"))
      (node (ref "LED204") (pin "1") (pinfunction "K_1") (pintype "unspecified"))
      (node (ref "LED220") (pin "1") (pinfunction "K_1") (pintype "unspecified"))
      (node (ref "LED236") (pin "1") (pinfunction "K_1") (pintype "unspecified"))
      (node (ref "LED252") (pin "1") (pinfunction "K_1") (pintype "unspecified"))
      (node (ref "LED28") (pin "1") (pinfunction "K_1") (pintype "unspecified"))
      (node (ref "LED44") (pin "1") (pinfunction "K_1") (pintype "unspecified"))
      (node (ref "LED60") (pin "1") (pinfunction "K_1") (pintype "unspecified"))
      (node (ref "LED76") (pin "1") (pinfunction "K_1") (pintype "unspecified"))
      (node (ref "LED92") (pin "1") (pinfunction "K_1") (pintype "unspecified"))
      (node (ref "Q12") (pin "2") (pinfunction "D_2") (pintype "unspecified"))
      (node (ref "R12") (pin "2") (pinfunction "2_2") (pintype "unspecified"))
    )
    (net (code "32") (name "M") (class "Default")
      (node (ref "LED109") (pin "1") (pinfunction "K_1") (pintype "unspecified"))
      (node (ref "LED125") (pin "1") (pinfunction "K_1") (pintype "unspecified"))
      (node (ref "LED13") (pin "1") (pinfunction "K_1") (pintype "unspecified"))
      (node (ref "LED141") (pin "1") (pinfunction "K_1") (pintype "unspecified"))
      (node (ref "LED157") (pin "1") (pinfunction "K_1") (pintype "unspecified"))
      (node (ref "LED173") (pin "1") (pinfunction "K_1") (pintype "unspecified"))
      (node (ref "LED189") (pin "1") (pinfunction "K_1") (pintype "unspecified"))
      (node (ref "LED205") (pin "1") (pinfunction "K_1") (pintype "unspecified"))
      (node (ref "LED221") (pin "1") (pinfunction "K_1") (pintype "unspecified"))
      (node (ref "LED237") (pin "1") (pinfunction "K_1") (pintype "unspecified"))
      (node (ref "LED253") (pin "1") (pinfunction "K_1") (pintype "unspecified"))
      (node (ref "LED29") (pin "1") (pinfunction "K_1") (pintype "unspecified"))
      (node (ref "LED45") (pin "1") (pinfunction "K_1") (pintype "unspecified"))
      (node (ref "LED61") (pin "1") (pinfunction "K_1") (pintype "unspecified"))
      (node (ref "LED77") (pin "1") (pinfunction "K_1") (pintype "unspecified"))
      (node (ref "LED93") (pin "1") (pinfunction "K_1") (pintype "unspecified"))
      (node (ref "Q13") (pin "2") (pinfunction "D_2") (pintype "unspecified"))
      (node (ref "R13") (pin "2") (pinfunction "2_2") (pintype "unspecified"))
    )
    (net (code "33") (name "N") (class "Default")
      (node (ref "LED110") (pin "1") (pinfunction "K_1") (pintype "unspecified"))
      (node (ref "LED126") (pin "1") (pinfunction "K_1") (pintype "unspecified"))
      (node (ref "LED14") (pin "1") (pinfunction "K_1") (pintype "unspecified"))
      (node (ref "LED142") (pin "1") (pinfunction "K_1") (pintype "unspecified"))
      (node (ref "LED158") (pin "1") (pinfunction "K_1") (pintype "unspecified"))
      (node (ref "LED174") (pin "1") (pinfunction "K_1") (pintype "unspecified"))
      (node (ref "LED190") (pin "1") (pinfunction "K_1") (pintype "unspecified"))
      (node (ref "LED206") (pin "1") (pinfunction "K_1") (pintype "unspecified"))
      (node (ref "LED222") (pin "1") (pinfunction "K_1") (pintype "unspecified"))
      (node (ref "LED238") (pin "1") (pinfunction "K_1") (pintype "unspecified"))
      (node (ref "LED254") (pin "1") (pinfunction "K_1") (pintype "unspecified"))
      (node (ref "LED30") (pin "1") (pinfunction "K_1") (pintype "unspecified"))
      (node (ref "LED46") (pin "1") (pinfunction "K_1") (pintype "unspecified"))
      (node (ref "LED62") (pin "1") (pinfunction "K_1") (pintype "unspecified"))
      (node (ref "LED78") (pin "1") (pinfunction "K_1") (pintype "unspecified"))
      (node (ref "LED94") (pin "1") (pinfunction "K_1") (pintype "unspecified"))
      (node (ref "Q14") (pin "2") (pinfunction "D_2") (pintype "unspecified"))
      (node (ref "R14") (pin "2") (pinfunction "2_2") (pintype "unspecified"))
    )
    (net (code "34") (name "Net-(C4-Pad2)") (class "Default")
      (node (ref "C4") (pin "2") (pinfunction "2_2") (pintype "unspecified"))
      (node (ref "R30") (pin "1") (pinfunction "1_1") (pintype "unspecified"))
      (node (ref "X1") (pin "2") (pinfunction "2_2") (pintype "unspecified"))
    )
    (net (code "35") (name "Net-(Q1-G)") (class "Default")
      (node (ref "Q1") (pin "1") (pinfunction "G_1") (pintype "unspecified"))
      (node (ref "U1") (pin "11") (pinfunction "Q0_11") (pintype "unspecified"))
    )
    (net (code "36") (name "Net-(Q2-G)") (class "Default")
      (node (ref "Q2") (pin "1") (pinfunction "G_1") (pintype "unspecified"))
      (node (ref "U1") (pin "9") (pinfunction "Q1_9") (pintype "unspecified"))
    )
    (net (code "37") (name "Net-(Q3-G)") (class "Default")
      (node (ref "Q3") (pin "1") (pinfunction "G_1") (pintype "unspecified"))
      (node (ref "U1") (pin "10") (pinfunction "Q2_10") (pintype "unspecified"))
    )
    (net (code "38") (name "Net-(Q4-G)") (class "Default")
      (node (ref "Q4") (pin "1") (pinfunction "G_1") (pintype "unspecified"))
      (node (ref "U1") (pin "8") (pinfunction "Q3_8") (pintype "unspecified"))
    )
    (net (code "39") (name "Net-(Q5-G)") (class "Default")
      (node (ref "Q5") (pin "1") (pinfunction "G_1") (pintype "unspecified"))
      (node (ref "U1") (pin "7") (pinfunction "Q4_7") (pintype "unspecified"))
    )
    (net (code "40") (name "Net-(Q6-G)") (class "Default")
      (node (ref "Q6") (pin "1") (pinfunction "G_1") (pintype "unspecified"))
      (node (ref "U1") (pin "6") (pinfunction "Q5_6") (pintype "unspecified"))
    )
    (net (code "41") (name "Net-(Q7-G)") (class "Default")
      (node (ref "Q7") (pin "1") (pinfunction "G_1") (pintype "unspecified"))
      (node (ref "U1") (pin "5") (pinfunction "Q6_5") (pintype "unspecified"))
    )
    (net (code "42") (name "Net-(Q8-G)") (class "Default")
      (node (ref "Q8") (pin "1") (pinfunction "G_1") (pintype "unspecified"))
      (node (ref "U1") (pin "4") (pinfunction "Q7_4") (pintype "unspecified"))
    )
    (net (code "43") (name "Net-(Q9-G)") (class "Default")
      (node (ref "Q9") (pin "1") (pinfunction "G_1") (pintype "unspecified"))
      (node (ref "U1") (pin "18") (pinfunction "Q8_18") (pintype "unspecified"))
    )
    (net (code "44") (name "Net-(Q10-G)") (class "Default")
      (node (ref "Q10") (pin "1") (pinfunction "G_1") (pintype "unspecified"))
      (node (ref "U1") (pin "17") (pinfunction "Q9_17") (pintype "unspecified"))
    )
    (net (code "45") (name "Net-(Q11-G)") (class "Default")
      (node (ref "Q11") (pin "1") (pinfunction "G_1") (pintype "unspecified"))
      (node (ref "U1") (pin "20") (pinfunction "Q10_20") (pintype "unspecified"))
    )
    (net (code "46") (name "Net-(Q12-G)") (class "Default")
      (node (ref "Q12") (pin "1") (pinfunction "G_1") (pintype "unspecified"))
      (node (ref "U1") (pin "19") (pinfunction "Q11_19") (pintype "unspecified"))
    )
    (net (code "47") (name "Net-(Q13-G)") (class "Default")
      (node (ref "Q13") (pin "1") (pinfunction "G_1") (pintype "unspecified"))
      (node (ref "U1") (pin "14") (pinfunction "Q12_14") (pintype "unspecified"))
    )
    (net (code "48") (name "Net-(Q14-G)") (class "Default")
      (node (ref "Q14") (pin "1") (pinfunction "G_1") (pintype "unspecified"))
      (node (ref "U1") (pin "13") (pinfunction "Q13_13") (pintype "unspecified"))
    )
    (net (code "49") (name "Net-(Q15-G)") (class "Default")
      (node (ref "Q15") (pin "1") (pinfunction "G_1") (pintype "unspecified"))
      (node (ref "U1") (pin "16") (pinfunction "Q14_16") (pintype "unspecified"))
    )
    (net (code "50") (name "Net-(Q16-G)") (class "Default")
      (node (ref "Q16") (pin "1") (pinfunction "G_1") (pintype "unspecified"))
      (node (ref "U1") (pin "15") (pinfunction "Q15_15") (pintype "unspecified"))
    )
    (net (code "51") (name "Net-(Q17-D)") (class "Default")
      (node (ref "Q17") (pin "3") (pinfunction "D_3") (pintype "unspecified"))
      (node (ref "R19") (pin "1") (pinfunction "1_1") (pintype "unspecified"))
    )
    (net (code "52") (name "Net-(Q17-G)") (class "Default")
      (node (ref "Q17") (pin "1") (pinfunction "G_1") (pintype "unspecified"))
      (node (ref "R17") (pin "2") (pinfunction "2_2") (pintype "unspecified"))
      (node (ref "U3") (pin "18") (pinfunction "Y0_18") (pintype "unspecified"))
    )
    (net (code "53") (name "Net-(Q18-DRAIN)") (class "Default")
      (node (ref "Q18") (pin "3") (pinfunction "DRAIN_3") (pintype "unspecified"))
      (node (ref "R21") (pin "1") (pinfunction "1_1") (pintype "unspecified"))
      (node (ref "U3") (pin "1") (pinfunction "OE1#_1") (pintype "unspecified"))
    )
    (net (code "54") (name "Net-(Q18-GATE)") (class "Default")
      (node (ref "Q18") (pin "2") (pinfunction "GATE_2") (pintype "unspecified"))
      (node (ref "U4") (pin "15") (pinfunction "QA_15") (pintype "unspecified"))
      (node (ref "U5") (pin "1") (pinfunction "OE1#_1") (pintype "unspecified"))
      (node (ref "U6") (pin "10") (pinfunction "A0_10") (pintype "unspecified"))
    )
    (net (code "55") (name "Net-(Q19-D)") (class "Default")
      (node (ref "Q19") (pin "3") (pinfunction "D_3") (pintype "unspecified"))
      (node (ref "R22") (pin "1") (pinfunction "1_1") (pintype "unspecified"))
    )
    (net (code "56") (name "Net-(Q19-G)") (class "Default")
      (node (ref "Q19") (pin "1") (pinfunction "G_1") (pintype "unspecified"))
      (node (ref "R20") (pin "1") (pinfunction "1_1") (pintype "unspecified"))
      (node (ref "U3") (pin "17") (pinfunction "Y1_17") (pintype "unspecified"))
    )
    (net (code "57") (name "Net-(Q20-D)") (class "Default")
      (node (ref "Q20") (pin "3") (pinfunction "D_3") (pintype "unspecified"))
      (node (ref "R24") (pin "1") (pinfunction "1_1") (pintype "unspecified"))
    )
    (net (code "58") (name "Net-(Q20-G)") (class "Default")
      (node (ref "Q20") (pin "1") (pinfunction "G_1") (pintype "unspecified"))
      (node (ref "R23") (pin "1") (pinfunction "1_1") (pintype "unspecified"))
      (node (ref "U3") (pin "16") (pinfunction "Y2_16") (pintype "unspecified"))
    )
    (net (code "59") (name "Net-(Q21-D)") (class "Default")
      (node (ref "Q21") (pin "3") (pinfunction "D_3") (pintype "unspecified"))
      (node (ref "R27") (pin "1") (pinfunction "1_1") (pintype "unspecified"))
    )
    (net (code "60") (name "Net-(Q21-G)") (class "Default")
      (node (ref "Q21") (pin "1") (pinfunction "G_1") (pintype "unspecified"))
      (node (ref "R25") (pin "1") (pinfunction "1_1") (pintype "unspecified"))
      (node (ref "U3") (pin "15") (pinfunction "Y3_15") (pintype "unspecified"))
    )
    (net (code "61") (name "Net-(Q22-D)") (class "Default")
      (node (ref "Q22") (pin "3") (pinfunction "D_3") (pintype "unspecified"))
      (node (ref "R31") (pin "1") (pinfunction "1_1") (pintype "unspecified"))
    )
    (net (code "62") (name "Net-(Q22-G)") (class "Default")
      (node (ref "Q22") (pin "1") (pinfunction "G_1") (pintype "unspecified"))
      (node (ref "R69") (pin "1") (pinfunction "1_1") (pintype "unspecified"))
      (node (ref "U3") (pin "14") (pinfunction "Y4_14") (pintype "unspecified"))
    )
    (net (code "63") (name "Net-(Q23-D)") (class "Default")
      (node (ref "Q23") (pin "3") (pinfunction "D_3") (pintype "unspecified"))
      (node (ref "R34") (pin "1") (pinfunction "1_1") (pintype "unspecified"))
    )
    (net (code "64") (name "Net-(Q23-G)") (class "Default")
      (node (ref "Q23") (pin "1") (pinfunction "G_1") (pintype "unspecified"))
      (node (ref "R32") (pin "1") (pinfunction "1_1") (pintype "unspecified"))
      (node (ref "U3") (pin "13") (pinfunction "Y5_13") (pintype "unspecified"))
    )
    (net (code "65") (name "Net-(Q24-D)") (class "Default")
      (node (ref "Q24") (pin "3") (pinfunction "D_3") (pintype "unspecified"))
      (node (ref "R38") (pin "1") (pinfunction "1_1") (pintype "unspecified"))
    )
    (net (code "66") (name "Net-(Q24-G)") (class "Default")
      (node (ref "Q24") (pin "1") (pinfunction "G_1") (pintype "unspecified"))
      (node (ref "R36") (pin "1") (pinfunction "1_1") (pintype "unspecified"))
      (node (ref "U3") (pin "12") (pinfunction "Y6_12") (pintype "unspecified"))
    )
    (net (code "67") (name "Net-(Q25-D)") (class "Default")
      (node (ref "Q25") (pin "3") (pinfunction "D_3") (pintype "unspecified"))
      (node (ref "R40") (pin "1") (pinfunction "1_1") (pintype "unspecified"))
    )
    (net (code "68") (name "Net-(Q25-G)") (class "Default")
      (node (ref "Q25") (pin "1") (pinfunction "G_1") (pintype "unspecified"))
      (node (ref "R39") (pin "1") (pinfunction "1_1") (pintype "unspecified"))
      (node (ref "U3") (pin "11") (pinfunction "Y7_11") (pintype "unspecified"))
    )
    (net (code "69") (name "Net-(Q26-D)") (class "Default")
      (node (ref "Q26") (pin "3") (pinfunction "D_3") (pintype "unspecified"))
      (node (ref "R42") (pin "1") (pinfunction "1_1") (pintype "unspecified"))
    )
    (net (code "70") (name "Net-(Q26-G)") (class "Default")
      (node (ref "Q26") (pin "1") (pinfunction "G_1") (pintype "unspecified"))
      (node (ref "R41") (pin "1") (pinfunction "1_1") (pintype "unspecified"))
      (node (ref "U5") (pin "18") (pinfunction "Y0_18") (pintype "unspecified"))
    )
    (net (code "71") (name "Net-(Q27-D)") (class "Default")
      (node (ref "Q27") (pin "3") (pinfunction "D_3") (pintype "unspecified"))
      (node (ref "R49") (pin "1") (pinfunction "1_1") (pintype "unspecified"))
    )
    (net (code "72") (name "Net-(Q27-G)") (class "Default")
      (node (ref "Q27") (pin "1") (pinfunction "G_1") (pintype "unspecified"))
      (node (ref "R45") (pin "1") (pinfunction "1_1") (pintype "unspecified"))
      (node (ref "U5") (pin "17") (pinfunction "Y1_17") (pintype "unspecified"))
    )
    (net (code "73") (name "Net-(Q28-D)") (class "Default")
      (node (ref "Q28") (pin "3") (pinfunction "D_3") (pintype "unspecified"))
      (node (ref "R54") (pin "1") (pinfunction "1_1") (pintype "unspecified"))
    )
    (net (code "74") (name "Net-(Q28-G)") (class "Default")
      (node (ref "Q28") (pin "1") (pinfunction "G_1") (pintype "unspecified"))
      (node (ref "R53") (pin "1") (pinfunction "1_1") (pintype "unspecified"))
      (node (ref "U5") (pin "16") (pinfunction "Y2_16") (pintype "unspecified"))
    )
    (net (code "75") (name "Net-(Q29-D)") (class "Default")
      (node (ref "Q29") (pin "3") (pinfunction "D_3") (pintype "unspecified"))
      (node (ref "R60") (pin "1") (pinfunction "1_1") (pintype "unspecified"))
    )
    (net (code "76") (name "Net-(Q29-G)") (class "Default")
      (node (ref "Q29") (pin "1") (pinfunction "G_1") (pintype "unspecified"))
      (node (ref "R57") (pin "1") (pinfunction "1_1") (pintype "unspecified"))
      (node (ref "U5") (pin "15") (pinfunction "Y3_15") (pintype "unspecified"))
    )
    (net (code "77") (name "Net-(Q30-D)") (class "Default")
      (node (ref "Q30") (pin "3") (pinfunction "D_3") (pintype "unspecified"))
      (node (ref "R62") (pin "1") (pinfunction "1_1") (pintype "unspecified"))
    )
    (net (code "78") (name "Net-(Q30-G)") (class "Default")
      (node (ref "Q30") (pin "1") (pinfunction "G_1") (pintype "unspecified"))
      (node (ref "R61") (pin "1") (pinfunction "1_1") (pintype "unspecified"))
      (node (ref "U5") (pin "14") (pinfunction "Y4_14") (pintype "unspecified"))
    )
    (net (code "79") (name "Net-(Q31-D)") (class "Default")
      (node (ref "Q31") (pin "3") (pinfunction "D_3") (pintype "unspecified"))
      (node (ref "R64") (pin "1") (pinfunction "1_1") (pintype "unspecified"))
    )
    (net (code "80") (name "Net-(Q31-G)") (class "Default")
      (node (ref "Q31") (pin "1") (pinfunction "G_1") (pintype "unspecified"))
      (node (ref "R63") (pin "1") (pinfunction "1_1") (pintype "unspecified"))
      (node (ref "U5") (pin "13") (pinfunction "Y5_13") (pintype "unspecified"))
    )
    (net (code "81") (name "Net-(Q32-D)") (class "Default")
      (node (ref "Q32") (pin "3") (pinfunction "D_3") (pintype "unspecified"))
      (node (ref "R66") (pin "1") (pinfunction "1_1") (pintype "unspecified"))
    )
    (net (code "82") (name "Net-(Q32-G)") (class "Default")
      (node (ref "Q32") (pin "1") (pinfunction "G_1") (pintype "unspecified"))
      (node (ref "R65") (pin "1") (pinfunction "1_1") (pintype "unspecified"))
      (node (ref "U5") (pin "12") (pinfunction "Y6_12") (pintype "unspecified"))
    )
    (net (code "83") (name "Net-(Q33-D)") (class "Default")
      (node (ref "Q33") (pin "3") (pinfunction "D_3") (pintype "unspecified"))
      (node (ref "R68") (pin "1") (pinfunction "1_1") (pintype "unspecified"))
    )
    (net (code "84") (name "Net-(Q33-G)") (class "Default")
      (node (ref "Q33") (pin "1") (pinfunction "G_1") (pintype "unspecified"))
      (node (ref "R67") (pin "1") (pinfunction "1_1") (pintype "unspecified"))
      (node (ref "U5") (pin "11") (pinfunction "Y7_11") (pintype "unspecified"))
    )
    (net (code "85") (name "Net-(R58-Pad1)") (class "Default")
      (node (ref "R58") (pin "1") (pinfunction "1_1") (pintype "unspecified"))
      (node (ref "SW1") (pin "6") (pinfunction "6_6") (pintype "unspecified"))
    )
    (net (code "86") (name "Net-(R59-Pad1)") (class "Default")
      (node (ref "R59") (pin "1") (pinfunction "1_1") (pintype "unspecified"))
      (node (ref "SW1") (pin "5") (pinfunction "5_5") (pintype "unspecified"))
    )
    (net (code "87") (name "Net-(U1-A0)") (class "Default")
      (node (ref "U1") (pin "2") (pinfunction "A0_2") (pintype "unspecified"))
      (node (ref "U4") (pin "1") (pinfunction "QB_1") (pintype "unspecified"))
      (node (ref "U6") (pin "9") (pinfunction "A1_9") (pintype "unspecified"))
    )
    (net (code "88") (name "Net-(U1-A1)") (class "Default")
      (node (ref "U1") (pin "3") (pinfunction "A1_3") (pintype "unspecified"))
      (node (ref "U4") (pin "2") (pinfunction "QC_2") (pintype "unspecified"))
      (node (ref "U6") (pin "8") (pinfunction "A2_8") (pintype "unspecified"))
    )
    (net (code "89") (name "Net-(U1-A2)") (class "Default")
      (node (ref "U1") (pin "21") (pinfunction "A2_21") (pintype "unspecified"))
      (node (ref "U4") (pin "3") (pinfunction "QD_3") (pintype "unspecified"))
      (node (ref "U6") (pin "7") (pinfunction "A3_7") (pintype "unspecified"))
    )
    (net (code "90") (name "Net-(U1-A3)") (class "Default")
      (node (ref "U1") (pin "22") (pinfunction "A3_22") (pintype "unspecified"))
      (node (ref "U4") (pin "4") (pinfunction "QE_4") (pintype "unspecified"))
      (node (ref "U6") (pin "6") (pinfunction "A4_6") (pintype "unspecified"))
    )
    (net (code "91") (name "Net-(U2-MR)") (class "Default")
      (node (ref "R18") (pin "2") (pinfunction "2_2") (pintype "unspecified"))
      (node (ref "U2") (pin "12") (pinfunction "MR_12") (pintype "unspecified"))
    )
    (net (code "92") (name "Net-(U2-Q4)") (class "Default")
      (node (ref "J1") (pin "1") (pinfunction "1_1") (pintype "unspecified"))
      (node (ref "U2") (pin "7") (pinfunction "Q4_7") (pintype "unspecified"))
    )
    (net (code "93") (name "Net-(U2-Q5)") (class "Default")
      (node (ref "J1") (pin "2") (pinfunction "2_2") (pintype "unspecified"))
      (node (ref "U2") (pin "5") (pinfunction "Q5_5") (pintype "unspecified"))
    )
    (net (code "94") (name "Net-(U2-Q6)") (class "Default")
      (node (ref "J1") (pin "3") (pinfunction "3_3") (pintype "unspecified"))
      (node (ref "U2") (pin "4") (pinfunction "Q6_4") (pintype "unspecified"))
    )
    (net (code "95") (name "Net-(U2-Q7)") (class "Default")
      (node (ref "J1") (pin "4") (pinfunction "4_4") (pintype "unspecified"))
      (node (ref "U2") (pin "6") (pinfunction "Q7_6") (pintype "unspecified"))
    )
    (net (code "96") (name "Net-(U2-Q8)") (class "Default")
      (node (ref "J1") (pin "5") (pinfunction "5_5") (pintype "unspecified"))
      (node (ref "U2") (pin "14") (pinfunction "Q8_14") (pintype "unspecified"))
    )
    (net (code "97") (name "Net-(U2-Q9)") (class "Default")
      (node (ref "J1") (pin "6") (pinfunction "6_6") (pintype "unspecified"))
      (node (ref "U2") (pin "13") (pinfunction "Q9_13") (pintype "unspecified"))
    )
    (net (code "98") (name "Net-(U2-Q10)") (class "Default")
      (node (ref "J1") (pin "7") (pinfunction "7_7") (pintype "unspecified"))
      (node (ref "U2") (pin "15") (pinfunction "Q10_15") (pintype "unspecified"))
    )
    (net (code "99") (name "Net-(U2-Q12)") (class "Default")
      (node (ref "J1") (pin "8") (pinfunction "8_8") (pintype "unspecified"))
      (node (ref "U2") (pin "1") (pinfunction "Q12_1") (pintype "unspecified"))
    )
    (net (code "100") (name "Net-(U2-Q13)") (class "Default")
      (node (ref "J1") (pin "9") (pinfunction "9_9") (pintype "unspecified"))
      (node (ref "U2") (pin "2") (pinfunction "Q13_2") (pintype "unspecified"))
    )
    (net (code "101") (name "Net-(U2-Q14)") (class "Default")
      (node (ref "J1") (pin "10") (pinfunction "10_10") (pintype "unspecified"))
      (node (ref "U2") (pin "3") (pinfunction "Q14_3") (pintype "unspecified"))
    )
    (net (code "102") (name "Net-(U2-φI)") (class "Default")
      (node (ref "C3") (pin "2") (pinfunction "2_2") (pintype "unspecified"))
      (node (ref "R29") (pin "1") (pinfunction "1_1") (pintype "unspecified"))
      (node (ref "U2") (pin "11") (pinfunction "φI_11") (pintype "unspecified"))
      (node (ref "X1") (pin "1") (pinfunction "1_1") (pintype "unspecified"))
    )
    (net (code "103") (name "Net-(U2-φO#)") (class "Default")
      (node (ref "R29") (pin "2") (pinfunction "2_2") (pintype "unspecified"))
      (node (ref "R30") (pin "2") (pinfunction "2_2") (pintype "unspecified"))
      (node (ref "U2") (pin "10") (pinfunction "φO#_10") (pintype "unspecified"))
    )
    (net (code "104") (name "Net-(U2-φO)") (class "Default")
      (node (ref "U2") (pin "9") (pinfunction "φO_9") (pintype "unspecified"))
      (node (ref "U4") (pin "11") (pinfunction "CCLK_11") (pintype "unspecified"))
      (node (ref "U4") (pin "13") (pinfunction "RCLK_13") (pintype "unspecified"))
    )
    (net (code "105") (name "Net-(U3-A0)") (class "Default")
      (node (ref "U3") (pin "2") (pinfunction "A0_2") (pintype "unspecified"))
      (node (ref "U5") (pin "2") (pinfunction "A0_2") (pintype "unspecified"))
      (node (ref "U6") (pin "11") (pinfunction "I/O0_11") (pintype "unspecified"))
    )
    (net (code "106") (name "Net-(U3-A1)") (class "Default")
      (node (ref "U3") (pin "3") (pinfunction "A1_3") (pintype "unspecified"))
      (node (ref "U5") (pin "3") (pinfunction "A1_3") (pintype "unspecified"))
      (node (ref "U6") (pin "12") (pinfunction "I/O1_12") (pintype "unspecified"))
    )
    (net (code "107") (name "Net-(U3-A2)") (class "Default")
      (node (ref "U3") (pin "4") (pinfunction "A2_4") (pintype "unspecified"))
      (node (ref "U5") (pin "4") (pinfunction "A2_4") (pintype "unspecified"))
      (node (ref "U6") (pin "13") (pinfunction "I/O2_13") (pintype "unspecified"))
    )
    (net (code "108") (name "Net-(U3-A3)") (class "Default")
      (node (ref "U3") (pin "5") (pinfunction "A3_5") (pintype "unspecified"))
      (node (ref "U5") (pin "5") (pinfunction "A3_5") (pintype "unspecified"))
      (node (ref "U6") (pin "15") (pinfunction "I/O3_15") (pintype "unspecified"))
    )
    (net (code "109") (name "Net-(U3-A4)") (class "Default")
      (node (ref "U3") (pin "6") (pinfunction "A4_6") (pintype "unspecified"))
      (node (ref "U5") (pin "6") (pinfunction "A4_6") (pintype "unspecified"))
      (node (ref "U6") (pin "16") (pinfunction "I/O4_16") (pintype "unspecified"))
    )
    (net (code "110") (name "Net-(U3-A5)") (class "Default")
      (node (ref "U3") (pin "7") (pinfunction "A5_7") (pintype "unspecified"))
      (node (ref "U5") (pin "7") (pinfunction "A5_7") (pintype "unspecified"))
      (node (ref "U6") (pin "17") (pinfunction "I/O5_17") (pintype "unspecified"))
    )
    (net (code "111") (name "Net-(U3-A6)") (class "Default")
      (node (ref "U3") (pin "8") (pinfunction "A6_8") (pintype "unspecified"))
      (node (ref "U5") (pin "8") (pinfunction "A6_8") (pintype "unspecified"))
      (node (ref "U6") (pin "18") (pinfunction "I/O6_18") (pintype "unspecified"))
    )
    (net (code "112") (name "Net-(U3-A7)") (class "Default")
      (node (ref "U3") (pin "9") (pinfunction "A7_9") (pintype "unspecified"))
      (node (ref "U5") (pin "9") (pinfunction "A7_9") (pintype "unspecified"))
      (node (ref "U6") (pin "19") (pinfunction "I/O7_19") (pintype "unspecified"))
    )
    (net (code "113") (name "Net-(U4-CCKEN#)") (class "Default")
      (node (ref "R26") (pin "2") (pinfunction "2_2") (pintype "unspecified"))
      (node (ref "U4") (pin "12") (pinfunction "CCKEN#_12") (pintype "unspecified"))
      (node (ref "U4") (pin "14") (pinfunction "OE#_14") (pintype "unspecified"))
    )
    (net (code "114") (name "Net-(U4-CCLR#)") (class "Default")
      (node (ref "R28") (pin "1") (pinfunction "1_1") (pintype "unspecified"))
      (node (ref "U4") (pin "10") (pinfunction "CCLR#_10") (pintype "unspecified"))
    )
    (net (code "115") (name "Net-(U4-QF)") (class "Default")
      (node (ref "J2") (pin "3") (pinfunction "3_3") (pintype "input"))
      (node (ref "U4") (pin "5") (pinfunction "QF_5") (pintype "unspecified"))
    )
    (net (code "116") (name "Net-(U4-QG)") (class "Default")
      (node (ref "J2") (pin "2") (pinfunction "2_2") (pintype "input"))
      (node (ref "U4") (pin "6") (pinfunction "QG_6") (pintype "unspecified"))
    )
    (net (code "117") (name "Net-(U4-QH)") (class "Default")
      (node (ref "J2") (pin "1") (pinfunction "1_1") (pintype "input"))
      (node (ref "U4") (pin "7") (pinfunction "QH_7") (pintype "unspecified"))
    )
    (net (code "118") (name "Net-(U6-A5)") (class "Default")
      (node (ref "R56") (pin "1") (pinfunction "1_1") (pintype "unspecified"))
      (node (ref "SW1") (pin "7") (pinfunction "7_7") (pintype "unspecified"))
      (node (ref "U6") (pin "5") (pinfunction "A5_5") (pintype "unspecified"))
    )
    (net (code "119") (name "Net-(U6-A6)") (class "Default")
      (node (ref "R55") (pin "1") (pinfunction "1_1") (pintype "unspecified"))
      (node (ref "SW1") (pin "8") (pinfunction "8_8") (pintype "unspecified"))
      (node (ref "U6") (pin "4") (pinfunction "A6_4") (pintype "unspecified"))
    )
    (net (code "120") (name "Net-(U6-A7)") (class "Default")
      (node (ref "DIP1") (pin "9") (pinfunction "9_9") (pintype "unspecified"))
      (node (ref "R52") (pin "1") (pinfunction "1_1") (pintype "unspecified"))
      (node (ref "U6") (pin "3") (pinfunction "A7_3") (pintype "unspecified"))
    )
    (net (code "121") (name "Net-(U6-A8)") (class "Default")
      (node (ref "DIP1") (pin "10") (pinfunction "10_10") (pintype "unspecified"))
      (node (ref "R51") (pin "1") (pinfunction "1_1") (pintype "unspecified"))
      (node (ref "U6") (pin "25") (pinfunction "A8_25") (pintype "unspecified"))
    )
    (net (code "122") (name "Net-(U6-A9)") (class "Default")
      (node (ref "DIP1") (pin "11") (pinfunction "11_11") (pintype "unspecified"))
      (node (ref "R50") (pin "1") (pinfunction "1_1") (pintype "unspecified"))
      (node (ref "U6") (pin "24") (pinfunction "A9_24") (pintype "unspecified"))
    )
    (net (code "123") (name "Net-(U6-A10)") (class "Default")
      (node (ref "DIP1") (pin "12") (pinfunction "12_12") (pintype "unspecified"))
      (node (ref "R48") (pin "1") (pinfunction "1_1") (pintype "unspecified"))
      (node (ref "U6") (pin "21") (pinfunction "A10_21") (pintype "unspecified"))
    )
    (net (code "124") (name "Net-(U6-A11)") (class "Default")
      (node (ref "DIP1") (pin "13") (pinfunction "13_13") (pintype "unspecified"))
      (node (ref "R47") (pin "1") (pinfunction "1_1") (pintype "unspecified"))
      (node (ref "U6") (pin "23") (pinfunction "A11_23") (pintype "unspecified"))
    )
    (net (code "125") (name "Net-(U6-A12)") (class "Default")
      (node (ref "DIP1") (pin "14") (pinfunction "14_14") (pintype "unspecified"))
      (node (ref "R46") (pin "1") (pinfunction "1_1") (pintype "unspecified"))
      (node (ref "U6") (pin "2") (pinfunction "A12_2") (pintype "unspecified"))
    )
    (net (code "126") (name "Net-(U6-A13)") (class "Default")
      (node (ref "DIP1") (pin "15") (pinfunction "15_15") (pintype "unspecified"))
      (node (ref "R44") (pin "1") (pinfunction "1_1") (pintype "unspecified"))
      (node (ref "U6") (pin "26") (pinfunction "A13_26") (pintype "unspecified"))
    )
    (net (code "127") (name "Net-(U6-A14)") (class "Default")
      (node (ref "DIP1") (pin "16") (pinfunction "16_16") (pintype "unspecified"))
      (node (ref "R43") (pin "1") (pinfunction "1_1") (pintype "unspecified"))
      (node (ref "U6") (pin "1") (pinfunction "A14_1") (pintype "unspecified"))
    )
    (net (code "128") (name "Net-(U6-CE#)") (class "Default")
      (node (ref "R37") (pin "1") (pinfunction "1_1") (pintype "unspecified"))
      (node (ref "U6") (pin "20") (pinfunction "CE#_20") (pintype "unspecified"))
    )
    (net (code "129") (name "Net-(U6-OE#)") (class "Default")
      (node (ref "R35") (pin "1") (pinfunction "1_1") (pintype "unspecified"))
      (node (ref "U6") (pin "22") (pinfunction "OE#_22") (pintype "unspecified"))
    )
    (net (code "130") (name "Net-(U6-WE#)") (class "Default")
      (node (ref "R33") (pin "1") (pinfunction "1_1") (pintype "unspecified"))
      (node (ref "U6") (pin "27") (pinfunction "WE#_27") (pintype "unspecified"))
    )
    (net (code "131") (name "O") (class "Default")
      (node (ref "LED111") (pin "1") (pinfunction "K_1") (pintype "unspecified"))
      (node (ref "LED127") (pin "1") (pinfunction "K_1") (pintype "unspecified"))
      (node (ref "LED143") (pin "1") (pinfunction "K_1") (pintype "unspecified"))
      (node (ref "LED15") (pin "1") (pinfunction "K_1") (pintype "unspecified"))
      (node (ref "LED159") (pin "1") (pinfunction "K_1") (pintype "unspecified"))
      (node (ref "LED175") (pin "1") (pinfunction "K_1") (pintype "unspecified"))
      (node (ref "LED191") (pin "1") (pinfunction "K_1") (pintype "unspecified"))
      (node (ref "LED207") (pin "1") (pinfunction "K_1") (pintype "unspecified"))
      (node (ref "LED223") (pin "1") (pinfunction "K_1") (pintype "unspecified"))
      (node (ref "LED239") (pin "1") (pinfunction "K_1") (pintype "unspecified"))
      (node (ref "LED255") (pin "1") (pinfunction "K_1") (pintype "unspecified"))
      (node (ref "LED31") (pin "1") (pinfunction "K_1") (pintype "unspecified"))
      (node (ref "LED47") (pin "1") (pinfunction "K_1") (pintype "unspecified"))
      (node (ref "LED63") (pin "1") (pinfunction "K_1") (pintype "unspecified"))
      (node (ref "LED79") (pin "1") (pinfunction "K_1") (pintype "unspecified"))
      (node (ref "LED95") (pin "1") (pinfunction "K_1") (pintype "unspecified"))
      (node (ref "Q15") (pin "2") (pinfunction "D_2") (pintype "unspecified"))
      (node (ref "R15") (pin "2") (pinfunction "2_2") (pintype "unspecified"))
    )
    (net (code "132") (name "P") (class "Default")
      (node (ref "LED112") (pin "1") (pinfunction "K_1") (pintype "unspecified"))
      (node (ref "LED128") (pin "1") (pinfunction "K_1") (pintype "unspecified"))
      (node (ref "LED144") (pin "1") (pinfunction "K_1") (pintype "unspecified"))
      (node (ref "LED16") (pin "1") (pinfunction "K_1") (pintype "unspecified"))
      (node (ref "LED160") (pin "1") (pinfunction "K_1") (pintype "unspecified"))
      (node (ref "LED176") (pin "1") (pinfunction "K_1") (pintype "unspecified"))
      (node (ref "LED192") (pin "1") (pinfunction "K_1") (pintype "unspecified"))
      (node (ref "LED208") (pin "1") (pinfunction "K_1") (pintype "unspecified"))
      (node (ref "LED224") (pin "1") (pinfunction "K_1") (pintype "unspecified"))
      (node (ref "LED240") (pin "1") (pinfunction "K_1") (pintype "unspecified"))
      (node (ref "LED256") (pin "1") (pinfunction "K_1") (pintype "unspecified"))
      (node (ref "LED32") (pin "1") (pinfunction "K_1") (pintype "unspecified"))
      (node (ref "LED48") (pin "1") (pinfunction "K_1") (pintype "unspecified"))
      (node (ref "LED64") (pin "1") (pinfunction "K_1") (pintype "unspecified"))
      (node (ref "LED80") (pin "1") (pinfunction "K_1") (pintype "unspecified"))
      (node (ref "LED96") (pin "1") (pinfunction "K_1") (pintype "unspecified"))
      (node (ref "Q16") (pin "2") (pinfunction "D_2") (pintype "unspecified"))
      (node (ref "R16") (pin "2") (pinfunction "2_2") (pintype "unspecified"))
    )
    (net (code "133") (name "unconnected-(U4-RCO#-Pad9)") (class "Default")
      (node (ref "U4") (pin "9") (pinfunction "RCO#_9") (pintype "unspecified+no_connect"))
    )
  )
)
